# BeagleBone_Black_Wireless_3D.net
KiCad netlist of a schematic drawn in EAGLE
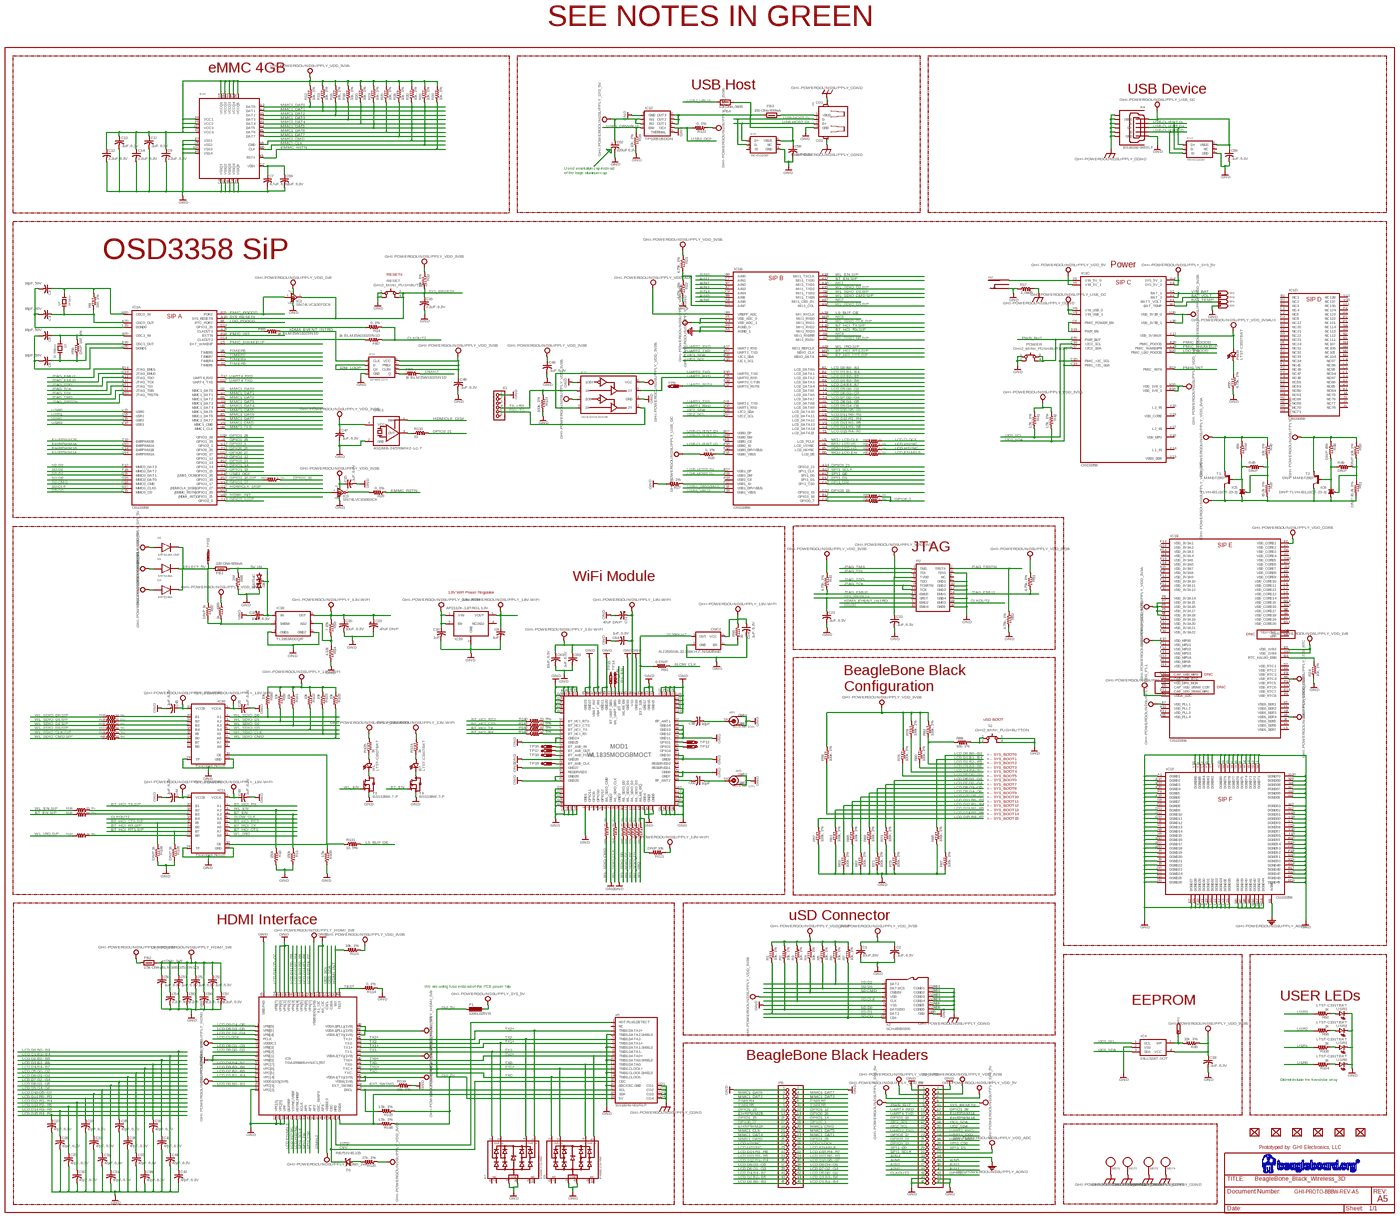
[diagram p0: schematic, sheet 1, overview]
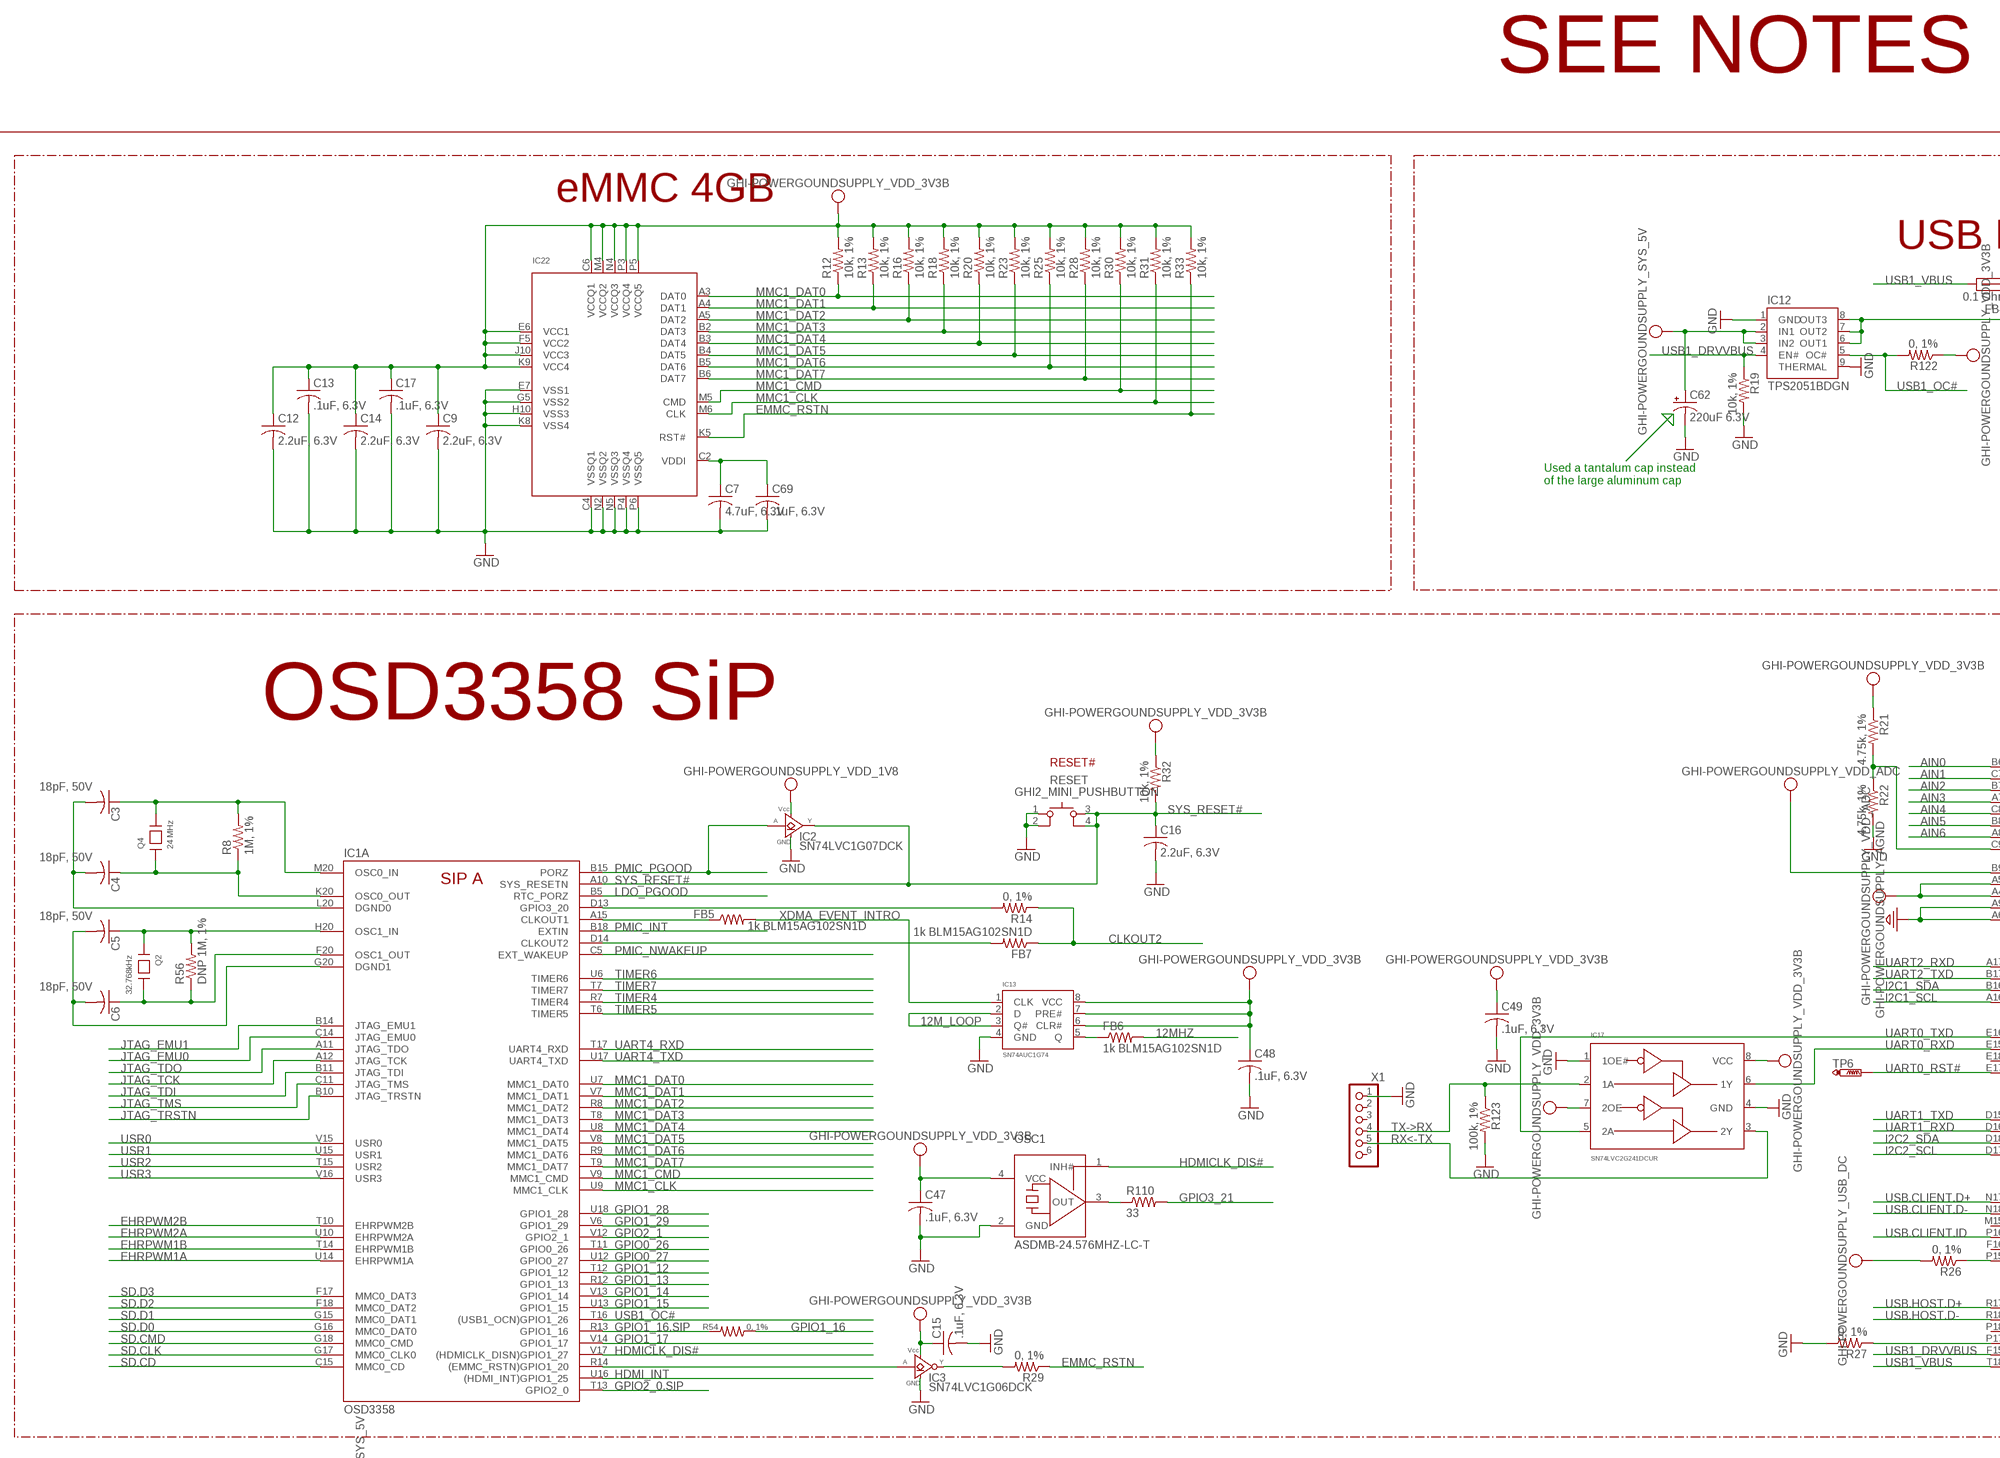
[diagram p1: schematic, sheet 1, part 1 of 4]
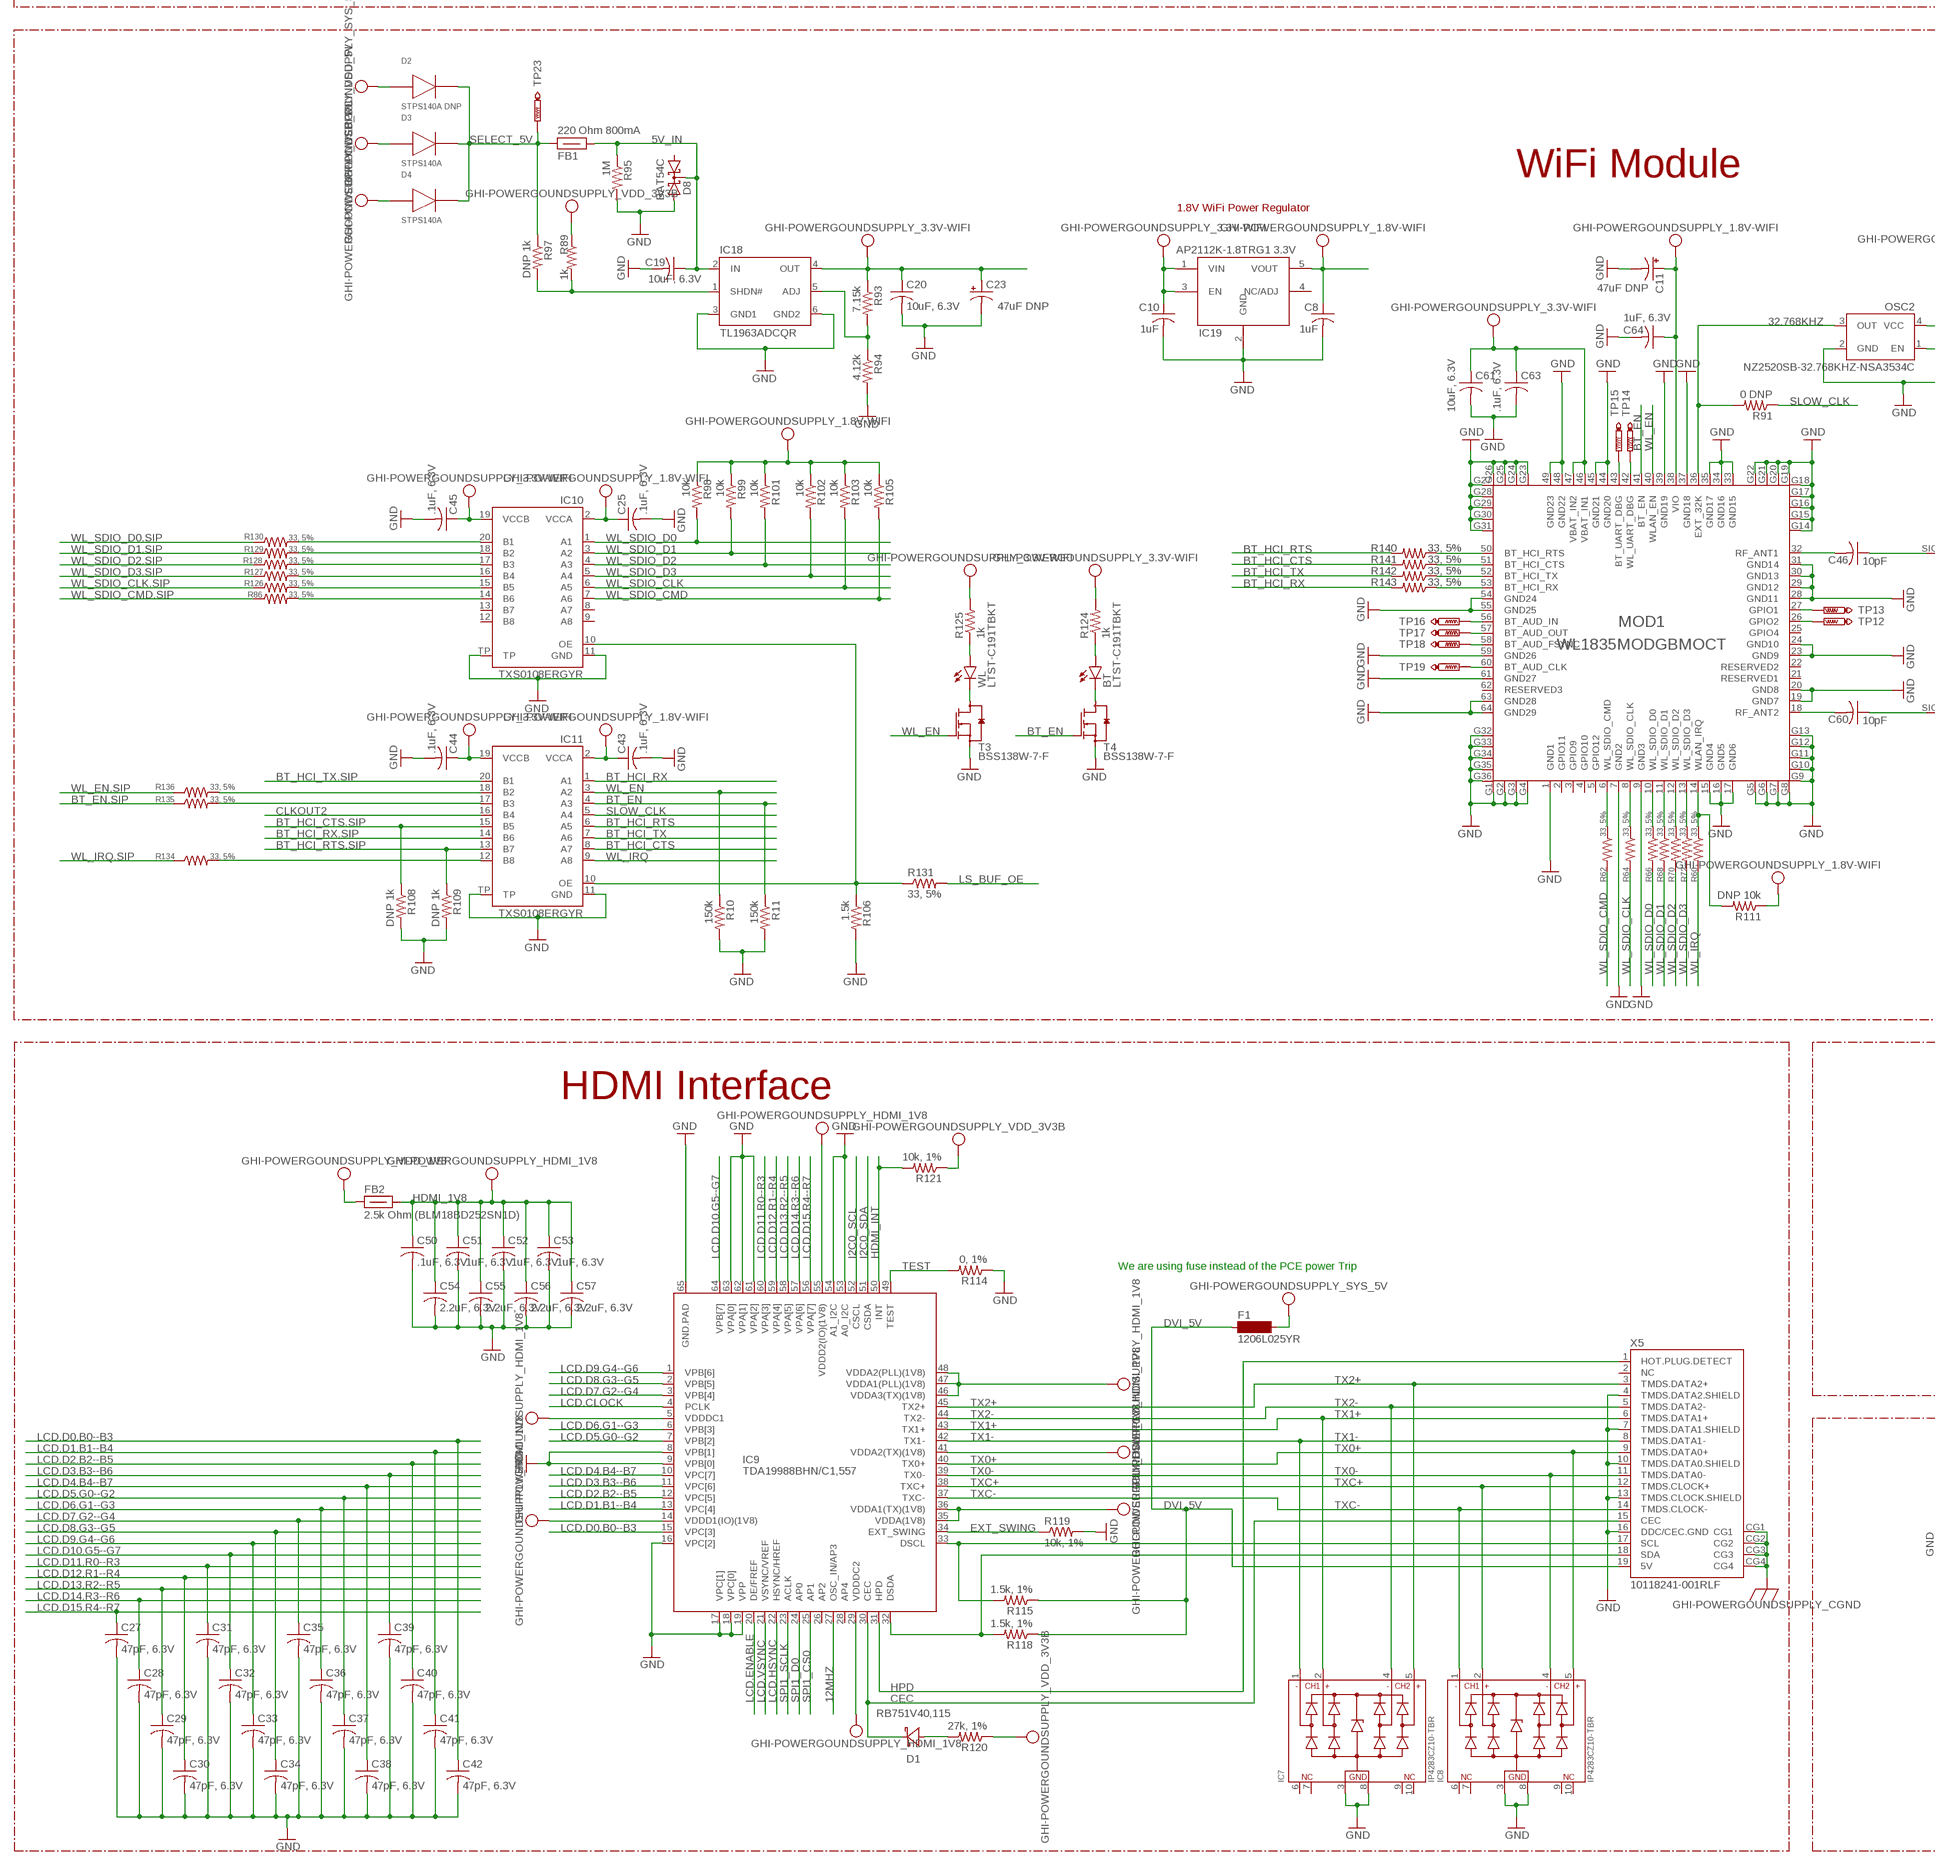
[diagram p2: schematic, sheet 1, part 2 of 4]
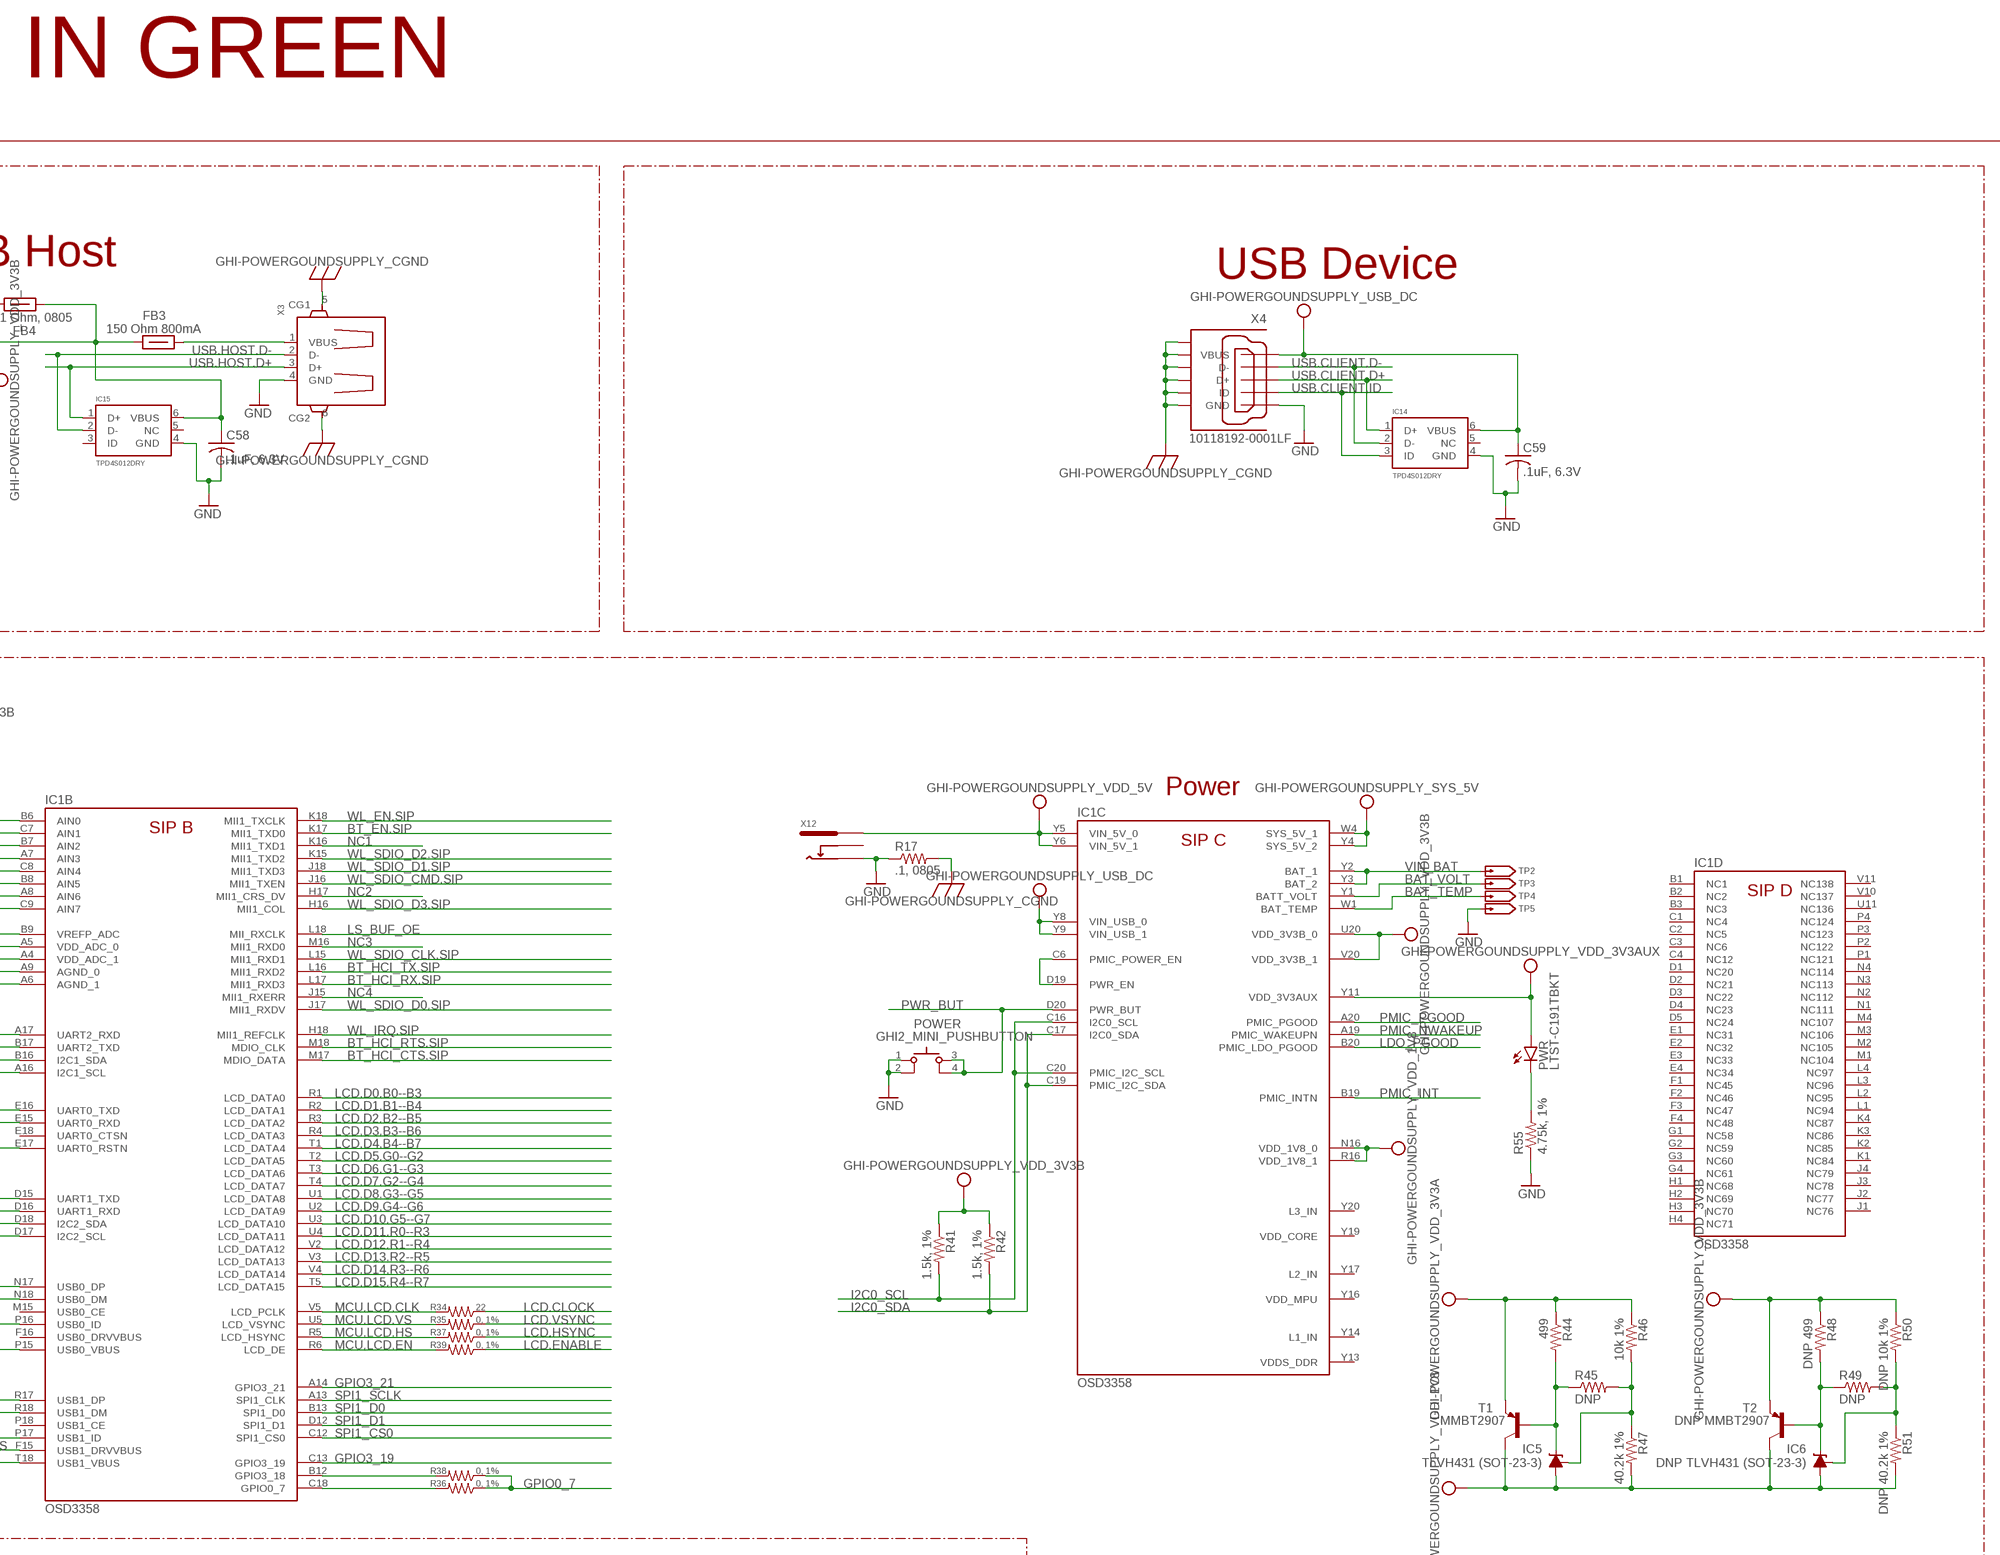
[diagram p3: schematic, sheet 1, part 3 of 4]
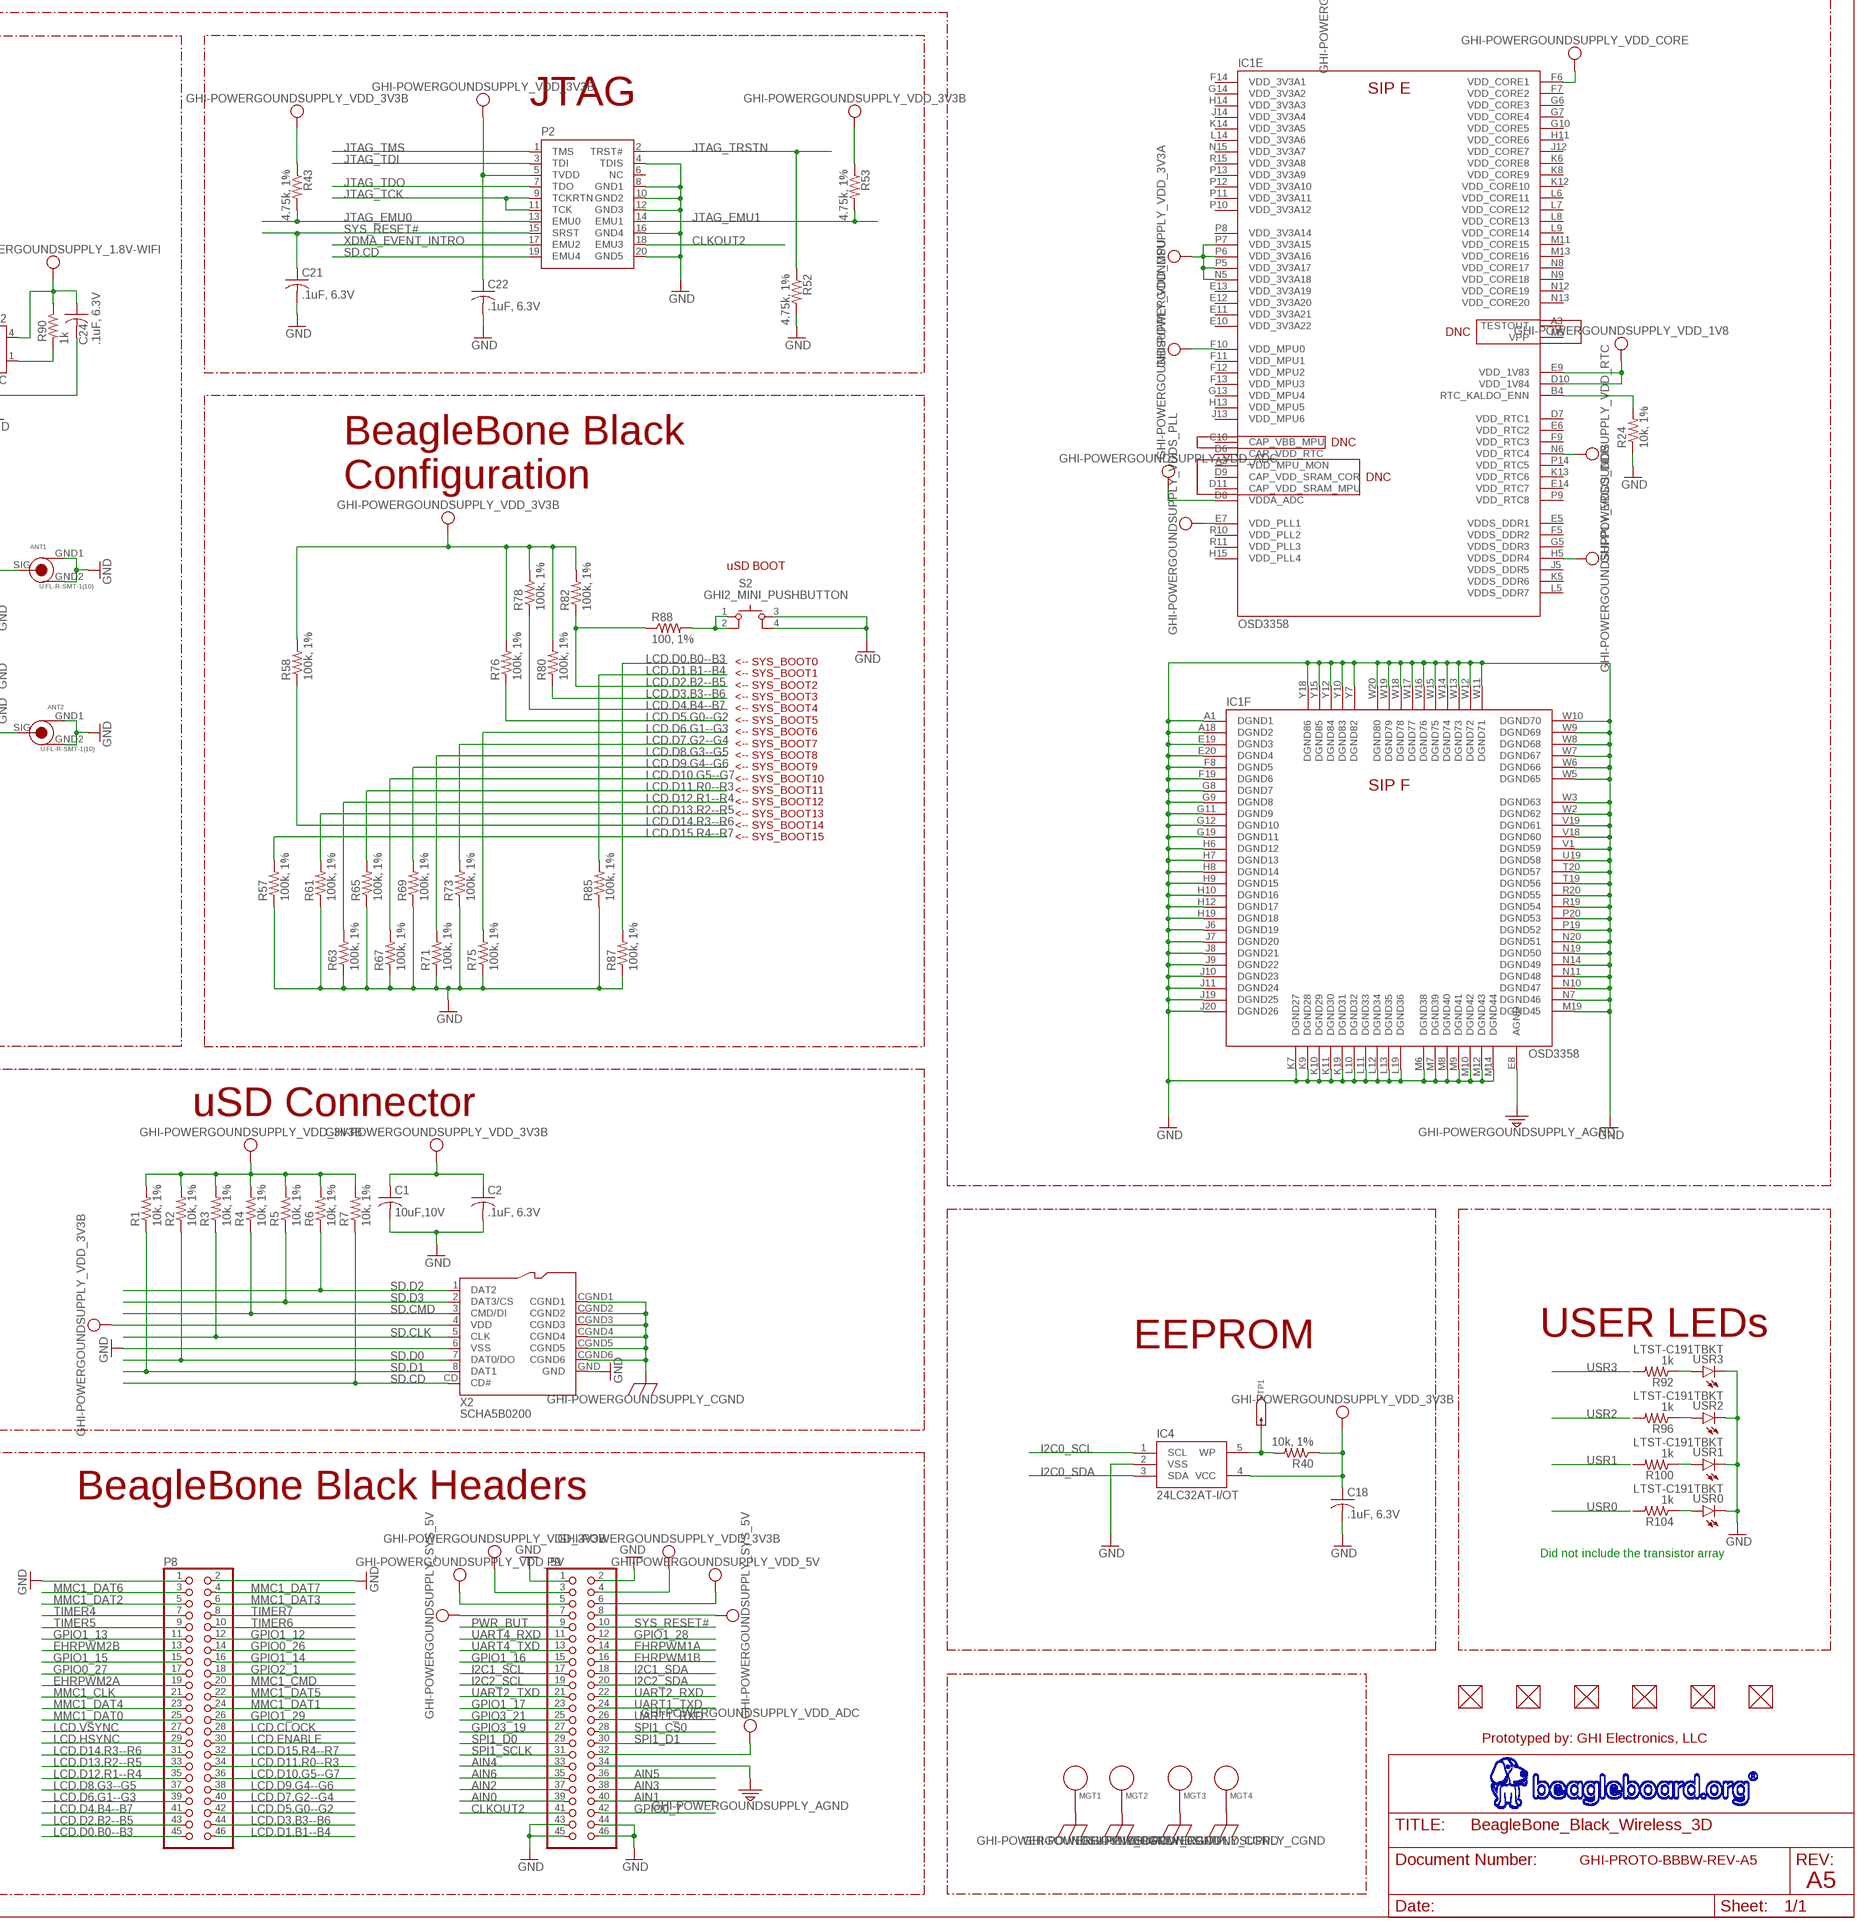
[diagram p4: schematic, sheet 1, part 4 of 4]

(export (version "E")
  (design (tool "Eeschema 10.0.6"))
  (components
    (comp (ref "ANT1")
      (value "U.FL-R-SMT-1(10)")
      (footprint "eagle-import:GHI-CONNECTORS_U.FL-R-SMT-1")
      (libsource (lib "eagle-import") (part "GHI-CONNECTORS_U.FL-R-SMT-1"))
    )
    (comp (ref "ANT2")
      (value "U.FL-R-SMT-1(10)")
      (footprint "eagle-import:GHI-CONNECTORS_U.FL-R-SMT-1")
      (libsource (lib "eagle-import") (part "GHI-CONNECTORS_U.FL-R-SMT-1"))
    )
    (comp (ref "BT")
      (value "LTST-C191TBKT")
      (footprint "eagle-import:GHI-BASICCOMPONENTS_0603-LED")
      (libsource (lib "eagle-import") (part "GHI-BASICCOMPONENTS_LED-(INCH)-0603"))
    )
    (comp (ref "C1")
      (value "10uF,10V")
      (footprint "eagle-import:C0603K")
      (libsource (lib "eagle-import") (part "rcl_334_C-USC0603K"))
    )
    (comp (ref "C2")
      (value ".1uF, 6.3V")
      (footprint "eagle-import:C0402K")
      (libsource (lib "eagle-import") (part "C-USC0402K"))
    )
    (comp (ref "C3")
      (value "18pF, 50V")
      (footprint "eagle-import:C0402K")
      (libsource (lib "eagle-import") (part "C-USC0402K"))
    )
    (comp (ref "C4")
      (value "18pF, 50V")
      (footprint "eagle-import:C0402K")
      (libsource (lib "eagle-import") (part "C-USC0402K"))
    )
    (comp (ref "C5")
      (value "18pF, 50V")
      (footprint "eagle-import:C0402K")
      (libsource (lib "eagle-import") (part "C-USC0402K"))
    )
    (comp (ref "C6")
      (value "18pF, 50V")
      (footprint "eagle-import:C0402K")
      (libsource (lib "eagle-import") (part "C-USC0402K"))
    )
    (comp (ref "C7")
      (value "4.7uF, 6.3V")
      (footprint "eagle-import:C0805K")
      (libsource (lib "eagle-import") (part "rcl_334_C-USC0805K"))
    )
    (comp (ref "C8")
      (value "1uF")
      (footprint "eagle-import:C0402K")
      (libsource (lib "eagle-import") (part "C-USC0402K"))
    )
    (comp (ref "C9")
      (value "2.2uF, 6.3V")
      (footprint "eagle-import:C0805K")
      (libsource (lib "eagle-import") (part "rcl_334_C-USC0805K"))
    )
    (comp (ref "C10")
      (value "1uF")
      (footprint "eagle-import:C0402K")
      (libsource (lib "eagle-import") (part "C-USC0402K"))
    )
    (comp (ref "C11")
      (value "47uF DNP")
      (footprint "eagle-import:CT3528")
      (libsource (lib "eagle-import") (part "CPOL-USCT3528"))
    )
    (comp (ref "C12")
      (value "2.2uF, 6.3V")
      (footprint "eagle-import:C0805K")
      (libsource (lib "eagle-import") (part "rcl_334_C-USC0805K"))
    )
    (comp (ref "C13")
      (value ".1uF, 6.3V")
      (footprint "eagle-import:C0402K")
      (libsource (lib "eagle-import") (part "C-USC0402K"))
    )
    (comp (ref "C14")
      (value "2.2uF, 6.3V")
      (footprint "eagle-import:C0805K")
      (libsource (lib "eagle-import") (part "rcl_334_C-USC0805K"))
    )
    (comp (ref "C15")
      (value ".1uF, 6.3V")
      (footprint "eagle-import:C0402K")
      (libsource (lib "eagle-import") (part "C-USC0402K"))
    )
    (comp (ref "C16")
      (value "2.2uF, 6.3V")
      (footprint "eagle-import:C0603K")
      (libsource (lib "eagle-import") (part "rcl_334_C-USC0603K"))
    )
    (comp (ref "C17")
      (value ".1uF, 6.3V")
      (footprint "eagle-import:C0402K")
      (libsource (lib "eagle-import") (part "C-USC0402K"))
    )
    (comp (ref "C18")
      (value ".1uF, 6.3V")
      (footprint "eagle-import:C0402K")
      (libsource (lib "eagle-import") (part "C-USC0402K"))
    )
    (comp (ref "C19")
      (value "10uF, 6.3V")
      (footprint "eagle-import:C0603K")
      (libsource (lib "eagle-import") (part "rcl_334_C-USC0603K"))
    )
    (comp (ref "C20")
      (value "10uF, 6.3V")
      (footprint "eagle-import:C0603K")
      (libsource (lib "eagle-import") (part "rcl_334_C-USC0603K"))
    )
    (comp (ref "C21")
      (value ".1uF, 6.3V")
      (footprint "eagle-import:C0402K")
      (libsource (lib "eagle-import") (part "C-USC0402K"))
    )
    (comp (ref "C22")
      (value ".1uF, 6.3V")
      (footprint "eagle-import:C0402K")
      (libsource (lib "eagle-import") (part "C-USC0402K"))
    )
    (comp (ref "C23")
      (value "47uF DNP")
      (footprint "eagle-import:CT3528")
      (libsource (lib "eagle-import") (part "CPOL-USCT3528"))
    )
    (comp (ref "C24")
      (value ".1uF, 6.3V")
      (footprint "eagle-import:C0402K")
      (libsource (lib "eagle-import") (part "C-USC0402K"))
    )
    (comp (ref "C25")
      (value ".1uF, 6.3V")
      (footprint "eagle-import:C0402K")
      (libsource (lib "eagle-import") (part "C-USC0402K"))
    )
    (comp (ref "C27")
      (value "47pF, 6.3V")
      (footprint "eagle-import:C0402K")
      (libsource (lib "eagle-import") (part "C-USC0402K"))
    )
    (comp (ref "C28")
      (value "47pF, 6.3V")
      (footprint "eagle-import:C0402K")
      (libsource (lib "eagle-import") (part "C-USC0402K"))
    )
    (comp (ref "C29")
      (value "47pF, 6.3V")
      (footprint "eagle-import:C0402K")
      (libsource (lib "eagle-import") (part "C-USC0402K"))
    )
    (comp (ref "C30")
      (value "47pF, 6.3V")
      (footprint "eagle-import:C0402K")
      (libsource (lib "eagle-import") (part "C-USC0402K"))
    )
    (comp (ref "C31")
      (value "47pF, 6.3V")
      (footprint "eagle-import:C0402K")
      (libsource (lib "eagle-import") (part "C-USC0402K"))
    )
    (comp (ref "C32")
      (value "47pF, 6.3V")
      (footprint "eagle-import:C0402K")
      (libsource (lib "eagle-import") (part "C-USC0402K"))
    )
    (comp (ref "C33")
      (value "47pF, 6.3V")
      (footprint "eagle-import:C0402K")
      (libsource (lib "eagle-import") (part "C-USC0402K"))
    )
    (comp (ref "C34")
      (value "47pF, 6.3V")
      (footprint "eagle-import:C0402K")
      (libsource (lib "eagle-import") (part "C-USC0402K"))
    )
    (comp (ref "C35")
      (value "47pF, 6.3V")
      (footprint "eagle-import:C0402K")
      (libsource (lib "eagle-import") (part "C-USC0402K"))
    )
    (comp (ref "C36")
      (value "47pF, 6.3V")
      (footprint "eagle-import:C0402K")
      (libsource (lib "eagle-import") (part "C-USC0402K"))
    )
    (comp (ref "C37")
      (value "47pF, 6.3V")
      (footprint "eagle-import:C0402K")
      (libsource (lib "eagle-import") (part "C-USC0402K"))
    )
    (comp (ref "C38")
      (value "47pF, 6.3V")
      (footprint "eagle-import:C0402K")
      (libsource (lib "eagle-import") (part "C-USC0402K"))
    )
    (comp (ref "C39")
      (value "47pF, 6.3V")
      (footprint "eagle-import:C0402K")
      (libsource (lib "eagle-import") (part "C-USC0402K"))
    )
    (comp (ref "C40")
      (value "47pF, 6.3V")
      (footprint "eagle-import:C0402K")
      (libsource (lib "eagle-import") (part "C-USC0402K"))
    )
    (comp (ref "C41")
      (value "47pF, 6.3V")
      (footprint "eagle-import:C0402K")
      (libsource (lib "eagle-import") (part "C-USC0402K"))
    )
    (comp (ref "C42")
      (value "47pF, 6.3V")
      (footprint "eagle-import:C0402K")
      (libsource (lib "eagle-import") (part "C-USC0402K"))
    )
    (comp (ref "C43")
      (value ".1uF, 6.3V")
      (footprint "eagle-import:C0402K")
      (libsource (lib "eagle-import") (part "C-USC0402K"))
    )
    (comp (ref "C44")
      (value ".1uF, 6.3V")
      (footprint "eagle-import:C0402K")
      (libsource (lib "eagle-import") (part "C-USC0402K"))
    )
    (comp (ref "C45")
      (value ".1uF, 6.3V")
      (footprint "eagle-import:C0402K")
      (libsource (lib "eagle-import") (part "C-USC0402K"))
    )
    (comp (ref "C46")
      (value "10pF")
      (footprint "eagle-import:C0402K")
      (libsource (lib "eagle-import") (part "C-USC0402K"))
    )
    (comp (ref "C47")
      (value ".1uF, 6.3V")
      (footprint "eagle-import:C0402K")
      (libsource (lib "eagle-import") (part "C-USC0402K"))
    )
    (comp (ref "C48")
      (value ".1uF, 6.3V")
      (footprint "eagle-import:C0402K")
      (libsource (lib "eagle-import") (part "C-USC0402K"))
    )
    (comp (ref "C49")
      (value ".1uF, 6.3V")
      (footprint "eagle-import:C0402K")
      (libsource (lib "eagle-import") (part "C-USC0402K"))
    )
    (comp (ref "C50")
      (value ".1uF, 6.3V")
      (footprint "eagle-import:C0402K")
      (libsource (lib "eagle-import") (part "C-USC0402K"))
    )
    (comp (ref "C51")
      (value ".1uF, 6.3V")
      (footprint "eagle-import:C0402K")
      (libsource (lib "eagle-import") (part "C-USC0402K"))
    )
    (comp (ref "C52")
      (value ".1uF, 6.3V")
      (footprint "eagle-import:C0402K")
      (libsource (lib "eagle-import") (part "C-USC0402K"))
    )
    (comp (ref "C53")
      (value ".1uF, 6.3V")
      (footprint "eagle-import:C0402K")
      (libsource (lib "eagle-import") (part "C-USC0402K"))
    )
    (comp (ref "C54")
      (value "2.2uF, 6.3V")
      (footprint "eagle-import:C0603K")
      (libsource (lib "eagle-import") (part "rcl_334_C-USC0603K"))
    )
    (comp (ref "C55")
      (value "2.2uF, 6.3V")
      (footprint "eagle-import:C0603K")
      (libsource (lib "eagle-import") (part "rcl_334_C-USC0603K"))
    )
    (comp (ref "C56")
      (value "2.2uF, 6.3V")
      (footprint "eagle-import:C0603K")
      (libsource (lib "eagle-import") (part "rcl_334_C-USC0603K"))
    )
    (comp (ref "C57")
      (value "2.2uF, 6.3V")
      (footprint "eagle-import:C0603K")
      (libsource (lib "eagle-import") (part "rcl_334_C-USC0603K"))
    )
    (comp (ref "C58")
      (value ".1uF, 6.3V")
      (footprint "eagle-import:C0402K")
      (libsource (lib "eagle-import") (part "C-USC0402K"))
    )
    (comp (ref "C59")
      (value ".1uF, 6.3V")
      (footprint "eagle-import:C0402K")
      (libsource (lib "eagle-import") (part "C-USC0402K"))
    )
    (comp (ref "C60")
      (value "10pF")
      (footprint "eagle-import:C0402K")
      (libsource (lib "eagle-import") (part "C-USC0402K"))
    )
    (comp (ref "C61")
      (value "10uF, 6.3V")
      (footprint "eagle-import:C0603K")
      (libsource (lib "eagle-import") (part "rcl_334_C-USC0603K"))
    )
    (comp (ref "C62")
      (value "220uF 6.3V")
      (footprint "eagle-import:D_7343-31W")
      (libsource (lib "eagle-import") (part "CPOL-USD/7343-31W"))
    )
    (comp (ref "C63")
      (value ".1uF, 6.3V")
      (footprint "eagle-import:C0402K")
      (libsource (lib "eagle-import") (part "C-USC0402K"))
    )
    (comp (ref "C64")
      (value "1uF, 6.3V")
      (footprint "eagle-import:C0402K")
      (libsource (lib "eagle-import") (part "C-USC0402K"))
    )
    (comp (ref "C69")
      (value ".1uF, 6.3V")
      (footprint "eagle-import:C0402K")
      (libsource (lib "eagle-import") (part "C-USC0402K"))
    )
    (comp (ref "D1")
      (value "RB751V40,115")
      (footprint "eagle-import:GHI-BASICCOMPONENTS_SOD323(NXP)REFLOW")
      (libsource (lib "eagle-import") (part "GHI-BASICCOMPONENTS_DIODE-SCHOTTKY-(NXP)-SOD323-(REFLOW)"))
    )
    (comp (ref "D2")
      (value "STPS140A DNP")
      (footprint "eagle-import:GHI_DIODE_SMA")
      (libsource (lib "eagle-import") (part "GHI_DIODE_SMA"))
    )
    (comp (ref "D3")
      (value "STPS140A")
      (footprint "eagle-import:GHI_DIODE_SMA")
      (libsource (lib "eagle-import") (part "GHI_DIODE_SMA"))
    )
    (comp (ref "D4")
      (value "STPS140A")
      (footprint "eagle-import:GHI_DIODE_SMA")
      (libsource (lib "eagle-import") (part "GHI_DIODE_SMA"))
    )
    (comp (ref "D8")
      (value "BAT54C")
      (footprint "eagle-import:SOT23")
      (libsource (lib "eagle-import") (part "BAT54C"))
    )
    (comp (ref "F1")
      (value "1206L025YR")
      (footprint "eagle-import:SM-1206")
      (libsource (lib "eagle-import") (part "SM-1206"))
    )
    (comp (ref "FB1")
      (value "220 Ohm 800mA")
      (footprint "eagle-import:GHI-BASICCOMPONENTS_0805-RESISTOR")
      (libsource (lib "eagle-import") (part "GHI-BASICCOMPONENTS_FB-(INCH)-0805"))
    )
    (comp (ref "FB2")
      (value "2.5k Ohm (BLM18BD252SN1D)")
      (footprint "eagle-import:GHI-BASICCOMPONENTS_0805-RESISTOR")
      (libsource (lib "eagle-import") (part "GHI-BASICCOMPONENTS_FB-(INCH)-0805"))
    )
    (comp (ref "FB3")
      (value "150 Ohm 800mA")
      (footprint "eagle-import:GHI-BASICCOMPONENTS_0805-RESISTOR")
      (libsource (lib "eagle-import") (part "GHI-BASICCOMPONENTS_FB-(INCH)-0805"))
    )
    (comp (ref "FB4")
      (value "0.1 Ohm, 0805")
      (footprint "eagle-import:GHI-BASICCOMPONENTS_0805-RESISTOR")
      (libsource (lib "eagle-import") (part "GHI-BASICCOMPONENTS_FB-(INCH)-0805"))
    )
    (comp (ref "FB5")
      (value "1k BLM15AG102SN1D")
      (footprint "eagle-import:R0402")
      (libsource (lib "eagle-import") (part "R-US_R0402"))
    )
    (comp (ref "FB6")
      (value "1k BLM15AG102SN1D")
      (footprint "eagle-import:R0402")
      (libsource (lib "eagle-import") (part "R-US_R0402"))
    )
    (comp (ref "FB7")
      (value "1k BLM15AG102SN1D")
      (footprint "eagle-import:R0402")
      (libsource (lib "eagle-import") (part "R-US_R0402"))
    )
    (comp (ref "FUD1")
      (value "GHI_FIDUCIAL")
      (footprint "eagle-import:GHI_FIDUCIAL_40MIL")
      (libsource (lib "eagle-import") (part "GHI_FIDUCIAL"))
    )
    (comp (ref "FUD2")
      (value "GHI_FIDUCIAL")
      (footprint "eagle-import:GHI_FIDUCIAL_40MIL")
      (libsource (lib "eagle-import") (part "GHI_FIDUCIAL"))
    )
    (comp (ref "FUD3")
      (value "GHI_FIDUCIAL")
      (footprint "eagle-import:GHI_FIDUCIAL_40MIL")
      (libsource (lib "eagle-import") (part "GHI_FIDUCIAL"))
    )
    (comp (ref "FUD4")
      (value "GHI_FIDUCIAL")
      (footprint "eagle-import:GHI_FIDUCIAL_40MIL")
      (libsource (lib "eagle-import") (part "GHI_FIDUCIAL"))
    )
    (comp (ref "FUD5")
      (value "GHI_FIDUCIAL")
      (footprint "eagle-import:GHI_FIDUCIAL_40MIL")
      (libsource (lib "eagle-import") (part "GHI_FIDUCIAL"))
    )
    (comp (ref "FUD6")
      (value "GHI_FIDUCIAL")
      (footprint "eagle-import:GHI_FIDUCIAL_40MIL")
      (libsource (lib "eagle-import") (part "GHI_FIDUCIAL"))
    )
    (comp (ref "IC1")
      (value "OSD3358")
      (footprint "eagle-import:GHI-SOMS-PROCESSORS_OSD3358")
      (libsource (lib "eagle-import") (part "GHI-SOMS-PROCESSORS_SIP1000"))
    )
    (comp (ref "IC2")
      (value "SN74LVC1G07DCK")
      (footprint "eagle-import:GHI-IC_SC70(TI-DCK)")
      (libsource (lib "eagle-import") (part "GHI-IC_SN74LVC1G07DCK"))
    )
    (comp (ref "IC3")
      (value "SN74LVC1G06DCK")
      (footprint "eagle-import:GHI-IC_SC70(TI-DCK)")
      (libsource (lib "eagle-import") (part "GHI-IC_SN74LVC1G06DCK"))
    )
    (comp (ref "IC4")
      (value "24LC32AT-I/OT")
      (footprint "eagle-import:GHI-IC_SOT23-5(MICROCHIP)")
      (libsource (lib "eagle-import") (part "GHI-IC_24LC32A{dblquote}"))
    )
    (comp (ref "IC5")
      (value "TLVH431 (SOT-23-3)")
      (footprint "eagle-import:DBZ_R-PDSO-G3")
      (fields (field (name "MF") "TEXAS INSTRUMENT CONNECTORS") (field (name "MPN") "LM4041DIDBZR"))
      (libsource (lib "eagle-import") (part "LM4041IDBZD"))
    )
    (comp (ref "IC6")
      (value "DNP TLVH431 (SOT-23-3)")
      (footprint "eagle-import:DBZ_R-PDSO-G3")
      (fields (field (name "MF") "TEXAS INSTRUMENT CONNECTORS") (field (name "MPN") "LM4041DIDBZR"))
      (libsource (lib "eagle-import") (part "LM4041IDBZD"))
    )
    (comp (ref "IC7")
      (value "IP4283CZ10-TBR")
      (footprint "eagle-import:GHI-IC_SOT1176-1(NXP)")
      (libsource (lib "eagle-import") (part "GHI-IC_IP4283CZ10IP4283CZ10-TBR"))
    )
    (comp (ref "IC8")
      (value "IP4283CZ10-TBR")
      (footprint "eagle-import:GHI-IC_SOT1176-1(NXP)")
      (libsource (lib "eagle-import") (part "GHI-IC_IP4283CZ10IP4283CZ10-TBR"))
    )
    (comp (ref "IC9")
      (value "TDA19988BHN/C1,557")
      (footprint "eagle-import:GHI-IC_SOT804-4(NXP)")
      (libsource (lib "eagle-import") (part "GHI-IC_TDA19988BHN/C1"))
    )
    (comp (ref "IC10")
      (value "TXS0108ERGYR")
      (footprint "eagle-import:GHI-IC_R-PVQFN-N20(TI)")
      (libsource (lib "eagle-import") (part "GHI-IC_TXS0108ERGYR"))
    )
    (comp (ref "IC11")
      (value "TXS0108ERGYR")
      (footprint "eagle-import:GHI-IC_R-PVQFN-N20(TI)")
      (libsource (lib "eagle-import") (part "GHI-IC_TXS0108ERGYR"))
    )
    (comp (ref "IC12")
      (value "TPS2051BDGN")
      (footprint "eagle-import:GHI-IC_MSOP-POWER.PAD-8(TI)")
      (libsource (lib "eagle-import") (part "GHI-IC_TPS2051B"))
    )
    (comp (ref "IC13")
      (value "SN74AUC1G74")
      (footprint "eagle-import:GHI-IC_SM8-8(TI)")
      (libsource (lib "eagle-import") (part "GHI-IC_SN74AUC1G74"))
    )
    (comp (ref "IC14")
      (value "TPD4S012DRY")
      (footprint "eagle-import:GHI-IC_SON-6(TI)-DRY")
      (libsource (lib "eagle-import") (part "GHI-IC_TPD4S012DRYR"))
    )
    (comp (ref "IC15")
      (value "TPD4S012DRY")
      (footprint "eagle-import:GHI-IC_SON-6(TI)-DRY")
      (libsource (lib "eagle-import") (part "GHI-IC_TPD4S012DRYR"))
    )
    (comp (ref "IC17")
      (value "SN74LVC2G241DCUR")
      (footprint "eagle-import:GHI-IC_VSSOP8(TI)")
      (libsource (lib "eagle-import") (part "GHI-IC_SN74LVC2G241DCUR"))
    )
    (comp (ref "IC18")
      (value "TL1963ADCQR")
      (footprint "eagle-import:GHI-IC_SOT-223(DCQ_R-PDSO-G6_TI)")
      (libsource (lib "eagle-import") (part "GHI-IC_TL1963A"))
    )
    (comp (ref "IC19")
      (value "AP2112K-1.8TRG1 3.3V")
      (footprint "eagle-import:GHI_SOT23-5")
      (libsource (lib "eagle-import") (part "GHI_5PIN_REG"))
    )
    (comp (ref "IC22")
      (value "GHI-IC_EMMC04G-S100-B08U")
      (footprint "eagle-import:GHI-IC_MICRON_EMMC_153")
      (libsource (lib "eagle-import") (part "GHI-IC_EMMC04G-S100-B08U"))
    )
    (comp (ref "MGT1")
      (value "BEAGLEBONEBLACK_MOUNTING_HOLE")
      (footprint "eagle-import:BEAGLEBONEBLACK_MOUNTING_HOLE")
      (libsource (lib "eagle-import") (part "BEAGLEBONEBLACK_MOUNTING_HOLE"))
    )
    (comp (ref "MGT2")
      (value "BEAGLEBONEBLACK_MOUNTING_HOLE")
      (footprint "eagle-import:BEAGLEBONEBLACK_MOUNTING_HOLE")
      (libsource (lib "eagle-import") (part "BEAGLEBONEBLACK_MOUNTING_HOLE"))
    )
    (comp (ref "MGT3")
      (value "BEAGLEBONEBLACK_MOUNTING_HOLE")
      (footprint "eagle-import:BEAGLEBONEBLACK_MOUNTING_HOLE")
      (libsource (lib "eagle-import") (part "BEAGLEBONEBLACK_MOUNTING_HOLE"))
    )
    (comp (ref "MGT4")
      (value "BEAGLEBONEBLACK_MOUNTING_HOLE")
      (footprint "eagle-import:BEAGLEBONEBLACK_MOUNTING_HOLE")
      (libsource (lib "eagle-import") (part "BEAGLEBONEBLACK_MOUNTING_HOLE"))
    )
    (comp (ref "MOD1")
      (value "WL1835MODGBMOCT")
      (footprint "eagle-import:GHI-IC_MOC-100(TI)")
      (libsource (lib "eagle-import") (part "GHI-IC_WL1835MOD"))
    )
    (comp (ref "OSC1")
      (value "ASDMB-24.576MHZ-LC-T")
      (footprint "eagle-import:GHI2_OSCILLATOR-2.5X2.0-BBB")
      (libsource (lib "eagle-import") (part "GHI2_OSC-2.5X2.0"))
    )
    (comp (ref "OSC2")
      (value "NZ2520SB-32.768KHZ-NSA3534C")
      (footprint "eagle-import:GHI-IC_NZ2520S")
      (libsource (lib "eagle-import") (part "GHI-IC_OSCILLATOR"))
    )
    (comp (ref "P2")
      (value "BEAGLEBONEBLACK_JTAG")
      (footprint "eagle-import:BEAGLEBONEBLACK_JTAG")
      (libsource (lib "eagle-import") (part "BEAGLEBONEBLACK_JTAG"))
    )
    (comp (ref "P8")
      (value "GHI-HEADERS_HEADER-2X23-(INCH)-0.1-TH")
      (footprint "eagle-import:GHI-HEADERS_TH-2X23")
      (libsource (lib "eagle-import") (part "GHI-HEADERS_HEADER-2X23-(INCH)-0.1-TH"))
    )
    (comp (ref "P9")
      (value "GHI-HEADERS_HEADER-2X23-(INCH)-0.1-TH")
      (footprint "eagle-import:GHI-HEADERS_TH-2X23")
      (libsource (lib "eagle-import") (part "GHI-HEADERS_HEADER-2X23-(INCH)-0.1-TH"))
    )
    (comp (ref "POWER")
      (value "GHI2_MINI_PUSHBUTTON")
      (footprint "eagle-import:GHI2_MINI_PUSHBUTTON")
      (libsource (lib "eagle-import") (part "GHI2_MINI_PUSHBUTTON"))
    )
    (comp (ref "PWR")
      (value "LTST-C191TBKT")
      (footprint "eagle-import:GHI-BASICCOMPONENTS_0603-LED")
      (libsource (lib "eagle-import") (part "GHI-BASICCOMPONENTS_LED-(INCH)-0603"))
    )
    (comp (ref "Q2")
      (value "32.768kHz")
      (footprint "eagle-import:GHI2_CRYSTAL_3.2X1.5")
      (libsource (lib "eagle-import") (part "GHI2_CRYSTAL_3.2X1.5"))
    )
    (comp (ref "Q4")
      (value "24 MHz")
      (footprint "eagle-import:GHI2_CRYSTAL_5X3.2MM")
      (libsource (lib "eagle-import") (part "GHI2_CRYSTAL_5X3.2MM"))
    )
    (comp (ref "R1")
      (value "10k, 1%")
      (footprint "eagle-import:R0402")
      (libsource (lib "eagle-import") (part "R-US_R0402"))
    )
    (comp (ref "R2")
      (value "10k, 1%")
      (footprint "eagle-import:R0402")
      (libsource (lib "eagle-import") (part "R-US_R0402"))
    )
    (comp (ref "R3")
      (value "10k, 1%")
      (footprint "eagle-import:R0402")
      (libsource (lib "eagle-import") (part "R-US_R0402"))
    )
    (comp (ref "R4")
      (value "10k, 1%")
      (footprint "eagle-import:R0402")
      (libsource (lib "eagle-import") (part "R-US_R0402"))
    )
    (comp (ref "R5")
      (value "10k, 1%")
      (footprint "eagle-import:R0402")
      (libsource (lib "eagle-import") (part "R-US_R0402"))
    )
    (comp (ref "R6")
      (value "10k, 1%")
      (footprint "eagle-import:R0402")
      (libsource (lib "eagle-import") (part "R-US_R0402"))
    )
    (comp (ref "R7")
      (value "10k, 1%")
      (footprint "eagle-import:R0402")
      (libsource (lib "eagle-import") (part "R-US_R0402"))
    )
    (comp (ref "R8")
      (value "1M, 1%")
      (footprint "eagle-import:R0402")
      (libsource (lib "eagle-import") (part "R-US_R0402"))
    )
    (comp (ref "R10")
      (value "150k")
      (footprint "eagle-import:R0402")
      (libsource (lib "eagle-import") (part "R-US_R0402"))
    )
    (comp (ref "R11")
      (value "150k")
      (footprint "eagle-import:R0402")
      (libsource (lib "eagle-import") (part "R-US_R0402"))
    )
    (comp (ref "R12")
      (value "10k, 1%")
      (footprint "eagle-import:R0402")
      (libsource (lib "eagle-import") (part "R-US_R0402"))
    )
    (comp (ref "R13")
      (value "10k, 1%")
      (footprint "eagle-import:R0402")
      (libsource (lib "eagle-import") (part "R-US_R0402"))
    )
    (comp (ref "R14")
      (value "0, 1%")
      (footprint "eagle-import:R0402")
      (libsource (lib "eagle-import") (part "R-US_R0402"))
    )
    (comp (ref "R16")
      (value "10k, 1%")
      (footprint "eagle-import:R0402")
      (libsource (lib "eagle-import") (part "R-US_R0402"))
    )
    (comp (ref "R17")
      (value ".1, 0805")
      (footprint "eagle-import:R0805")
      (libsource (lib "eagle-import") (part "R-US_R0805"))
    )
    (comp (ref "R18")
      (value "10k, 1%")
      (footprint "eagle-import:R0402")
      (libsource (lib "eagle-import") (part "R-US_R0402"))
    )
    (comp (ref "R19")
      (value "10k, 1%")
      (footprint "eagle-import:R0402")
      (libsource (lib "eagle-import") (part "R-US_R0402"))
    )
    (comp (ref "R20")
      (value "10k, 1%")
      (footprint "eagle-import:R0402")
      (libsource (lib "eagle-import") (part "R-US_R0402"))
    )
    (comp (ref "R21")
      (value "4.75k, 1%")
      (footprint "eagle-import:R0402")
      (libsource (lib "eagle-import") (part "R-US_R0402"))
    )
    (comp (ref "R22")
      (value "4.75k, 1%")
      (footprint "eagle-import:R0402")
      (libsource (lib "eagle-import") (part "R-US_R0402"))
    )
    (comp (ref "R23")
      (value "10k, 1%")
      (footprint "eagle-import:R0402")
      (libsource (lib "eagle-import") (part "R-US_R0402"))
    )
    (comp (ref "R24")
      (value "10k, 1%")
      (footprint "eagle-import:R0402")
      (libsource (lib "eagle-import") (part "R-US_R0402"))
    )
    (comp (ref "R25")
      (value "10k, 1%")
      (footprint "eagle-import:R0402")
      (libsource (lib "eagle-import") (part "R-US_R0402"))
    )
    (comp (ref "R26")
      (value "0, 1%")
      (footprint "eagle-import:R0402")
      (libsource (lib "eagle-import") (part "R-US_R0402"))
    )
    (comp (ref "R27")
      (value "0, 1%")
      (footprint "eagle-import:R0402")
      (libsource (lib "eagle-import") (part "R-US_R0402"))
    )
    (comp (ref "R28")
      (value "10k, 1%")
      (footprint "eagle-import:R0402")
      (libsource (lib "eagle-import") (part "R-US_R0402"))
    )
    (comp (ref "R29")
      (value "0, 1%")
      (footprint "eagle-import:R0402")
      (libsource (lib "eagle-import") (part "R-US_R0402"))
    )
    (comp (ref "R30")
      (value "10k, 1%")
      (footprint "eagle-import:R0402")
      (libsource (lib "eagle-import") (part "R-US_R0402"))
    )
    (comp (ref "R31")
      (value "10k, 1%")
      (footprint "eagle-import:R0402")
      (libsource (lib "eagle-import") (part "R-US_R0402"))
    )
    (comp (ref "R32")
      (value "10k, 1%")
      (footprint "eagle-import:R0402")
      (libsource (lib "eagle-import") (part "R-US_R0402"))
    )
    (comp (ref "R33")
      (value "10k, 1%")
      (footprint "eagle-import:R0402")
      (libsource (lib "eagle-import") (part "R-US_R0402"))
    )
    (comp (ref "R34")
      (value "22")
      (footprint "eagle-import:R0402")
      (libsource (lib "eagle-import") (part "R-US_R0402"))
    )
    (comp (ref "R35")
      (value "0, 1%")
      (footprint "eagle-import:R0402")
      (libsource (lib "eagle-import") (part "R-US_R0402"))
    )
    (comp (ref "R36")
      (value "0, 1%")
      (footprint "eagle-import:R0402")
      (libsource (lib "eagle-import") (part "R-US_R0402"))
    )
    (comp (ref "R37")
      (value "0, 1%")
      (footprint "eagle-import:R0402")
      (libsource (lib "eagle-import") (part "R-US_R0402"))
    )
    (comp (ref "R38")
      (value "0, 1%")
      (footprint "eagle-import:R0402")
      (libsource (lib "eagle-import") (part "R-US_R0402"))
    )
    (comp (ref "R39")
      (value "0, 1%")
      (footprint "eagle-import:R0402")
      (libsource (lib "eagle-import") (part "R-US_R0402"))
    )
    (comp (ref "R40")
      (value "10k, 1%")
      (footprint "eagle-import:R0402")
      (libsource (lib "eagle-import") (part "R-US_R0402"))
    )
    (comp (ref "R41")
      (value "1.5k, 1%")
      (footprint "eagle-import:R0402")
      (libsource (lib "eagle-import") (part "R-US_R0402"))
    )
    (comp (ref "R42")
      (value "1.5k, 1%")
      (footprint "eagle-import:R0402")
      (libsource (lib "eagle-import") (part "R-US_R0402"))
    )
    (comp (ref "R43")
      (value "4.75k, 1%")
      (footprint "eagle-import:R0402")
      (libsource (lib "eagle-import") (part "R-US_R0402"))
    )
    (comp (ref "R44")
      (value "499")
      (footprint "eagle-import:R0402")
      (libsource (lib "eagle-import") (part "R-US_R0402"))
    )
    (comp (ref "R45")
      (value "DNP")
      (footprint "eagle-import:R0402")
      (libsource (lib "eagle-import") (part "R-US_R0402"))
    )
    (comp (ref "R46")
      (value "10k 1%")
      (footprint "eagle-import:R0402")
      (libsource (lib "eagle-import") (part "R-US_R0402"))
    )
    (comp (ref "R47")
      (value "40.2k 1%")
      (footprint "eagle-import:R0402")
      (libsource (lib "eagle-import") (part "R-US_R0402"))
    )
    (comp (ref "R48")
      (value "DNP 499")
      (footprint "eagle-import:R0402")
      (libsource (lib "eagle-import") (part "R-US_R0402"))
    )
    (comp (ref "R49")
      (value "DNP")
      (footprint "eagle-import:R0402")
      (libsource (lib "eagle-import") (part "R-US_R0402"))
    )
    (comp (ref "R50")
      (value "DNP 10k 1%")
      (footprint "eagle-import:R0402")
      (libsource (lib "eagle-import") (part "R-US_R0402"))
    )
    (comp (ref "R51")
      (value "DNP 40.2k 1%")
      (footprint "eagle-import:R0402")
      (libsource (lib "eagle-import") (part "R-US_R0402"))
    )
    (comp (ref "R52")
      (value "4.75k, 1%")
      (footprint "eagle-import:R0402")
      (libsource (lib "eagle-import") (part "R-US_R0402"))
    )
    (comp (ref "R53")
      (value "4.75k, 1%")
      (footprint "eagle-import:R0402")
      (libsource (lib "eagle-import") (part "R-US_R0402"))
    )
    (comp (ref "R54")
      (value "0, 1%")
      (footprint "eagle-import:R0402")
      (libsource (lib "eagle-import") (part "R-US_R0402"))
    )
    (comp (ref "R55")
      (value "4.75k, 1%")
      (footprint "eagle-import:R0402")
      (libsource (lib "eagle-import") (part "R-US_R0402"))
    )
    (comp (ref "R56")
      (value "DNP 1M, 1%")
      (footprint "eagle-import:R0402")
      (libsource (lib "eagle-import") (part "R-US_R0402"))
    )
    (comp (ref "R57")
      (value "100k, 1%")
      (footprint "eagle-import:R0402")
      (libsource (lib "eagle-import") (part "R-US_R0402"))
    )
    (comp (ref "R58")
      (value "100k, 1%")
      (footprint "eagle-import:R0402")
      (libsource (lib "eagle-import") (part "R-US_R0402"))
    )
    (comp (ref "R60")
      (value "33, 5%")
      (footprint "eagle-import:R0402")
      (libsource (lib "eagle-import") (part "R-US_R0402"))
    )
    (comp (ref "R61")
      (value "100k, 1%")
      (footprint "eagle-import:R0402")
      (libsource (lib "eagle-import") (part "R-US_R0402"))
    )
    (comp (ref "R62")
      (value "33, 5%")
      (footprint "eagle-import:R0402")
      (libsource (lib "eagle-import") (part "R-US_R0402"))
    )
    (comp (ref "R63")
      (value "100k, 1%")
      (footprint "eagle-import:R0402")
      (libsource (lib "eagle-import") (part "R-US_R0402"))
    )
    (comp (ref "R64")
      (value "33, 5%")
      (footprint "eagle-import:R0402")
      (libsource (lib "eagle-import") (part "R-US_R0402"))
    )
    (comp (ref "R65")
      (value "100k, 1%")
      (footprint "eagle-import:R0402")
      (libsource (lib "eagle-import") (part "R-US_R0402"))
    )
    (comp (ref "R66")
      (value "33, 5%")
      (footprint "eagle-import:R0402")
      (libsource (lib "eagle-import") (part "R-US_R0402"))
    )
    (comp (ref "R67")
      (value "100k, 1%")
      (footprint "eagle-import:R0402")
      (libsource (lib "eagle-import") (part "R-US_R0402"))
    )
    (comp (ref "R68")
      (value "33, 5%")
      (footprint "eagle-import:R0402")
      (libsource (lib "eagle-import") (part "R-US_R0402"))
    )
    (comp (ref "R69")
      (value "100k, 1%")
      (footprint "eagle-import:R0402")
      (libsource (lib "eagle-import") (part "R-US_R0402"))
    )
    (comp (ref "R70")
      (value "33, 5%")
      (footprint "eagle-import:R0402")
      (libsource (lib "eagle-import") (part "R-US_R0402"))
    )
    (comp (ref "R71")
      (value "100k, 1%")
      (footprint "eagle-import:R0402")
      (libsource (lib "eagle-import") (part "R-US_R0402"))
    )
    (comp (ref "R72")
      (value "33, 5%")
      (footprint "eagle-import:R0402")
      (libsource (lib "eagle-import") (part "R-US_R0402"))
    )
    (comp (ref "R73")
      (value "100k, 1%")
      (footprint "eagle-import:R0402")
      (libsource (lib "eagle-import") (part "R-US_R0402"))
    )
    (comp (ref "R75")
      (value "100k, 1%")
      (footprint "eagle-import:R0402")
      (libsource (lib "eagle-import") (part "R-US_R0402"))
    )
    (comp (ref "R76")
      (value "100k, 1%")
      (footprint "eagle-import:R0402")
      (libsource (lib "eagle-import") (part "R-US_R0402"))
    )
    (comp (ref "R78")
      (value "100k, 1%")
      (footprint "eagle-import:R0402")
      (libsource (lib "eagle-import") (part "R-US_R0402"))
    )
    (comp (ref "R80")
      (value "100k, 1%")
      (footprint "eagle-import:R0402")
      (libsource (lib "eagle-import") (part "R-US_R0402"))
    )
    (comp (ref "R82")
      (value "100k, 1%")
      (footprint "eagle-import:R0402")
      (libsource (lib "eagle-import") (part "R-US_R0402"))
    )
    (comp (ref "R85")
      (value "100k, 1%")
      (footprint "eagle-import:R0402")
      (libsource (lib "eagle-import") (part "R-US_R0402"))
    )
    (comp (ref "R86")
      (value "33, 5%")
      (footprint "eagle-import:R0603")
      (libsource (lib "eagle-import") (part "rcl_334_R-US_R0603"))
    )
    (comp (ref "R87")
      (value "100k, 1%")
      (footprint "eagle-import:R0402")
      (libsource (lib "eagle-import") (part "R-US_R0402"))
    )
    (comp (ref "R88")
      (value "100, 1%")
      (footprint "eagle-import:R0402")
      (libsource (lib "eagle-import") (part "R-US_R0402"))
    )
    (comp (ref "R89")
      (value "1k")
      (footprint "eagle-import:R0402")
      (libsource (lib "eagle-import") (part "R-US_R0402"))
    )
    (comp (ref "R90")
      (value "1k")
      (footprint "eagle-import:R0402")
      (libsource (lib "eagle-import") (part "R-US_R0402"))
    )
    (comp (ref "R91")
      (value "0 DNP")
      (footprint "eagle-import:R0402")
      (libsource (lib "eagle-import") (part "R-US_R0402"))
    )
    (comp (ref "R92")
      (value "1k")
      (footprint "eagle-import:R0402")
      (libsource (lib "eagle-import") (part "R-US_R0402"))
    )
    (comp (ref "R93")
      (value "7.15k")
      (footprint "eagle-import:R0402")
      (libsource (lib "eagle-import") (part "R-US_R0402"))
    )
    (comp (ref "R94")
      (value "4.12k")
      (footprint "eagle-import:R0402")
      (libsource (lib "eagle-import") (part "R-US_R0402"))
    )
    (comp (ref "R95")
      (value "1M")
      (footprint "eagle-import:R0402")
      (libsource (lib "eagle-import") (part "R-US_R0402"))
    )
    (comp (ref "R96")
      (value "1k")
      (footprint "eagle-import:R0402")
      (libsource (lib "eagle-import") (part "R-US_R0402"))
    )
    (comp (ref "R97")
      (value "DNP 1k")
      (footprint "eagle-import:R0402")
      (libsource (lib "eagle-import") (part "R-US_R0402"))
    )
    (comp (ref "R98")
      (value "10k")
      (footprint "eagle-import:R0402")
      (libsource (lib "eagle-import") (part "R-US_R0402"))
    )
    (comp (ref "R99")
      (value "10k")
      (footprint "eagle-import:R0402")
      (libsource (lib "eagle-import") (part "R-US_R0402"))
    )
    (comp (ref "R100")
      (value "1k")
      (footprint "eagle-import:R0402")
      (libsource (lib "eagle-import") (part "R-US_R0402"))
    )
    (comp (ref "R101")
      (value "10k")
      (footprint "eagle-import:R0402")
      (libsource (lib "eagle-import") (part "R-US_R0402"))
    )
    (comp (ref "R102")
      (value "10k")
      (footprint "eagle-import:R0402")
      (libsource (lib "eagle-import") (part "R-US_R0402"))
    )
    (comp (ref "R103")
      (value "10k")
      (footprint "eagle-import:R0402")
      (libsource (lib "eagle-import") (part "R-US_R0402"))
    )
    (comp (ref "R104")
      (value "1k")
      (footprint "eagle-import:R0402")
      (libsource (lib "eagle-import") (part "R-US_R0402"))
    )
    (comp (ref "R105")
      (value "10k")
      (footprint "eagle-import:R0402")
      (libsource (lib "eagle-import") (part "R-US_R0402"))
    )
    (comp (ref "R106")
      (value "1.5k")
      (footprint "eagle-import:R0402")
      (libsource (lib "eagle-import") (part "R-US_R0402"))
    )
    (comp (ref "R108")
      (value "DNP 1k")
      (footprint "eagle-import:R0402")
      (libsource (lib "eagle-import") (part "R-US_R0402"))
    )
    (comp (ref "R109")
      (value "DNP 1k")
      (footprint "eagle-import:R0402")
      (libsource (lib "eagle-import") (part "R-US_R0402"))
    )
    (comp (ref "R110")
      (value "33")
      (footprint "eagle-import:R0402")
      (libsource (lib "eagle-import") (part "R-US_R0402"))
    )
    (comp (ref "R111")
      (value "DNP 10k")
      (footprint "eagle-import:R0402")
      (libsource (lib "eagle-import") (part "R-US_R0402"))
    )
    (comp (ref "R114")
      (value "0, 1%")
      (footprint "eagle-import:R0402")
      (libsource (lib "eagle-import") (part "R-US_R0402"))
    )
    (comp (ref "R115")
      (value "1.5k, 1%")
      (footprint "eagle-import:R0402")
      (libsource (lib "eagle-import") (part "R-US_R0402"))
    )
    (comp (ref "R118")
      (value "1.5k, 1%")
      (footprint "eagle-import:R0402")
      (libsource (lib "eagle-import") (part "R-US_R0402"))
    )
    (comp (ref "R119")
      (value "10k, 1%")
      (footprint "eagle-import:R0402")
      (libsource (lib "eagle-import") (part "R-US_R0402"))
    )
    (comp (ref "R120")
      (value "27k, 1%")
      (footprint "eagle-import:R0402")
      (libsource (lib "eagle-import") (part "R-US_R0402"))
    )
    (comp (ref "R121")
      (value "10k, 1%")
      (footprint "eagle-import:R0402")
      (libsource (lib "eagle-import") (part "R-US_R0402"))
    )
    (comp (ref "R122")
      (value "0, 1%")
      (footprint "eagle-import:R0402")
      (libsource (lib "eagle-import") (part "R-US_R0402"))
    )
    (comp (ref "R123")
      (value "100k, 1%")
      (footprint "eagle-import:R0402")
      (libsource (lib "eagle-import") (part "R-US_R0402"))
    )
    (comp (ref "R124")
      (value "1k")
      (footprint "eagle-import:R0402")
      (libsource (lib "eagle-import") (part "R-US_R0402"))
    )
    (comp (ref "R125")
      (value "1k")
      (footprint "eagle-import:R0402")
      (libsource (lib "eagle-import") (part "R-US_R0402"))
    )
    (comp (ref "R126")
      (value "33, 5%")
      (footprint "eagle-import:R0603")
      (libsource (lib "eagle-import") (part "rcl_334_R-US_R0603"))
    )
    (comp (ref "R127")
      (value "33, 5%")
      (footprint "eagle-import:R0603")
      (libsource (lib "eagle-import") (part "rcl_334_R-US_R0603"))
    )
    (comp (ref "R128")
      (value "33, 5%")
      (footprint "eagle-import:R0603")
      (libsource (lib "eagle-import") (part "rcl_334_R-US_R0603"))
    )
    (comp (ref "R129")
      (value "33, 5%")
      (footprint "eagle-import:R0603")
      (libsource (lib "eagle-import") (part "rcl_334_R-US_R0603"))
    )
    (comp (ref "R130")
      (value "33, 5%")
      (footprint "eagle-import:R0603")
      (libsource (lib "eagle-import") (part "rcl_334_R-US_R0603"))
    )
    (comp (ref "R131")
      (value "33, 5%")
      (footprint "eagle-import:R0603")
      (libsource (lib "eagle-import") (part "rcl_334_R-US_R0603"))
    )
    (comp (ref "R134")
      (value "33, 5%")
      (footprint "eagle-import:R0603")
      (libsource (lib "eagle-import") (part "rcl_334_R-US_R0603"))
    )
    (comp (ref "R135")
      (value "33, 5%")
      (footprint "eagle-import:R0603")
      (libsource (lib "eagle-import") (part "rcl_334_R-US_R0603"))
    )
    (comp (ref "R136")
      (value "33, 5%")
      (footprint "eagle-import:R0603")
      (libsource (lib "eagle-import") (part "rcl_334_R-US_R0603"))
    )
    (comp (ref "R140")
      (value "33, 5%")
      (footprint "eagle-import:R0402")
      (libsource (lib "eagle-import") (part "R-US_R0402"))
    )
    (comp (ref "R141")
      (value "33, 5%")
      (footprint "eagle-import:R0402")
      (libsource (lib "eagle-import") (part "R-US_R0402"))
    )
    (comp (ref "R142")
      (value "33, 5%")
      (footprint "eagle-import:R0402")
      (libsource (lib "eagle-import") (part "R-US_R0402"))
    )
    (comp (ref "R143")
      (value "33, 5%")
      (footprint "eagle-import:R0402")
      (libsource (lib "eagle-import") (part "R-US_R0402"))
    )
    (comp (ref "RESET")
      (value "GHI2_MINI_PUSHBUTTON")
      (footprint "eagle-import:GHI2_MINI_PUSHBUTTON")
      (libsource (lib "eagle-import") (part "GHI2_MINI_PUSHBUTTON"))
    )
    (comp (ref "S2")
      (value "GHI2_MINI_PUSHBUTTON")
      (footprint "eagle-import:GHI2_MINI_PUSHBUTTON")
      (libsource (lib "eagle-import") (part "GHI2_MINI_PUSHBUTTON"))
    )
    (comp (ref "T1")
      (value "MMBT2907")
      (footprint "eagle-import:SOT23-BEC")
      (libsource (lib "eagle-import") (part "MMBT2907SMDALT1"))
    )
    (comp (ref "T2")
      (value "DNP MMBT2907")
      (footprint "eagle-import:SOT23-BEC")
      (libsource (lib "eagle-import") (part "MMBT2907SMDALT1"))
    )
    (comp (ref "T3")
      (value "BSS138W-7-F")
      (footprint "eagle-import:GHI-TRANSISTORS_SOT-323(DIODES)")
      (libsource (lib "eagle-import") (part "GHI-TRANSISTORS_BSS138W-7-F"))
    )
    (comp (ref "T4")
      (value "BSS138W-7-F")
      (footprint "eagle-import:GHI-TRANSISTORS_SOT-323(DIODES)")
      (libsource (lib "eagle-import") (part "GHI-TRANSISTORS_BSS138W-7-F"))
    )
    (comp (ref "TP1")
      (value "GHI2_TESTPAD/W_HOLE_1X1")
      (footprint "eagle-import:GHI2_TESTPAD_W_HOLE_1X1")
      (libsource (lib "eagle-import") (part "GHI2_TESTPAD/W_HOLE_1X1"))
    )
    (comp (ref "TP2")
      (value "GHI2_TESTPAD/W_HOLE_1X1")
      (footprint "eagle-import:GHI2_TESTPAD_W_HOLE_1X1")
      (libsource (lib "eagle-import") (part "GHI2_TESTPAD/W_HOLE_1X1"))
    )
    (comp (ref "TP3")
      (value "GHI2_TESTPAD/W_HOLE_1X1")
      (footprint "eagle-import:GHI2_TESTPAD_W_HOLE_1X1")
      (libsource (lib "eagle-import") (part "GHI2_TESTPAD/W_HOLE_1X1"))
    )
    (comp (ref "TP4")
      (value "GHI2_TESTPAD/W_HOLE_1X1")
      (footprint "eagle-import:GHI2_TESTPAD_W_HOLE_1X1")
      (libsource (lib "eagle-import") (part "GHI2_TESTPAD/W_HOLE_1X1"))
    )
    (comp (ref "TP5")
      (value "GHI2_TESTPAD/W_HOLE_1X1")
      (footprint "eagle-import:GHI2_TESTPAD_W_HOLE_1X1")
      (libsource (lib "eagle-import") (part "GHI2_TESTPAD/W_HOLE_1X1"))
    )
    (comp (ref "TP6")
      (value "PTR1B1,27")
      (footprint "eagle-import:B1,27")
      (libsource (lib "eagle-import") (part "PTR1B1,27"))
    )
    (comp (ref "TP12")
      (value "PTR1B1,27")
      (footprint "eagle-import:B1,27")
      (libsource (lib "eagle-import") (part "PTR1B1,27"))
    )
    (comp (ref "TP13")
      (value "PTR1B1,27")
      (footprint "eagle-import:B1,27")
      (libsource (lib "eagle-import") (part "PTR1B1,27"))
    )
    (comp (ref "TP14")
      (value "PTR1B1,27")
      (footprint "eagle-import:B1,27")
      (libsource (lib "eagle-import") (part "PTR1B1,27"))
    )
    (comp (ref "TP15")
      (value "PTR1B1,27")
      (footprint "eagle-import:B1,27")
      (libsource (lib "eagle-import") (part "PTR1B1,27"))
    )
    (comp (ref "TP16")
      (value "PTR1B1,27")
      (footprint "eagle-import:B1,27")
      (libsource (lib "eagle-import") (part "PTR1B1,27"))
    )
    (comp (ref "TP17")
      (value "PTR1B1,27")
      (footprint "eagle-import:B1,27")
      (libsource (lib "eagle-import") (part "PTR1B1,27"))
    )
    (comp (ref "TP18")
      (value "PTR1B1,27")
      (footprint "eagle-import:B1,27")
      (libsource (lib "eagle-import") (part "PTR1B1,27"))
    )
    (comp (ref "TP19")
      (value "PTR1B1,27")
      (footprint "eagle-import:B1,27")
      (libsource (lib "eagle-import") (part "PTR1B1,27"))
    )
    (comp (ref "TP23")
      (value "PTR1B1,27")
      (footprint "eagle-import:B1,27")
      (libsource (lib "eagle-import") (part "PTR1B1,27"))
    )
    (comp (ref "USR0")
      (value "LTST-C191TBKT")
      (footprint "eagle-import:GHI-BASICCOMPONENTS_0603-LED")
      (libsource (lib "eagle-import") (part "GHI-BASICCOMPONENTS_LED-(INCH)-0603"))
    )
    (comp (ref "USR1")
      (value "LTST-C191TBKT")
      (footprint "eagle-import:GHI-BASICCOMPONENTS_0603-LED")
      (libsource (lib "eagle-import") (part "GHI-BASICCOMPONENTS_LED-(INCH)-0603"))
    )
    (comp (ref "USR2")
      (value "LTST-C191TBKT")
      (footprint "eagle-import:GHI-BASICCOMPONENTS_0603-LED")
      (libsource (lib "eagle-import") (part "GHI-BASICCOMPONENTS_LED-(INCH)-0603"))
    )
    (comp (ref "USR3")
      (value "LTST-C191TBKT")
      (footprint "eagle-import:GHI-BASICCOMPONENTS_0603-LED")
      (libsource (lib "eagle-import") (part "GHI-BASICCOMPONENTS_LED-(INCH)-0603"))
    )
    (comp (ref "WL")
      (value "LTST-C191TBKT")
      (footprint "eagle-import:GHI-BASICCOMPONENTS_0603-LED")
      (libsource (lib "eagle-import") (part "GHI-BASICCOMPONENTS_LED-(INCH)-0603"))
    )
    (comp (ref "X1")
      (value "GHI-HEADERS_1X6-(INCH)-0.1-TH")
      (footprint "eagle-import:GHI-HEADERS_TH-1X6")
      (libsource (lib "eagle-import") (part "GHI-HEADERS_1X6-(INCH)-0.1-TH"))
    )
    (comp (ref "X2")
      (value "SCHA5B0200")
      (footprint "eagle-import:GHI-CONNECTORS_SCHA5B0200")
      (libsource (lib "eagle-import") (part "GHI-CONNECTORS_SCHA5B0200(ALPS_USD)"))
    )
    (comp (ref "X3")
      (value "GHI2_USB_HOST_W/CHASSIS_GND")
      (footprint "eagle-import:GHI2_USB_HOST_HORIZONTAL_W_CHASSIS_GND")
      (libsource (lib "eagle-import") (part "GHI2_USB_HOST_W/CHASSIS_GND"))
    )
    (comp (ref "X4")
      (value "10118192-0001LF")
      (footprint "eagle-import:GHI-CONNECTORS_10118192-0001LF(MICRO-USB-B-AMPHENOL-FCI)")
      (libsource (lib "eagle-import") (part "GHI-CONNECTORS_10118192-0001LF"))
    )
    (comp (ref "X5")
      (value "10118241-001RLF")
      (footprint "eagle-import:GHI-CONNECTORS_HDMI-TYPE-D-10118241")
      (libsource (lib "eagle-import") (part "GHI-CONNECTORS_HDMI-TYPE-D-10118241"))
    )
    (comp (ref "X12")
      (value "GHI-CONNECTORS_PJ-102B_POWER_CON")
      (footprint "eagle-import:GHI-CONNECTORS_PJ-102B_POWER_CON")
      (libsource (lib "eagle-import") (part "GHI-CONNECTORS_PJ-102B_POWER_CON"))
    )
  )
  (nets
    (net (code "1") (name "/5V_IN") (class "Default")
      (node (ref "C19") (pin "1") (pinfunction "1_1") (pintype "passive"))
      (node (ref "D8") (pin "3") (pinfunction "CC_3") (pintype "passive"))
      (node (ref "FB1") (pin "2") (pinfunction "P$2_2") (pintype "bidirectional"))
      (node (ref "IC18") (pin "2") (pinfunction "IN_2") (pintype "bidirectional"))
      (node (ref "R95") (pin "1") (pinfunction "1_1") (pintype "passive"))
    )
    (net (code "2") (name "/12MHZ") (class "Default")
      (node (ref "FB6") (pin "2") (pinfunction "2_2") (pintype "passive"))
      (node (ref "IC9") (pin "27") (pinfunction "OSC_IN/AP3_27") (pintype "bidirectional"))
    )
    (net (code "3") (name "/12M_LOOP") (class "Default")
      (node (ref "IC13") (pin "2") (pinfunction "D_2") (pintype "bidirectional"))
      (node (ref "IC13") (pin "3") (pinfunction "Q#_3") (pintype "bidirectional"))
    )
    (net (code "4") (name "/32.768KHZ") (class "Default")
      (node (ref "MOD1") (pin "36") (pinfunction "EXT_32K_36") (pintype "bidirectional"))
      (node (ref "OSC2") (pin "3") (pinfunction "OUT_3") (pintype "bidirectional"))
      (node (ref "R91") (pin "2") (pinfunction "2_2") (pintype "passive"))
    )
    (net (code "5") (name "/AIN0") (class "Default")
      (node (ref "IC1") (pin "B6") (pinfunction "AIN0_B6") (pintype "bidirectional"))
      (node (ref "P9") (pin "39") (pinfunction "39_39") (pintype "passive"))
    )
    (net (code "6") (name "/AIN1") (class "Default")
      (node (ref "IC1") (pin "C7") (pinfunction "AIN1_C7") (pintype "bidirectional"))
      (node (ref "P9") (pin "40") (pinfunction "40_40") (pintype "passive"))
    )
    (net (code "7") (name "/AIN2") (class "Default")
      (node (ref "IC1") (pin "B7") (pinfunction "AIN2_B7") (pintype "bidirectional"))
      (node (ref "P9") (pin "37") (pinfunction "37_37") (pintype "passive"))
    )
    (net (code "8") (name "/AIN3") (class "Default")
      (node (ref "IC1") (pin "A7") (pinfunction "AIN3_A7") (pintype "bidirectional"))
      (node (ref "P9") (pin "38") (pinfunction "38_38") (pintype "passive"))
    )
    (net (code "9") (name "/AIN4") (class "Default")
      (node (ref "IC1") (pin "C8") (pinfunction "AIN4_C8") (pintype "bidirectional"))
      (node (ref "P9") (pin "33") (pinfunction "33_33") (pintype "passive"))
    )
    (net (code "10") (name "/AIN5") (class "Default")
      (node (ref "IC1") (pin "B8") (pinfunction "AIN5_B8") (pintype "bidirectional"))
      (node (ref "P9") (pin "36") (pinfunction "36_36") (pintype "passive"))
    )
    (net (code "11") (name "/AIN6") (class "Default")
      (node (ref "IC1") (pin "A8") (pinfunction "AIN6_A8") (pintype "bidirectional"))
      (node (ref "P9") (pin "35") (pinfunction "35_35") (pintype "passive"))
    )
    (net (code "12") (name "/BAT_TEMP") (class "Default")
      (node (ref "IC1") (pin "W1") (pinfunction "BAT_TEMP_W1") (pintype "bidirectional"))
      (node (ref "TP4") (pin "P$1") (pinfunction "TP_P$1") (pintype "bidirectional"))
    )
    (net (code "13") (name "/BAT_VOLT") (class "Default")
      (node (ref "IC1") (pin "Y1") (pinfunction "BATT_VOLT_Y1") (pintype "bidirectional"))
      (node (ref "TP3") (pin "P$1") (pinfunction "TP_P$1") (pintype "bidirectional"))
    )
    (net (code "14") (name "/BT_EN") (class "Default")
      (node (ref "IC11") (pin "4") (pinfunction "A3_4") (pintype "bidirectional"))
      (node (ref "MOD1") (pin "41") (pinfunction "BT_EN_41") (pintype "bidirectional"))
      (node (ref "R11") (pin "1") (pinfunction "1_1") (pintype "passive"))
      (node (ref "T4") (pin "G") (pinfunction "G_G") (pintype "bidirectional"))
    )
    (net (code "15") (name "/BT_EN.SIP") (class "Default")
      (node (ref "IC1") (pin "K17") (pinfunction "MII1_TXD0_K17") (pintype "bidirectional"))
      (node (ref "R135") (pin "1") (pinfunction "1_1") (pintype "passive"))
    )
    (net (code "16") (name "/BT_HCI_CTS") (class "Default")
      (node (ref "IC11") (pin "8") (pinfunction "A7_8") (pintype "bidirectional"))
      (node (ref "R141") (pin "2") (pinfunction "2_2") (pintype "passive"))
    )
    (net (code "17") (name "/BT_HCI_CTS.SIP") (class "Default")
      (node (ref "IC1") (pin "M17") (pinfunction "MDIO_DATA_M17") (pintype "bidirectional"))
      (node (ref "IC11") (pin "15") (pinfunction "B5_15") (pintype "bidirectional"))
      (node (ref "R108") (pin "1") (pinfunction "1_1") (pintype "passive"))
    )
    (net (code "18") (name "/BT_HCI_RTS") (class "Default")
      (node (ref "IC11") (pin "6") (pinfunction "A5_6") (pintype "bidirectional"))
      (node (ref "R140") (pin "2") (pinfunction "2_2") (pintype "passive"))
    )
    (net (code "19") (name "/BT_HCI_RTS.SIP") (class "Default")
      (node (ref "IC1") (pin "M18") (pinfunction "MDIO_CLK_M18") (pintype "bidirectional"))
      (node (ref "IC11") (pin "13") (pinfunction "B7_13") (pintype "bidirectional"))
      (node (ref "R109") (pin "1") (pinfunction "1_1") (pintype "passive"))
    )
    (net (code "20") (name "/BT_HCI_RX") (class "Default")
      (node (ref "IC11") (pin "1") (pinfunction "A1_1") (pintype "bidirectional"))
      (node (ref "R143") (pin "2") (pinfunction "2_2") (pintype "passive"))
    )
    (net (code "21") (name "/BT_HCI_RX.SIP") (class "Default")
      (node (ref "IC1") (pin "L17") (pinfunction "MII1_RXD3_L17") (pintype "bidirectional"))
      (node (ref "IC11") (pin "14") (pinfunction "B6_14") (pintype "bidirectional"))
    )
    (net (code "22") (name "/BT_HCI_TX") (class "Default")
      (node (ref "IC11") (pin "7") (pinfunction "A6_7") (pintype "bidirectional"))
      (node (ref "R142") (pin "2") (pinfunction "2_2") (pintype "passive"))
    )
    (net (code "23") (name "/BT_HCI_TX.SIP") (class "Default")
      (node (ref "IC1") (pin "L16") (pinfunction "MII1_RXD2_L16") (pintype "bidirectional"))
      (node (ref "IC11") (pin "20") (pinfunction "B1_20") (pintype "bidirectional"))
    )
    (net (code "24") (name "/CEC") (class "Default")
      (node (ref "D1") (pin "C") (pinfunction "CATHODE_C") (pintype "bidirectional"))
      (node (ref "IC9") (pin "30") (pinfunction "CEC_30") (pintype "bidirectional"))
      (node (ref "X5") (pin "15") (pinfunction "CEC_15") (pintype "bidirectional"))
    )
    (net (code "25") (name "/CLKOUT2") (class "Default")
      (node (ref "FB7") (pin "1") (pinfunction "1_1") (pintype "passive"))
      (node (ref "IC11") (pin "16") (pinfunction "B4_16") (pintype "bidirectional"))
      (node (ref "P2") (pin "18") (pinfunction "EMU3_18") (pintype "bidirectional"))
      (node (ref "P9") (pin "41") (pinfunction "41_41") (pintype "passive"))
      (node (ref "R14") (pin "1") (pinfunction "1_1") (pintype "passive"))
    )
    (net (code "26") (name "/DVI_5V") (class "Default")
      (node (ref "F1") (pin "1") (pinfunction "1_1") (pintype "passive"))
      (node (ref "R115") (pin "1") (pinfunction "1_1") (pintype "passive"))
      (node (ref "R118") (pin "1") (pinfunction "1_1") (pintype "passive"))
      (node (ref "X5") (pin "19") (pinfunction "5V_19") (pintype "bidirectional"))
    )
    (net (code "27") (name "/EHRPWM1A") (class "Default")
      (node (ref "IC1") (pin "U14") (pinfunction "EHRPWM1A_U14") (pintype "bidirectional"))
      (node (ref "P9") (pin "14") (pinfunction "14_14") (pintype "passive"))
    )
    (net (code "28") (name "/EHRPWM1B") (class "Default")
      (node (ref "IC1") (pin "T14") (pinfunction "EHRPWM1B_T14") (pintype "bidirectional"))
      (node (ref "P9") (pin "16") (pinfunction "16_16") (pintype "passive"))
    )
    (net (code "29") (name "/EHRPWM2A") (class "Default")
      (node (ref "IC1") (pin "U10") (pinfunction "EHRPWM2A_U10") (pintype "bidirectional"))
      (node (ref "P8") (pin "19") (pinfunction "19_19") (pintype "passive"))
    )
    (net (code "30") (name "/EHRPWM2B") (class "Default")
      (node (ref "IC1") (pin "T10") (pinfunction "EHRPWM2B_T10") (pintype "bidirectional"))
      (node (ref "P8") (pin "13") (pinfunction "13_13") (pintype "passive"))
    )
    (net (code "31") (name "/EMMC_RSTN") (class "Default")
      (node (ref "IC22") (pin "K5") (pinfunction "RST#_K5") (pintype "bidirectional"))
      (node (ref "R29") (pin "1") (pinfunction "1_1") (pintype "passive"))
      (node (ref "R33") (pin "1") (pinfunction "1_1") (pintype "passive"))
    )
    (net (code "32") (name "/EXT_SWING") (class "Default")
      (node (ref "IC9") (pin "34") (pinfunction "EXT_SWING_34") (pintype "bidirectional"))
      (node (ref "R119") (pin "1") (pinfunction "1_1") (pintype "passive"))
    )
    (net (code "33") (name "/GPIO0_7") (class "Default")
      (node (ref "P9") (pin "42") (pinfunction "42_42") (pintype "passive"))
      (node (ref "R36") (pin "1") (pinfunction "1_1") (pintype "passive"))
      (node (ref "R38") (pin "1") (pinfunction "1_1") (pintype "passive"))
    )
    (net (code "34") (name "/GPIO0_26") (class "Default")
      (node (ref "IC1") (pin "T11") (pinfunction "GPIO0_26_T11") (pintype "bidirectional"))
      (node (ref "P8") (pin "14") (pinfunction "14_14") (pintype "passive"))
    )
    (net (code "35") (name "/GPIO0_27") (class "Default")
      (node (ref "IC1") (pin "U12") (pinfunction "GPIO0_27_U12") (pintype "bidirectional"))
      (node (ref "P8") (pin "17") (pinfunction "17_17") (pintype "passive"))
    )
    (net (code "36") (name "/GPIO1_12") (class "Default")
      (node (ref "IC1") (pin "T12") (pinfunction "GPIO1_12_T12") (pintype "bidirectional"))
      (node (ref "P8") (pin "12") (pinfunction "12_12") (pintype "passive"))
    )
    (net (code "37") (name "/GPIO1_13") (class "Default")
      (node (ref "IC1") (pin "R12") (pinfunction "GPIO1_13_R12") (pintype "bidirectional"))
      (node (ref "P8") (pin "11") (pinfunction "11_11") (pintype "passive"))
    )
    (net (code "38") (name "/GPIO1_14") (class "Default")
      (node (ref "IC1") (pin "V13") (pinfunction "GPIO1_14_V13") (pintype "bidirectional"))
      (node (ref "P8") (pin "16") (pinfunction "16_16") (pintype "passive"))
    )
    (net (code "39") (name "/GPIO1_15") (class "Default")
      (node (ref "IC1") (pin "U13") (pinfunction "GPIO1_15_U13") (pintype "bidirectional"))
      (node (ref "P8") (pin "15") (pinfunction "15_15") (pintype "passive"))
    )
    (net (code "40") (name "/GPIO1_16") (class "Default")
      (node (ref "P9") (pin "15") (pinfunction "15_15") (pintype "passive"))
      (node (ref "R54") (pin "1") (pinfunction "1_1") (pintype "passive"))
    )
    (net (code "41") (name "/GPIO1_16.SIP") (class "Default")
      (node (ref "IC1") (pin "R13") (pinfunction "GPIO1_16_R13") (pintype "bidirectional"))
      (node (ref "R54") (pin "2") (pinfunction "2_2") (pintype "passive"))
    )
    (net (code "42") (name "/GPIO1_17") (class "Default")
      (node (ref "IC1") (pin "V14") (pinfunction "GPIO1_17_V14") (pintype "bidirectional"))
      (node (ref "P9") (pin "23") (pinfunction "23_23") (pintype "passive"))
    )
    (net (code "43") (name "/GPIO1_28") (class "Default")
      (node (ref "IC1") (pin "U18") (pinfunction "GPIO1_28_U18") (pintype "bidirectional"))
      (node (ref "P9") (pin "12") (pinfunction "12_12") (pintype "passive"))
    )
    (net (code "44") (name "/GPIO1_29") (class "Default")
      (node (ref "IC1") (pin "V6") (pinfunction "GPIO1_29_V6") (pintype "bidirectional"))
      (node (ref "P8") (pin "26") (pinfunction "26_26") (pintype "passive"))
    )
    (net (code "45") (name "/GPIO2_0.SIP") (class "Default")
      (node (ref "IC1") (pin "T13") (pinfunction "GPIO2_0_T13") (pintype "bidirectional"))
    )
    (net (code "46") (name "/GPIO2_1") (class "Default")
      (node (ref "IC1") (pin "V12") (pinfunction "GPIO2_1_V12") (pintype "bidirectional"))
      (node (ref "P8") (pin "18") (pinfunction "18_18") (pintype "passive"))
    )
    (net (code "47") (name "/GPIO3_19") (class "Default")
      (node (ref "IC1") (pin "C13") (pinfunction "GPIO3_19_C13") (pintype "bidirectional"))
      (node (ref "P9") (pin "27") (pinfunction "27_27") (pintype "passive"))
    )
    (net (code "48") (name "/GPIO3_21") (class "Default")
      (node (ref "IC1") (pin "A14") (pinfunction "GPIO3_21_A14") (pintype "bidirectional"))
      (node (ref "P9") (pin "25") (pinfunction "25_25") (pintype "passive"))
      (node (ref "R110") (pin "2") (pinfunction "2_2") (pintype "passive"))
    )
    (net (code "49") (name "/HDMICLK_DIS#") (class "Default")
      (node (ref "IC1") (pin "V17") (pinfunction "(HDMICLK_DISN)GPIO1_27_V17") (pintype "bidirectional"))
      (node (ref "OSC1") (pin "1") (pinfunction "INH#_1") (pintype "bidirectional"))
    )
    (net (code "50") (name "/HDMI_INT") (class "Default")
      (node (ref "IC1") (pin "U16") (pinfunction "(HDMI_INT)GPIO1_25_U16") (pintype "bidirectional"))
      (node (ref "IC9") (pin "50") (pinfunction "INT_50") (pintype "bidirectional"))
      (node (ref "R121") (pin "2") (pinfunction "2_2") (pintype "passive"))
    )
    (net (code "51") (name "/HPD") (class "Default")
      (node (ref "IC9") (pin "31") (pinfunction "HPD_31") (pintype "bidirectional"))
      (node (ref "X5") (pin "1") (pinfunction "HOT.PLUG.DETECT_1") (pintype "bidirectional"))
    )
    (net (code "52") (name "/I2C0_SCL") (class "Default")
      (node (ref "IC1") (pin "C16") (pinfunction "I2C0_SCL_C16") (pintype "bidirectional"))
      (node (ref "IC1") (pin "C20") (pinfunction "PMIC_I2C_SCL_C20") (pintype "bidirectional"))
      (node (ref "IC4") (pin "1") (pinfunction "SCL_1") (pintype "bidirectional"))
      (node (ref "IC9") (pin "52") (pinfunction "CSCL_52") (pintype "bidirectional"))
      (node (ref "R41") (pin "2") (pinfunction "2_2") (pintype "passive"))
    )
    (net (code "53") (name "/I2C0_SDA") (class "Default")
      (node (ref "IC1") (pin "C17") (pinfunction "I2C0_SDA_C17") (pintype "bidirectional"))
      (node (ref "IC1") (pin "C19") (pinfunction "PMIC_I2C_SDA_C19") (pintype "bidirectional"))
      (node (ref "IC4") (pin "3") (pinfunction "SDA_3") (pintype "bidirectional"))
      (node (ref "IC9") (pin "51") (pinfunction "CSDA_51") (pintype "bidirectional"))
      (node (ref "R42") (pin "2") (pinfunction "2_2") (pintype "passive"))
    )
    (net (code "54") (name "/I2C1_SCL") (class "Default")
      (node (ref "IC1") (pin "A16") (pinfunction "I2C1_SCL_A16") (pintype "bidirectional"))
      (node (ref "P9") (pin "17") (pinfunction "17_17") (pintype "passive"))
    )
    (net (code "55") (name "/I2C1_SDA") (class "Default")
      (node (ref "IC1") (pin "B16") (pinfunction "I2C1_SDA_B16") (pintype "bidirectional"))
      (node (ref "P9") (pin "18") (pinfunction "18_18") (pintype "passive"))
    )
    (net (code "56") (name "/I2C2_SCL") (class "Default")
      (node (ref "IC1") (pin "D17") (pinfunction "I2C2_SCL_D17") (pintype "bidirectional"))
      (node (ref "P9") (pin "19") (pinfunction "19_19") (pintype "passive"))
    )
    (net (code "57") (name "/I2C2_SDA") (class "Default")
      (node (ref "IC1") (pin "D18") (pinfunction "I2C2_SDA_D18") (pintype "bidirectional"))
      (node (ref "P9") (pin "20") (pinfunction "20_20") (pintype "passive"))
    )
    (net (code "58") (name "/JTAG_EMU0") (class "Default")
      (node (ref "IC1") (pin "C14") (pinfunction "JTAG_EMU0_C14") (pintype "bidirectional"))
      (node (ref "P2") (pin "13") (pinfunction "EMU0_13") (pintype "bidirectional"))
      (node (ref "R43") (pin "2") (pinfunction "2_2") (pintype "passive"))
    )
    (net (code "59") (name "/JTAG_EMU1") (class "Default")
      (node (ref "IC1") (pin "B14") (pinfunction "JTAG_EMU1_B14") (pintype "bidirectional"))
      (node (ref "P2") (pin "14") (pinfunction "EMU1_14") (pintype "bidirectional"))
      (node (ref "R53") (pin "2") (pinfunction "2_2") (pintype "passive"))
    )
    (net (code "60") (name "/JTAG_TCK") (class "Default")
      (node (ref "IC1") (pin "A12") (pinfunction "JTAG_TCK_A12") (pintype "bidirectional"))
      (node (ref "P2") (pin "11") (pinfunction "TCK_11") (pintype "bidirectional"))
      (node (ref "P2") (pin "9") (pinfunction "TCKRTN_9") (pintype "bidirectional"))
    )
    (net (code "61") (name "/JTAG_TDI") (class "Default")
      (node (ref "IC1") (pin "B11") (pinfunction "JTAG_TDI_B11") (pintype "bidirectional"))
      (node (ref "P2") (pin "3") (pinfunction "TDI_3") (pintype "bidirectional"))
    )
    (net (code "62") (name "/JTAG_TDO") (class "Default")
      (node (ref "IC1") (pin "A11") (pinfunction "JTAG_TDO_A11") (pintype "bidirectional"))
      (node (ref "P2") (pin "7") (pinfunction "TDO_7") (pintype "bidirectional"))
    )
    (net (code "63") (name "/JTAG_TMS") (class "Default")
      (node (ref "IC1") (pin "C11") (pinfunction "JTAG_TMS_C11") (pintype "bidirectional"))
      (node (ref "P2") (pin "1") (pinfunction "TMS_1") (pintype "bidirectional"))
    )
    (net (code "64") (name "/JTAG_TRSTN") (class "Default")
      (node (ref "IC1") (pin "B10") (pinfunction "JTAG_TRSTN_B10") (pintype "bidirectional"))
      (node (ref "P2") (pin "2") (pinfunction "TRST#_2") (pintype "bidirectional"))
      (node (ref "R52") (pin "1") (pinfunction "1_1") (pintype "passive"))
    )
    (net (code "65") (name "/LCD.CLOCK") (class "Default")
      (node (ref "IC9") (pin "4") (pinfunction "PCLK_4") (pintype "bidirectional"))
      (node (ref "P8") (pin "28") (pinfunction "28_28") (pintype "passive"))
      (node (ref "R34") (pin "1") (pinfunction "1_1") (pintype "passive"))
    )
    (net (code "66") (name "/LCD.D0.B0--B3") (class "Default")
      (node (ref "C42") (pin "1") (pinfunction "1_1") (pintype "passive"))
      (node (ref "IC1") (pin "R1") (pinfunction "LCD_DATA0_R1") (pintype "bidirectional"))
      (node (ref "IC9") (pin "15") (pinfunction "VPC[3]_15") (pintype "bidirectional"))
      (node (ref "P8") (pin "45") (pinfunction "45_45") (pintype "passive"))
      (node (ref "R87") (pin "2") (pinfunction "2_2") (pintype "passive"))
    )
    (net (code "67") (name "/LCD.D1.B1--B4") (class "Default")
      (node (ref "C41") (pin "1") (pinfunction "1_1") (pintype "passive"))
      (node (ref "IC1") (pin "R2") (pinfunction "LCD_DATA1_R2") (pintype "bidirectional"))
      (node (ref "IC9") (pin "13") (pinfunction "VPC[4]_13") (pintype "bidirectional"))
      (node (ref "P8") (pin "46") (pinfunction "46_46") (pintype "passive"))
      (node (ref "R85") (pin "2") (pinfunction "2_2") (pintype "passive"))
    )
    (net (code "68") (name "/LCD.D2.B2--B5") (class "Default")
      (node (ref "C40") (pin "1") (pinfunction "1_1") (pintype "passive"))
      (node (ref "IC1") (pin "R3") (pinfunction "LCD_DATA2_R3") (pintype "bidirectional"))
      (node (ref "IC9") (pin "12") (pinfunction "VPC[5]_12") (pintype "bidirectional"))
      (node (ref "P8") (pin "43") (pinfunction "43_43") (pintype "passive"))
      (node (ref "R82") (pin "1") (pinfunction "1_1") (pintype "passive"))
      (node (ref "R88") (pin "1") (pinfunction "1_1") (pintype "passive"))
    )
    (net (code "69") (name "/LCD.D3.B3--B6") (class "Default")
      (node (ref "C39") (pin "1") (pinfunction "1_1") (pintype "passive"))
      (node (ref "IC1") (pin "R4") (pinfunction "LCD_DATA3_R4") (pintype "bidirectional"))
      (node (ref "IC9") (pin "11") (pinfunction "VPC[6]_11") (pintype "bidirectional"))
      (node (ref "P8") (pin "44") (pinfunction "44_44") (pintype "passive"))
      (node (ref "R80") (pin "1") (pinfunction "1_1") (pintype "passive"))
    )
    (net (code "70") (name "/LCD.D4.B4--B7") (class "Default")
      (node (ref "C38") (pin "1") (pinfunction "1_1") (pintype "passive"))
      (node (ref "IC1") (pin "T1") (pinfunction "LCD_DATA4_T1") (pintype "bidirectional"))
      (node (ref "IC9") (pin "10") (pinfunction "VPC[7]_10") (pintype "bidirectional"))
      (node (ref "P8") (pin "41") (pinfunction "41_41") (pintype "passive"))
      (node (ref "R78") (pin "1") (pinfunction "1_1") (pintype "passive"))
    )
    (net (code "71") (name "/LCD.D5.G0--G2") (class "Default")
      (node (ref "C37") (pin "1") (pinfunction "1_1") (pintype "passive"))
      (node (ref "IC1") (pin "T2") (pinfunction "LCD_DATA5_T2") (pintype "bidirectional"))
      (node (ref "IC9") (pin "7") (pinfunction "VPB[2]_7") (pintype "bidirectional"))
      (node (ref "P8") (pin "42") (pinfunction "42_42") (pintype "passive"))
      (node (ref "R76") (pin "1") (pinfunction "1_1") (pintype "passive"))
    )
    (net (code "72") (name "/LCD.D6.G1--G3") (class "Default")
      (node (ref "C36") (pin "1") (pinfunction "1_1") (pintype "passive"))
      (node (ref "IC1") (pin "T3") (pinfunction "LCD_DATA6_T3") (pintype "bidirectional"))
      (node (ref "IC9") (pin "6") (pinfunction "VPB[3]_6") (pintype "bidirectional"))
      (node (ref "P8") (pin "39") (pinfunction "39_39") (pintype "passive"))
      (node (ref "R75") (pin "2") (pinfunction "2_2") (pintype "passive"))
    )
    (net (code "73") (name "/LCD.D7.G2--G4") (class "Default")
      (node (ref "C35") (pin "1") (pinfunction "1_1") (pintype "passive"))
      (node (ref "IC1") (pin "T4") (pinfunction "LCD_DATA7_T4") (pintype "bidirectional"))
      (node (ref "IC9") (pin "3") (pinfunction "VPB[4]_3") (pintype "bidirectional"))
      (node (ref "P8") (pin "40") (pinfunction "40_40") (pintype "passive"))
      (node (ref "R73") (pin "2") (pinfunction "2_2") (pintype "passive"))
    )
    (net (code "74") (name "/LCD.D8.G3--G5") (class "Default")
      (node (ref "C34") (pin "1") (pinfunction "1_1") (pintype "passive"))
      (node (ref "IC1") (pin "U1") (pinfunction "LCD_DATA8_U1") (pintype "bidirectional"))
      (node (ref "IC9") (pin "2") (pinfunction "VPB[5]_2") (pintype "bidirectional"))
      (node (ref "P8") (pin "37") (pinfunction "37_37") (pintype "passive"))
      (node (ref "R71") (pin "2") (pinfunction "2_2") (pintype "passive"))
    )
    (net (code "75") (name "/LCD.D9.G4--G6") (class "Default")
      (node (ref "C33") (pin "1") (pinfunction "1_1") (pintype "passive"))
      (node (ref "IC1") (pin "U2") (pinfunction "LCD_DATA9_U2") (pintype "bidirectional"))
      (node (ref "IC9") (pin "1") (pinfunction "VPB[6]_1") (pintype "bidirectional"))
      (node (ref "P8") (pin "38") (pinfunction "38_38") (pintype "passive"))
      (node (ref "R69") (pin "2") (pinfunction "2_2") (pintype "passive"))
    )
    (net (code "76") (name "/LCD.D10.G5--G7") (class "Default")
      (node (ref "C32") (pin "1") (pinfunction "1_1") (pintype "passive"))
      (node (ref "IC1") (pin "U3") (pinfunction "LCD_DATA10_U3") (pintype "bidirectional"))
      (node (ref "IC9") (pin "64") (pinfunction "VPB[7]_64") (pintype "bidirectional"))
      (node (ref "P8") (pin "36") (pinfunction "36_36") (pintype "passive"))
      (node (ref "R67") (pin "2") (pinfunction "2_2") (pintype "passive"))
    )
    (net (code "77") (name "/LCD.D11.R0--R3") (class "Default")
      (node (ref "C31") (pin "1") (pinfunction "1_1") (pintype "passive"))
      (node (ref "IC1") (pin "U4") (pinfunction "LCD_DATA11_U4") (pintype "bidirectional"))
      (node (ref "IC9") (pin "60") (pinfunction "VPA[3]_60") (pintype "bidirectional"))
      (node (ref "P8") (pin "34") (pinfunction "34_34") (pintype "passive"))
      (node (ref "R65") (pin "2") (pinfunction "2_2") (pintype "passive"))
    )
    (net (code "78") (name "/LCD.D12.R1--R4") (class "Default")
      (node (ref "C30") (pin "1") (pinfunction "1_1") (pintype "passive"))
      (node (ref "IC1") (pin "V2") (pinfunction "LCD_DATA12_V2") (pintype "bidirectional"))
      (node (ref "IC9") (pin "59") (pinfunction "VPA[4]_59") (pintype "bidirectional"))
      (node (ref "P8") (pin "35") (pinfunction "35_35") (pintype "passive"))
      (node (ref "R63") (pin "2") (pinfunction "2_2") (pintype "passive"))
    )
    (net (code "79") (name "/LCD.D13.R2--R5") (class "Default")
      (node (ref "C29") (pin "1") (pinfunction "1_1") (pintype "passive"))
      (node (ref "IC1") (pin "V3") (pinfunction "LCD_DATA13_V3") (pintype "bidirectional"))
      (node (ref "IC9") (pin "58") (pinfunction "VPA[5]_58") (pintype "bidirectional"))
      (node (ref "P8") (pin "33") (pinfunction "33_33") (pintype "passive"))
      (node (ref "R61") (pin "2") (pinfunction "2_2") (pintype "passive"))
    )
    (net (code "80") (name "/LCD.D14.R3--R6") (class "Default")
      (node (ref "C28") (pin "1") (pinfunction "1_1") (pintype "passive"))
      (node (ref "IC1") (pin "V4") (pinfunction "LCD_DATA14_V4") (pintype "bidirectional"))
      (node (ref "IC9") (pin "57") (pinfunction "VPA[6]_57") (pintype "bidirectional"))
      (node (ref "P8") (pin "31") (pinfunction "31_31") (pintype "passive"))
      (node (ref "R58") (pin "1") (pinfunction "1_1") (pintype "passive"))
    )
    (net (code "81") (name "/LCD.D15.R4--R7") (class "Default")
      (node (ref "C27") (pin "1") (pinfunction "1_1") (pintype "passive"))
      (node (ref "IC1") (pin "T5") (pinfunction "LCD_DATA15_T5") (pintype "bidirectional"))
      (node (ref "IC9") (pin "56") (pinfunction "VPA[7]_56") (pintype "bidirectional"))
      (node (ref "P8") (pin "32") (pinfunction "32_32") (pintype "passive"))
      (node (ref "R57") (pin "2") (pinfunction "2_2") (pintype "passive"))
    )
    (net (code "82") (name "/LCD.ENABLE") (class "Default")
      (node (ref "IC9") (pin "20") (pinfunction "DE/FREF_20") (pintype "bidirectional"))
      (node (ref "P8") (pin "30") (pinfunction "30_30") (pintype "passive"))
      (node (ref "R39") (pin "1") (pinfunction "1_1") (pintype "passive"))
    )
    (net (code "83") (name "/LCD.HSYNC") (class "Default")
      (node (ref "IC9") (pin "22") (pinfunction "HSYNC/HREF_22") (pintype "bidirectional"))
      (node (ref "P8") (pin "29") (pinfunction "29_29") (pintype "passive"))
      (node (ref "R37") (pin "1") (pinfunction "1_1") (pintype "passive"))
    )
    (net (code "84") (name "/LCD.VSYNC") (class "Default")
      (node (ref "IC9") (pin "21") (pinfunction "VSYNC/VREF_21") (pintype "bidirectional"))
      (node (ref "P8") (pin "27") (pinfunction "27_27") (pintype "passive"))
      (node (ref "R35") (pin "1") (pinfunction "1_1") (pintype "passive"))
    )
    (net (code "85") (name "/LDO_PGOOD") (class "Default")
      (node (ref "IC1") (pin "B20") (pinfunction "PMIC_LDO_PGOOD_B20") (pintype "bidirectional"))
      (node (ref "IC1") (pin "B5") (pinfunction "RTC_PORZ_B5") (pintype "bidirectional"))
    )
    (net (code "86") (name "/LS_BUF_OE") (class "Default")
      (node (ref "IC1") (pin "L18") (pinfunction "MII_RXCLK_L18") (pintype "bidirectional"))
      (node (ref "R131") (pin "2") (pinfunction "2_2") (pintype "passive"))
    )
    (net (code "87") (name "/MCU.LCD.CLK") (class "Default")
      (node (ref "IC1") (pin "V5") (pinfunction "LCD_PCLK_V5") (pintype "bidirectional"))
      (node (ref "R34") (pin "2") (pinfunction "2_2") (pintype "passive"))
    )
    (net (code "88") (name "/MCU.LCD.EN") (class "Default")
      (node (ref "IC1") (pin "R6") (pinfunction "LCD_DE_R6") (pintype "bidirectional"))
      (node (ref "R39") (pin "2") (pinfunction "2_2") (pintype "passive"))
    )
    (net (code "89") (name "/MCU.LCD.HS") (class "Default")
      (node (ref "IC1") (pin "R5") (pinfunction "LCD_HSYNC_R5") (pintype "bidirectional"))
      (node (ref "R37") (pin "2") (pinfunction "2_2") (pintype "passive"))
    )
    (net (code "90") (name "/MCU.LCD.VS") (class "Default")
      (node (ref "IC1") (pin "U5") (pinfunction "LCD_VSYNC_U5") (pintype "bidirectional"))
      (node (ref "R35") (pin "2") (pinfunction "2_2") (pintype "passive"))
    )
    (net (code "91") (name "/MMC1_CLK") (class "Default")
      (node (ref "IC1") (pin "U9") (pinfunction "MMC1_CLK_U9") (pintype "bidirectional"))
      (node (ref "IC22") (pin "M6") (pinfunction "CLK_M6") (pintype "bidirectional"))
      (node (ref "P8") (pin "21") (pinfunction "21_21") (pintype "passive"))
      (node (ref "R31") (pin "1") (pinfunction "1_1") (pintype "passive"))
    )
    (net (code "92") (name "/MMC1_CMD") (class "Default")
      (node (ref "IC1") (pin "V9") (pinfunction "MMC1_CMD_V9") (pintype "bidirectional"))
      (node (ref "IC22") (pin "M5") (pinfunction "CMD_M5") (pintype "bidirectional"))
      (node (ref "P8") (pin "20") (pinfunction "20_20") (pintype "passive"))
      (node (ref "R30") (pin "1") (pinfunction "1_1") (pintype "passive"))
    )
    (net (code "93") (name "/MMC1_DAT0") (class "Default")
      (node (ref "IC1") (pin "U7") (pinfunction "MMC1_DAT0_U7") (pintype "bidirectional"))
      (node (ref "IC22") (pin "A3") (pinfunction "DAT0_A3") (pintype "bidirectional"))
      (node (ref "P8") (pin "25") (pinfunction "25_25") (pintype "passive"))
      (node (ref "R12") (pin "1") (pinfunction "1_1") (pintype "passive"))
    )
    (net (code "94") (name "/MMC1_DAT1") (class "Default")
      (node (ref "IC1") (pin "V7") (pinfunction "MMC1_DAT1_V7") (pintype "bidirectional"))
      (node (ref "IC22") (pin "A4") (pinfunction "DAT1_A4") (pintype "bidirectional"))
      (node (ref "P8") (pin "24") (pinfunction "24_24") (pintype "passive"))
      (node (ref "R13") (pin "1") (pinfunction "1_1") (pintype "passive"))
    )
    (net (code "95") (name "/MMC1_DAT2") (class "Default")
      (node (ref "IC1") (pin "R8") (pinfunction "MMC1_DAT2_R8") (pintype "bidirectional"))
      (node (ref "IC22") (pin "A5") (pinfunction "DAT2_A5") (pintype "bidirectional"))
      (node (ref "P8") (pin "5") (pinfunction "5_5") (pintype "passive"))
      (node (ref "R16") (pin "1") (pinfunction "1_1") (pintype "passive"))
    )
    (net (code "96") (name "/MMC1_DAT3") (class "Default")
      (node (ref "IC1") (pin "T8") (pinfunction "MMC1_DAT3_T8") (pintype "bidirectional"))
      (node (ref "IC22") (pin "B2") (pinfunction "DAT3_B2") (pintype "bidirectional"))
      (node (ref "P8") (pin "6") (pinfunction "6_6") (pintype "passive"))
      (node (ref "R18") (pin "1") (pinfunction "1_1") (pintype "passive"))
    )
    (net (code "97") (name "/MMC1_DAT4") (class "Default")
      (node (ref "IC1") (pin "U8") (pinfunction "MMC1_DAT4_U8") (pintype "bidirectional"))
      (node (ref "IC22") (pin "B3") (pinfunction "DAT4_B3") (pintype "bidirectional"))
      (node (ref "P8") (pin "23") (pinfunction "23_23") (pintype "passive"))
      (node (ref "R20") (pin "1") (pinfunction "1_1") (pintype "passive"))
    )
    (net (code "98") (name "/MMC1_DAT5") (class "Default")
      (node (ref "IC1") (pin "V8") (pinfunction "MMC1_DAT5_V8") (pintype "bidirectional"))
      (node (ref "IC22") (pin "B4") (pinfunction "DAT5_B4") (pintype "bidirectional"))
      (node (ref "P8") (pin "22") (pinfunction "22_22") (pintype "passive"))
      (node (ref "R23") (pin "1") (pinfunction "1_1") (pintype "passive"))
    )
    (net (code "99") (name "/MMC1_DAT6") (class "Default")
      (node (ref "IC1") (pin "R9") (pinfunction "MMC1_DAT6_R9") (pintype "bidirectional"))
      (node (ref "IC22") (pin "B5") (pinfunction "DAT6_B5") (pintype "bidirectional"))
      (node (ref "P8") (pin "3") (pinfunction "3_3") (pintype "passive"))
      (node (ref "R25") (pin "1") (pinfunction "1_1") (pintype "passive"))
    )
    (net (code "100") (name "/MMC1_DAT7") (class "Default")
      (node (ref "IC1") (pin "T9") (pinfunction "MMC1_DAT7_T9") (pintype "bidirectional"))
      (node (ref "IC22") (pin "B6") (pinfunction "DAT7_B6") (pintype "bidirectional"))
      (node (ref "P8") (pin "4") (pinfunction "4_4") (pintype "passive"))
      (node (ref "R28") (pin "1") (pinfunction "1_1") (pintype "passive"))
    )
    (net (code "101") (name "/NC1") (class "Default")
      (node (ref "IC1") (pin "K16") (pinfunction "MII1_TXD1_K16") (pintype "bidirectional"))
    )
    (net (code "102") (name "/NC2") (class "Default")
      (node (ref "IC1") (pin "H17") (pinfunction "MII1_CRS_DV_H17") (pintype "bidirectional"))
    )
    (net (code "103") (name "/NC3") (class "Default")
      (node (ref "IC1") (pin "M16") (pinfunction "MII1_RXD0_M16") (pintype "bidirectional"))
    )
    (net (code "104") (name "/NC4") (class "Default")
      (node (ref "IC1") (pin "J15") (pinfunction "MII1_RXERR_J15") (pintype "bidirectional"))
    )
    (net (code "105") (name "/PMIC_INT") (class "Default")
      (node (ref "IC1") (pin "B18") (pinfunction "EXTIN_B18") (pintype "bidirectional"))
      (node (ref "IC1") (pin "B19") (pinfunction "PMIC_INTN_B19") (pintype "bidirectional"))
    )
    (net (code "106") (name "/PMIC_NWAKEUP") (class "Default")
      (node (ref "IC1") (pin "A19") (pinfunction "PMIC_WAKEUPN_A19") (pintype "bidirectional"))
      (node (ref "IC1") (pin "C5") (pinfunction "EXT_WAKEUP_C5") (pintype "bidirectional"))
    )
    (net (code "107") (name "/PMIC_PGOOD") (class "Default")
      (node (ref "IC1") (pin "A20") (pinfunction "PMIC_PGOOD_A20") (pintype "bidirectional"))
      (node (ref "IC1") (pin "B15") (pinfunction "PORZ_B15") (pintype "bidirectional"))
      (node (ref "IC2") (pin "2") (pinfunction "A_2") (pintype "bidirectional"))
    )
    (net (code "108") (name "/PWR_BUT") (class "Default")
      (node (ref "IC1") (pin "D20") (pinfunction "PWR_BUT_D20") (pintype "bidirectional"))
      (node (ref "P9") (pin "9") (pinfunction "9_9") (pintype "passive"))
      (node (ref "POWER") (pin "3") (pinfunction "3_3") (pintype "bidirectional"))
      (node (ref "POWER") (pin "4") (pinfunction "4_4") (pintype "bidirectional"))
    )
    (net (code "109") (name "/RX<-TX") (class "Default")
      (node (ref "IC17") (pin "3") (pinfunction "2Y_3") (pintype "bidirectional"))
      (node (ref "X1") (pin "5") (pinfunction "5_5") (pintype "passive"))
    )
    (net (code "110") (name "/SD.CD") (class "Default")
      (node (ref "IC1") (pin "C15") (pinfunction "MMC0_CD_C15") (pintype "bidirectional"))
      (node (ref "P2") (pin "19") (pinfunction "EMU4_19") (pintype "bidirectional"))
      (node (ref "R7") (pin "1") (pinfunction "1_1") (pintype "passive"))
      (node (ref "X2") (pin "CD") (pinfunction "CD#_CD") (pintype "bidirectional"))
    )
    (net (code "111") (name "/SD.CLK") (class "Default")
      (node (ref "IC1") (pin "G17") (pinfunction "MMC0_CLK0_G17") (pintype "bidirectional"))
      (node (ref "R3") (pin "1") (pinfunction "1_1") (pintype "passive"))
      (node (ref "X2") (pin "5") (pinfunction "CLK_5") (pintype "bidirectional"))
    )
    (net (code "112") (name "/SD.CMD") (class "Default")
      (node (ref "IC1") (pin "G18") (pinfunction "MMC0_CMD_G18") (pintype "bidirectional"))
      (node (ref "R4") (pin "1") (pinfunction "1_1") (pintype "passive"))
      (node (ref "X2") (pin "3") (pinfunction "CMD/DI_3") (pintype "bidirectional"))
    )
    (net (code "113") (name "/SD.D0") (class "Default")
      (node (ref "IC1") (pin "G16") (pinfunction "MMC0_DAT0_G16") (pintype "bidirectional"))
      (node (ref "R2") (pin "1") (pinfunction "1_1") (pintype "passive"))
      (node (ref "X2") (pin "7") (pinfunction "DAT0/DO_7") (pintype "bidirectional"))
    )
    (net (code "114") (name "/SD.D1") (class "Default")
      (node (ref "IC1") (pin "G15") (pinfunction "MMC0_DAT1_G15") (pintype "bidirectional"))
      (node (ref "R1") (pin "1") (pinfunction "1_1") (pintype "passive"))
      (node (ref "X2") (pin "8") (pinfunction "DAT1_8") (pintype "bidirectional"))
    )
    (net (code "115") (name "/SD.D2") (class "Default")
      (node (ref "IC1") (pin "F18") (pinfunction "MMC0_DAT2_F18") (pintype "bidirectional"))
      (node (ref "R6") (pin "1") (pinfunction "1_1") (pintype "passive"))
      (node (ref "X2") (pin "1") (pinfunction "DAT2_1") (pintype "bidirectional"))
    )
    (net (code "116") (name "/SD.D3") (class "Default")
      (node (ref "IC1") (pin "F17") (pinfunction "MMC0_DAT3_F17") (pintype "bidirectional"))
      (node (ref "R5") (pin "1") (pinfunction "1_1") (pintype "passive"))
      (node (ref "X2") (pin "2") (pinfunction "DAT3/CS_2") (pintype "bidirectional"))
    )
    (net (code "117") (name "/SELECT_5V") (class "Default")
      (node (ref "D2") (pin "K") (pinfunction "K_K") (pintype "bidirectional"))
      (node (ref "D3") (pin "K") (pinfunction "K_K") (pintype "bidirectional"))
      (node (ref "D4") (pin "K") (pinfunction "K_K") (pintype "bidirectional"))
      (node (ref "FB1") (pin "1") (pinfunction "P$1_1") (pintype "bidirectional"))
      (node (ref "R97") (pin "1") (pinfunction "1_1") (pintype "passive"))
      (node (ref "TP23") (pin "TP") (pinfunction "TP_TP") (pintype "input"))
    )
    (net (code "118") (name "/SLOW_CLK") (class "Default")
      (node (ref "IC11") (pin "5") (pinfunction "A4_5") (pintype "bidirectional"))
      (node (ref "R91") (pin "1") (pinfunction "1_1") (pintype "passive"))
    )
    (net (code "119") (name "/SPI1_CS0") (class "Default")
      (node (ref "IC1") (pin "C12") (pinfunction "SPI1_CS0_C12") (pintype "bidirectional"))
      (node (ref "IC9") (pin "25") (pinfunction "AP1_25") (pintype "bidirectional"))
      (node (ref "P9") (pin "28") (pinfunction "28_28") (pintype "passive"))
    )
    (net (code "120") (name "/SPI1_D0") (class "Default")
      (node (ref "IC1") (pin "B13") (pinfunction "SPI1_D0_B13") (pintype "bidirectional"))
      (node (ref "IC9") (pin "24") (pinfunction "AP0_24") (pintype "bidirectional"))
      (node (ref "P9") (pin "29") (pinfunction "29_29") (pintype "passive"))
    )
    (net (code "121") (name "/SPI1_D1") (class "Default")
      (node (ref "IC1") (pin "D12") (pinfunction "SPI1_D1_D12") (pintype "bidirectional"))
      (node (ref "P9") (pin "30") (pinfunction "30_30") (pintype "passive"))
    )
    (net (code "122") (name "/SPI1_SCLK") (class "Default")
      (node (ref "IC1") (pin "A13") (pinfunction "SPI1_CLK_A13") (pintype "bidirectional"))
      (node (ref "IC9") (pin "23") (pinfunction "ACLK_23") (pintype "bidirectional"))
      (node (ref "P9") (pin "31") (pinfunction "31_31") (pintype "passive"))
    )
    (net (code "123") (name "/SYS_RESET#") (class "Default")
      (node (ref "C16") (pin "1") (pinfunction "1_1") (pintype "passive"))
      (node (ref "C21") (pin "1") (pinfunction "1_1") (pintype "passive"))
      (node (ref "IC1") (pin "A10") (pinfunction "SYS_RESETN_A10") (pintype "bidirectional"))
      (node (ref "IC2") (pin "4") (pinfunction "Y_4") (pintype "bidirectional"))
      (node (ref "P2") (pin "15") (pinfunction "SRST_15") (pintype "bidirectional"))
      (node (ref "P9") (pin "10") (pinfunction "10_10") (pintype "passive"))
      (node (ref "R32") (pin "2") (pinfunction "2_2") (pintype "passive"))
      (node (ref "RESET") (pin "3") (pinfunction "3_3") (pintype "bidirectional"))
      (node (ref "RESET") (pin "4") (pinfunction "4_4") (pintype "bidirectional"))
    )
    (net (code "124") (name "/TEST") (class "Default")
      (node (ref "IC9") (pin "49") (pinfunction "TEST_49") (pintype "bidirectional"))
      (node (ref "R114") (pin "2") (pinfunction "2_2") (pintype "passive"))
    )
    (net (code "125") (name "/TIMER4") (class "Default")
      (node (ref "IC1") (pin "R7") (pinfunction "TIMER4_R7") (pintype "bidirectional"))
      (node (ref "P8") (pin "7") (pinfunction "7_7") (pintype "passive"))
    )
    (net (code "126") (name "/TIMER5") (class "Default")
      (node (ref "IC1") (pin "T6") (pinfunction "TIMER5_T6") (pintype "bidirectional"))
      (node (ref "P8") (pin "9") (pinfunction "9_9") (pintype "passive"))
    )
    (net (code "127") (name "/TIMER6") (class "Default")
      (node (ref "IC1") (pin "U6") (pinfunction "TIMER6_U6") (pintype "bidirectional"))
      (node (ref "P8") (pin "10") (pinfunction "10_10") (pintype "passive"))
    )
    (net (code "128") (name "/TIMER7") (class "Default")
      (node (ref "IC1") (pin "T7") (pinfunction "TIMER7_T7") (pintype "bidirectional"))
      (node (ref "P8") (pin "8") (pinfunction "8_8") (pintype "passive"))
    )
    (net (code "129") (name "/TX->RX") (class "Default")
      (node (ref "IC17") (pin "2") (pinfunction "1A_2") (pintype "bidirectional"))
      (node (ref "R123") (pin "1") (pinfunction "1_1") (pintype "passive"))
      (node (ref "X1") (pin "4") (pinfunction "4_4") (pintype "passive"))
    )
    (net (code "130") (name "/TX0+") (class "Default")
      (node (ref "IC8") (pin "5") (pinfunction "TMDS.CH2+_5") (pintype "bidirectional"))
      (node (ref "IC9") (pin "40") (pinfunction "TX0+_40") (pintype "bidirectional"))
      (node (ref "X5") (pin "9") (pinfunction "TMDS.DATA0+_9") (pintype "bidirectional"))
    )
    (net (code "131") (name "/TX0-") (class "Default")
      (node (ref "IC8") (pin "4") (pinfunction "TMDS.CH2-_4") (pintype "bidirectional"))
      (node (ref "IC9") (pin "39") (pinfunction "TX0-_39") (pintype "bidirectional"))
      (node (ref "X5") (pin "11") (pinfunction "TMDS.DATA0-_11") (pintype "bidirectional"))
    )
    (net (code "132") (name "/TX1+") (class "Default")
      (node (ref "IC7") (pin "2") (pinfunction "TMDS.CH1+_2") (pintype "bidirectional"))
      (node (ref "IC9") (pin "43") (pinfunction "TX1+_43") (pintype "bidirectional"))
      (node (ref "X5") (pin "6") (pinfunction "TMDS.DATA1+_6") (pintype "bidirectional"))
    )
    (net (code "133") (name "/TX1-") (class "Default")
      (node (ref "IC7") (pin "1") (pinfunction "TMDS.CH1-_1") (pintype "bidirectional"))
      (node (ref "IC9") (pin "42") (pinfunction "TX1-_42") (pintype "bidirectional"))
      (node (ref "X5") (pin "8") (pinfunction "TMDS.DATA1-_8") (pintype "bidirectional"))
    )
    (net (code "134") (name "/TX2+") (class "Default")
      (node (ref "IC7") (pin "5") (pinfunction "TMDS.CH2+_5") (pintype "bidirectional"))
      (node (ref "IC9") (pin "45") (pinfunction "TX2+_45") (pintype "bidirectional"))
      (node (ref "X5") (pin "3") (pinfunction "TMDS.DATA2+_3") (pintype "bidirectional"))
    )
    (net (code "135") (name "/TX2-") (class "Default")
      (node (ref "IC7") (pin "4") (pinfunction "TMDS.CH2-_4") (pintype "bidirectional"))
      (node (ref "IC9") (pin "44") (pinfunction "TX2-_44") (pintype "bidirectional"))
      (node (ref "X5") (pin "5") (pinfunction "TMDS.DATA2-_5") (pintype "bidirectional"))
    )
    (net (code "136") (name "/TXC+") (class "Default")
      (node (ref "IC8") (pin "2") (pinfunction "TMDS.CH1+_2") (pintype "bidirectional"))
      (node (ref "IC9") (pin "38") (pinfunction "TXC+_38") (pintype "bidirectional"))
      (node (ref "X5") (pin "12") (pinfunction "TMDS.CLOCK+_12") (pintype "bidirectional"))
    )
    (net (code "137") (name "/TXC-") (class "Default")
      (node (ref "IC8") (pin "1") (pinfunction "TMDS.CH1-_1") (pintype "bidirectional"))
      (node (ref "IC9") (pin "37") (pinfunction "TXC-_37") (pintype "bidirectional"))
      (node (ref "X5") (pin "14") (pinfunction "TMDS.CLOCK-_14") (pintype "bidirectional"))
    )
    (net (code "138") (name "/UART0_RST#") (class "Default")
      (node (ref "IC1") (pin "E17") (pinfunction "UART0_RSTN_E17") (pintype "bidirectional"))
      (node (ref "TP6") (pin "TP") (pinfunction "TP_TP") (pintype "input"))
    )
    (net (code "139") (name "/UART0_RXD") (class "Default")
      (node (ref "IC1") (pin "E15") (pinfunction "UART0_RXD_E15") (pintype "bidirectional"))
      (node (ref "IC17") (pin "6") (pinfunction "1Y_6") (pintype "bidirectional"))
    )
    (net (code "140") (name "/UART0_TXD") (class "Default")
      (node (ref "IC1") (pin "E16") (pinfunction "UART0_TXD_E16") (pintype "bidirectional"))
      (node (ref "IC17") (pin "5") (pinfunction "2A_5") (pintype "bidirectional"))
    )
    (net (code "141") (name "/UART1_RXD") (class "Default")
      (node (ref "IC1") (pin "D16") (pinfunction "UART1_RXD_D16") (pintype "bidirectional"))
      (node (ref "P9") (pin "26") (pinfunction "26_26") (pintype "passive"))
    )
    (net (code "142") (name "/UART1_TXD") (class "Default")
      (node (ref "IC1") (pin "D15") (pinfunction "UART1_TXD_D15") (pintype "bidirectional"))
      (node (ref "P9") (pin "24") (pinfunction "24_24") (pintype "passive"))
    )
    (net (code "143") (name "/UART2_RXD") (class "Default")
      (node (ref "IC1") (pin "A17") (pinfunction "UART2_RXD_A17") (pintype "bidirectional"))
      (node (ref "P9") (pin "22") (pinfunction "22_22") (pintype "passive"))
    )
    (net (code "144") (name "/UART2_TXD") (class "Default")
      (node (ref "IC1") (pin "B17") (pinfunction "UART2_TXD_B17") (pintype "bidirectional"))
      (node (ref "P9") (pin "21") (pinfunction "21_21") (pintype "passive"))
    )
    (net (code "145") (name "/UART4_RXD") (class "Default")
      (node (ref "IC1") (pin "T17") (pinfunction "UART4_RXD_T17") (pintype "bidirectional"))
      (node (ref "P9") (pin "11") (pinfunction "11_11") (pintype "passive"))
    )
    (net (code "146") (name "/UART4_TXD") (class "Default")
      (node (ref "IC1") (pin "U17") (pinfunction "UART4_TXD_U17") (pintype "bidirectional"))
      (node (ref "P9") (pin "13") (pinfunction "13_13") (pintype "passive"))
    )
    (net (code "147") (name "/USB.CLIENT.D+") (class "Default")
      (node (ref "IC1") (pin "N17") (pinfunction "USB0_DP_N17") (pintype "bidirectional"))
      (node (ref "IC14") (pin "1") (pinfunction "D+_1") (pintype "bidirectional"))
      (node (ref "X4") (pin "D+") (pinfunction "D+_D+") (pintype "input"))
    )
    (net (code "148") (name "/USB.CLIENT.D-") (class "Default")
      (node (ref "IC1") (pin "N18") (pinfunction "USB0_DM_N18") (pintype "bidirectional"))
      (node (ref "IC14") (pin "2") (pinfunction "D-_2") (pintype "bidirectional"))
      (node (ref "X4") (pin "D-") (pinfunction "D-_D-") (pintype "input"))
    )
    (net (code "149") (name "/USB.CLIENT.ID") (class "Default")
      (node (ref "IC1") (pin "P16") (pinfunction "USB0_ID_P16") (pintype "bidirectional"))
      (node (ref "IC14") (pin "3") (pinfunction "ID_3") (pintype "bidirectional"))
      (node (ref "X4") (pin "ID") (pinfunction "ID_ID") (pintype "input"))
    )
    (net (code "150") (name "/USB.HOST.D+") (class "Default")
      (node (ref "IC1") (pin "R17") (pinfunction "USB1_DP_R17") (pintype "bidirectional"))
      (node (ref "IC15") (pin "1") (pinfunction "D+_1") (pintype "bidirectional"))
      (node (ref "X3") (pin "3") (pinfunction "D+_3") (pintype "bidirectional"))
    )
    (net (code "151") (name "/USB.HOST.D-") (class "Default")
      (node (ref "IC1") (pin "R18") (pinfunction "USB1_DM_R18") (pintype "bidirectional"))
      (node (ref "IC15") (pin "2") (pinfunction "D-_2") (pintype "bidirectional"))
      (node (ref "X3") (pin "2") (pinfunction "D-_2") (pintype "bidirectional"))
    )
    (net (code "152") (name "/USB1_DRVVBUS") (class "Default")
      (node (ref "IC1") (pin "F15") (pinfunction "USB1_DRVVBUS_F15") (pintype "bidirectional"))
      (node (ref "IC12") (pin "4") (pinfunction "EN#_4") (pintype "bidirectional"))
      (node (ref "R19") (pin "1") (pinfunction "1_1") (pintype "passive"))
    )
    (net (code "153") (name "/USB1_OC#") (class "Default")
      (node (ref "IC1") (pin "T16") (pinfunction "(USB1_OCN)GPIO1_26_T16") (pintype "bidirectional"))
      (node (ref "IC12") (pin "5") (pinfunction "OC#_5") (pintype "bidirectional"))
      (node (ref "R122") (pin "2") (pinfunction "2_2") (pintype "passive"))
    )
    (net (code "154") (name "/USB1_VBUS") (class "Default")
      (node (ref "FB4") (pin "2") (pinfunction "P$2_2") (pintype "bidirectional"))
      (node (ref "IC1") (pin "T18") (pinfunction "USB1_VBUS_T18") (pintype "bidirectional"))
    )
    (net (code "155") (name "/USR0") (class "Default")
      (node (ref "IC1") (pin "V15") (pinfunction "USR0_V15") (pintype "bidirectional"))
      (node (ref "R104") (pin "2") (pinfunction "2_2") (pintype "passive"))
    )
    (net (code "156") (name "/USR1") (class "Default")
      (node (ref "IC1") (pin "U15") (pinfunction "USR1_U15") (pintype "bidirectional"))
      (node (ref "R100") (pin "2") (pinfunction "2_2") (pintype "passive"))
    )
    (net (code "157") (name "/USR2") (class "Default")
      (node (ref "IC1") (pin "T15") (pinfunction "USR2_T15") (pintype "bidirectional"))
      (node (ref "R96") (pin "2") (pinfunction "2_2") (pintype "passive"))
    )
    (net (code "158") (name "/USR3") (class "Default")
      (node (ref "IC1") (pin "V16") (pinfunction "USR3_V16") (pintype "bidirectional"))
      (node (ref "R92") (pin "2") (pinfunction "2_2") (pintype "passive"))
    )
    (net (code "159") (name "/VIN_BAT") (class "Default")
      (node (ref "IC1") (pin "Y2") (pinfunction "BAT_1_Y2") (pintype "bidirectional"))
      (node (ref "IC1") (pin "Y3") (pinfunction "BAT_2_Y3") (pintype "bidirectional"))
      (node (ref "TP2") (pin "P$1") (pinfunction "TP_P$1") (pintype "bidirectional"))
    )
    (net (code "160") (name "/WL_EN") (class "Default")
      (node (ref "IC11") (pin "3") (pinfunction "A2_3") (pintype "bidirectional"))
      (node (ref "MOD1") (pin "40") (pinfunction "WLAN_EN_40") (pintype "bidirectional"))
      (node (ref "R10") (pin "1") (pinfunction "1_1") (pintype "passive"))
      (node (ref "T3") (pin "G") (pinfunction "G_G") (pintype "bidirectional"))
    )
    (net (code "161") (name "/WL_EN.SIP") (class "Default")
      (node (ref "IC1") (pin "K18") (pinfunction "MII1_TXCLK_K18") (pintype "bidirectional"))
      (node (ref "R136") (pin "1") (pinfunction "1_1") (pintype "passive"))
    )
    (net (code "162") (name "/WL_IRQ") (class "Default")
      (node (ref "IC11") (pin "9") (pinfunction "A8_9") (pintype "bidirectional"))
      (node (ref "R60") (pin "2") (pinfunction "2_2") (pintype "passive"))
    )
    (net (code "163") (name "/WL_IRQ.SIP") (class "Default")
      (node (ref "IC1") (pin "H18") (pinfunction "MII1_REFCLK_H18") (pintype "bidirectional"))
      (node (ref "R134") (pin "1") (pinfunction "1_1") (pintype "passive"))
    )
    (net (code "164") (name "/WL_SDIO_CLK") (class "Default")
      (node (ref "IC10") (pin "6") (pinfunction "A5_6") (pintype "bidirectional"))
      (node (ref "R103") (pin "2") (pinfunction "2_2") (pintype "passive"))
      (node (ref "R64") (pin "2") (pinfunction "2_2") (pintype "passive"))
    )
    (net (code "165") (name "/WL_SDIO_CLK.SIP") (class "Default")
      (node (ref "IC1") (pin "L15") (pinfunction "MII1_RXD1_L15") (pintype "bidirectional"))
      (node (ref "R126") (pin "1") (pinfunction "1_1") (pintype "passive"))
    )
    (net (code "166") (name "/WL_SDIO_CMD") (class "Default")
      (node (ref "IC10") (pin "7") (pinfunction "A6_7") (pintype "bidirectional"))
      (node (ref "R105") (pin "2") (pinfunction "2_2") (pintype "passive"))
      (node (ref "R62") (pin "2") (pinfunction "2_2") (pintype "passive"))
    )
    (net (code "167") (name "/WL_SDIO_CMD.SIP") (class "Default")
      (node (ref "IC1") (pin "J16") (pinfunction "MII1_TXEN_J16") (pintype "bidirectional"))
      (node (ref "R86") (pin "1") (pinfunction "1_1") (pintype "passive"))
    )
    (net (code "168") (name "/WL_SDIO_D0") (class "Default")
      (node (ref "IC10") (pin "1") (pinfunction "A1_1") (pintype "bidirectional"))
      (node (ref "R66") (pin "2") (pinfunction "2_2") (pintype "passive"))
      (node (ref "R98") (pin "2") (pinfunction "2_2") (pintype "passive"))
    )
    (net (code "169") (name "/WL_SDIO_D0.SIP") (class "Default")
      (node (ref "IC1") (pin "J17") (pinfunction "MII1_RXDV_J17") (pintype "bidirectional"))
      (node (ref "R130") (pin "1") (pinfunction "1_1") (pintype "passive"))
    )
    (net (code "170") (name "/WL_SDIO_D1") (class "Default")
      (node (ref "IC10") (pin "3") (pinfunction "A2_3") (pintype "bidirectional"))
      (node (ref "R68") (pin "2") (pinfunction "2_2") (pintype "passive"))
      (node (ref "R99") (pin "2") (pinfunction "2_2") (pintype "passive"))
    )
    (net (code "171") (name "/WL_SDIO_D1.SIP") (class "Default")
      (node (ref "IC1") (pin "J18") (pinfunction "MII1_TXD3_J18") (pintype "bidirectional"))
      (node (ref "R129") (pin "1") (pinfunction "1_1") (pintype "passive"))
    )
    (net (code "172") (name "/WL_SDIO_D2") (class "Default")
      (node (ref "IC10") (pin "4") (pinfunction "A3_4") (pintype "bidirectional"))
      (node (ref "R101") (pin "2") (pinfunction "2_2") (pintype "passive"))
      (node (ref "R70") (pin "2") (pinfunction "2_2") (pintype "passive"))
    )
    (net (code "173") (name "/WL_SDIO_D2.SIP") (class "Default")
      (node (ref "IC1") (pin "K15") (pinfunction "MII1_TXD2_K15") (pintype "bidirectional"))
      (node (ref "R128") (pin "1") (pinfunction "1_1") (pintype "passive"))
    )
    (net (code "174") (name "/WL_SDIO_D3") (class "Default")
      (node (ref "IC10") (pin "5") (pinfunction "A4_5") (pintype "bidirectional"))
      (node (ref "R102") (pin "2") (pinfunction "2_2") (pintype "passive"))
      (node (ref "R72") (pin "2") (pinfunction "2_2") (pintype "passive"))
    )
    (net (code "175") (name "/WL_SDIO_D3.SIP") (class "Default")
      (node (ref "IC1") (pin "H16") (pinfunction "MII1_COL_H16") (pintype "bidirectional"))
      (node (ref "R127") (pin "1") (pinfunction "1_1") (pintype "passive"))
    )
    (net (code "176") (name "/XDMA_EVENT_INTRO") (class "Default")
      (node (ref "FB5") (pin "2") (pinfunction "2_2") (pintype "passive"))
      (node (ref "IC13") (pin "1") (pinfunction "CLK_1") (pintype "bidirectional"))
      (node (ref "P2") (pin "17") (pinfunction "EMU2_17") (pintype "bidirectional"))
    )
    (net (code "177") (name "GHI-POWERGOUNDSUPPLY_1.8V-WIFI") (class "Default")
      (node (ref "C11") (pin "+") (pinfunction "+_+") (pintype "passive"))
      (node (ref "C24") (pin "1") (pinfunction "1_1") (pintype "passive"))
      (node (ref "C25") (pin "1") (pinfunction "1_1") (pintype "passive"))
      (node (ref "C43") (pin "1") (pinfunction "1_1") (pintype "passive"))
      (node (ref "C64") (pin "1") (pinfunction "1_1") (pintype "passive"))
      (node (ref "C8") (pin "1") (pinfunction "1_1") (pintype "passive"))
      (node (ref "IC10") (pin "2") (pinfunction "VCCA_2") (pintype "bidirectional"))
      (node (ref "IC11") (pin "2") (pinfunction "VCCA_2") (pintype "bidirectional"))
      (node (ref "IC19") (pin "5") (pinfunction "VOUT_5") (pintype "bidirectional"))
      (node (ref "MOD1") (pin "38") (pinfunction "VIO_38") (pintype "bidirectional"))
      (node (ref "OSC2") (pin "4") (pinfunction "VCC_4") (pintype "bidirectional"))
      (node (ref "R101") (pin "1") (pinfunction "1_1") (pintype "passive"))
      (node (ref "R102") (pin "1") (pinfunction "1_1") (pintype "passive"))
      (node (ref "R103") (pin "1") (pinfunction "1_1") (pintype "passive"))
      (node (ref "R105") (pin "1") (pinfunction "1_1") (pintype "passive"))
      (node (ref "R111") (pin "1") (pinfunction "1_1") (pintype "passive"))
      (node (ref "R90") (pin "1") (pinfunction "1_1") (pintype "passive"))
      (node (ref "R98") (pin "1") (pinfunction "1_1") (pintype "passive"))
      (node (ref "R99") (pin "1") (pinfunction "1_1") (pintype "passive"))
    )
    (net (code "178") (name "GHI-POWERGOUNDSUPPLY_3.3V-WIFI") (class "Default")
      (node (ref "C10") (pin "1") (pinfunction "1_1") (pintype "passive"))
      (node (ref "C20") (pin "1") (pinfunction "1_1") (pintype "passive"))
      (node (ref "C23") (pin "+") (pinfunction "+_+") (pintype "passive"))
      (node (ref "C44") (pin "1") (pinfunction "1_1") (pintype "passive"))
      (node (ref "C45") (pin "1") (pinfunction "1_1") (pintype "passive"))
      (node (ref "C61") (pin "1") (pinfunction "1_1") (pintype "passive"))
      (node (ref "C63") (pin "1") (pinfunction "1_1") (pintype "passive"))
      (node (ref "IC10") (pin "19") (pinfunction "VCCB_19") (pintype "bidirectional"))
      (node (ref "IC11") (pin "19") (pinfunction "VCCB_19") (pintype "bidirectional"))
      (node (ref "IC18") (pin "4") (pinfunction "OUT_4") (pintype "bidirectional"))
      (node (ref "IC19") (pin "1") (pinfunction "VIN_1") (pintype "bidirectional"))
      (node (ref "IC19") (pin "3") (pinfunction "EN_3") (pintype "bidirectional"))
      (node (ref "MOD1") (pin "46") (pinfunction "VBAT_IN1_46") (pintype "bidirectional"))
      (node (ref "MOD1") (pin "47") (pinfunction "VBAT_IN2_47") (pintype "bidirectional"))
      (node (ref "R124") (pin "2") (pinfunction "2_2") (pintype "passive"))
      (node (ref "R125") (pin "2") (pinfunction "2_2") (pintype "passive"))
      (node (ref "R93") (pin "1") (pinfunction "1_1") (pintype "passive"))
    )
    (net (code "179") (name "GHI-POWERGOUNDSUPPLY_AGND") (class "Default")
      (node (ref "IC1") (pin "A6") (pinfunction "AGND_1_A6") (pintype "bidirectional"))
      (node (ref "IC1") (pin "A9") (pinfunction "AGND_0_A9") (pintype "bidirectional"))
      (node (ref "IC1") (pin "E8") (pinfunction "AGND_E8") (pintype "bidirectional"))
      (node (ref "P9") (pin "34") (pinfunction "34_34") (pintype "passive"))
    )
    (net (code "180") (name "GHI-POWERGOUNDSUPPLY_CGND") (class "Default")
      (node (ref "MGT1") (pin "P$1") (pinfunction "P$1_P$1") (pintype "bidirectional"))
      (node (ref "MGT2") (pin "P$1") (pinfunction "P$1_P$1") (pintype "bidirectional"))
      (node (ref "MGT3") (pin "P$1") (pinfunction "P$1_P$1") (pintype "bidirectional"))
      (node (ref "MGT4") (pin "P$1") (pinfunction "P$1_P$1") (pintype "bidirectional"))
      (node (ref "R17") (pin "2") (pinfunction "2_2") (pintype "passive"))
      (node (ref "X2") (pin "CGND1") (pinfunction "CGND1_CGND1") (pintype "bidirectional"))
      (node (ref "X2") (pin "CGND2") (pinfunction "CGND2_CGND2") (pintype "bidirectional"))
      (node (ref "X2") (pin "CGND3") (pinfunction "CGND3_CGND3") (pintype "bidirectional"))
      (node (ref "X2") (pin "CGND4") (pinfunction "CGND4_CGND4") (pintype "bidirectional"))
      (node (ref "X2") (pin "CGND5") (pinfunction "CGND5_CGND5") (pintype "bidirectional"))
      (node (ref "X2") (pin "CGND6") (pinfunction "CGND6_CGND6") (pintype "bidirectional"))
      (node (ref "X3") (pin "5") (pinfunction "CG1_5") (pintype "bidirectional"))
      (node (ref "X3") (pin "6") (pinfunction "CG2_6") (pintype "bidirectional"))
      (node (ref "X4") (pin "CGND1") (pinfunction "SGND1_CGND1") (pintype "bidirectional"))
      (node (ref "X4") (pin "CGND2") (pinfunction "SGND2_CGND2") (pintype "bidirectional"))
      (node (ref "X4") (pin "CGND3") (pinfunction "SGND3_CGND3") (pintype "bidirectional"))
      (node (ref "X4") (pin "CGND4") (pinfunction "SGND4_CGND4") (pintype "bidirectional"))
      (node (ref "X4") (pin "CGND5") (pinfunction "SGND5_CGND5") (pintype "bidirectional"))
      (node (ref "X4") (pin "CGND6") (pinfunction "SGND6_CGND6") (pintype "bidirectional"))
      (node (ref "X5") (pin "CG1") (pinfunction "CG1_CG1") (pintype "bidirectional"))
      (node (ref "X5") (pin "CG2") (pinfunction "CG2_CG2") (pintype "bidirectional"))
      (node (ref "X5") (pin "CG3") (pinfunction "CG3_CG3") (pintype "bidirectional"))
      (node (ref "X5") (pin "CG4") (pinfunction "CG4_CG4") (pintype "bidirectional"))
    )
    (net (code "181") (name "GHI-POWERGOUNDSUPPLY_HDMI_1V8") (class "Default")
      (node (ref "C50") (pin "1") (pinfunction "1_1") (pintype "passive"))
      (node (ref "C51") (pin "1") (pinfunction "1_1") (pintype "passive"))
      (node (ref "C52") (pin "1") (pinfunction "1_1") (pintype "passive"))
      (node (ref "C53") (pin "1") (pinfunction "1_1") (pintype "passive"))
      (node (ref "C54") (pin "1") (pinfunction "1_1") (pintype "passive"))
      (node (ref "C55") (pin "1") (pinfunction "1_1") (pintype "passive"))
      (node (ref "C56") (pin "1") (pinfunction "1_1") (pintype "passive"))
      (node (ref "C57") (pin "1") (pinfunction "1_1") (pintype "passive"))
      (node (ref "FB2") (pin "2") (pinfunction "P$2_2") (pintype "bidirectional"))
      (node (ref "IC9") (pin "14") (pinfunction "VDDD1(IO)(1V8)_14") (pintype "bidirectional"))
      (node (ref "IC9") (pin "29") (pinfunction "VDDDC2_29") (pintype "bidirectional"))
      (node (ref "IC9") (pin "35") (pinfunction "VDDA(1V8)_35") (pintype "bidirectional"))
      (node (ref "IC9") (pin "36") (pinfunction "VDDA1(TX)(1V8)_36") (pintype "bidirectional"))
      (node (ref "IC9") (pin "41") (pinfunction "VDDA2(TX)(1V8)_41") (pintype "bidirectional"))
      (node (ref "IC9") (pin "46") (pinfunction "VDDA3(TX)(1V8)_46") (pintype "bidirectional"))
      (node (ref "IC9") (pin "47") (pinfunction "VDDA1(PLL)(1V8)_47") (pintype "bidirectional"))
      (node (ref "IC9") (pin "48") (pinfunction "VDDA2(PLL)(1V8)_48") (pintype "bidirectional"))
      (node (ref "IC9") (pin "5") (pinfunction "VDDDC1_5") (pintype "bidirectional"))
      (node (ref "IC9") (pin "55") (pinfunction "VDDD2(IO)(1V8)_55") (pintype "bidirectional"))
    )
    (net (code "182") (name "GHI-POWERGOUNDSUPPLY_SYS_5V") (class "Default")
      (node (ref "C62") (pin "+") (pinfunction "+_+") (pintype "passive"))
      (node (ref "D2") (pin "A") (pinfunction "A_A") (pintype "bidirectional"))
      (node (ref "F1") (pin "2") (pinfunction "2_2") (pintype "passive"))
      (node (ref "IC1") (pin "W4") (pinfunction "SYS_5V_1_W4") (pintype "bidirectional"))
      (node (ref "IC1") (pin "Y4") (pinfunction "SYS_5V_2_Y4") (pintype "bidirectional"))
      (node (ref "IC12") (pin "2") (pinfunction "IN1_2") (pintype "bidirectional"))
      (node (ref "IC12") (pin "3") (pinfunction "IN2_3") (pintype "bidirectional"))
      (node (ref "P9") (pin "7") (pinfunction "7_7") (pintype "passive"))
      (node (ref "P9") (pin "8") (pinfunction "8_8") (pintype "passive"))
    )
    (net (code "183") (name "GHI-POWERGOUNDSUPPLY_USB_DC") (class "Default")
      (node (ref "C59") (pin "1") (pinfunction "1_1") (pintype "passive"))
      (node (ref "D4") (pin "A") (pinfunction "A_A") (pintype "bidirectional"))
      (node (ref "IC1") (pin "Y8") (pinfunction "VIN_USB_0_Y8") (pintype "bidirectional"))
      (node (ref "IC1") (pin "Y9") (pinfunction "VIN_USB_1_Y9") (pintype "bidirectional"))
      (node (ref "IC14") (pin "6") (pinfunction "VBUS_6") (pintype "bidirectional"))
      (node (ref "R26") (pin "2") (pinfunction "2_2") (pintype "passive"))
      (node (ref "X4") (pin "VBUS") (pinfunction "VBUS_VBUS") (pintype "input"))
    )
    (net (code "184") (name "GHI-POWERGOUNDSUPPLY_VDDS_DDR") (class "Default")
      (node (ref "IC1") (pin "H5") (pinfunction "VDDS_DDR4_H5") (pintype "bidirectional"))
    )
    (net (code "185") (name "GHI-POWERGOUNDSUPPLY_VDDS_PLL") (class "Default")
      (node (ref "IC1") (pin "E7") (pinfunction "VDD_PLL1_E7") (pintype "bidirectional"))
    )
    (net (code "186") (name "GHI-POWERGOUNDSUPPLY_VDD_1V8") (class "Default")
      (node (ref "FB2") (pin "1") (pinfunction "P$1_1") (pintype "bidirectional"))
      (node (ref "IC1") (pin "D10") (pinfunction "VDD_1V84_D10") (pintype "bidirectional"))
      (node (ref "IC1") (pin "E9") (pinfunction "VDD_1V83_E9") (pintype "bidirectional"))
      (node (ref "IC1") (pin "N16") (pinfunction "VDD_1V8_0_N16") (pintype "bidirectional"))
      (node (ref "IC1") (pin "R16") (pinfunction "VDD_1V8_1_R16") (pintype "bidirectional"))
      (node (ref "IC2") (pin "5") (pinfunction "VCC_5") (pintype "bidirectional"))
      (node (ref "IC5") (pin "3") (pinfunction "A_3") (pintype "passive"))
      (node (ref "IC6") (pin "3") (pinfunction "A_3") (pintype "passive"))
      (node (ref "R47") (pin "2") (pinfunction "2_2") (pintype "passive"))
      (node (ref "R51") (pin "2") (pinfunction "2_2") (pintype "passive"))
      (node (ref "T1") (pin "C") (pinfunction "C_C") (pintype "passive"))
      (node (ref "T2") (pin "C") (pinfunction "C_C") (pintype "passive"))
    )
    (net (code "187") (name "GHI-POWERGOUNDSUPPLY_VDD_3V3A") (class "Default")
      (node (ref "IC1") (pin "N5") (pinfunction "VDD_3V3A18_N5") (pintype "bidirectional"))
      (node (ref "IC1") (pin "P5") (pinfunction "VDD_3V3A17_P5") (pintype "bidirectional"))
      (node (ref "IC1") (pin "P6") (pinfunction "VDD_3V3A16_P6") (pintype "bidirectional"))
      (node (ref "IC1") (pin "P7") (pinfunction "VDD_3V3A15_P7") (pintype "bidirectional"))
      (node (ref "R44") (pin "1") (pinfunction "1_1") (pintype "passive"))
      (node (ref "R46") (pin "1") (pinfunction "1_1") (pintype "passive"))
      (node (ref "T1") (pin "E") (pinfunction "E_E") (pintype "passive"))
    )
    (net (code "188") (name "GHI-POWERGOUNDSUPPLY_VDD_3V3AUX") (class "Default")
      (node (ref "IC1") (pin "Y11") (pinfunction "VDD_3V3AUX_Y11") (pintype "bidirectional"))
      (node (ref "PWR") (pin "A") (pinfunction "A_A") (pintype "passive"))
    )
    (net (code "189") (name "GHI-POWERGOUNDSUPPLY_VDD_3V3B") (class "Default")
      (node (ref "C1") (pin "1") (pinfunction "1_1") (pintype "passive"))
      (node (ref "C12") (pin "1") (pinfunction "1_1") (pintype "passive"))
      (node (ref "C13") (pin "1") (pinfunction "1_1") (pintype "passive"))
      (node (ref "C14") (pin "1") (pinfunction "1_1") (pintype "passive"))
      (node (ref "C15") (pin "1") (pinfunction "1_1") (pintype "passive"))
      (node (ref "C17") (pin "1") (pinfunction "1_1") (pintype "passive"))
      (node (ref "C18") (pin "1") (pinfunction "1_1") (pintype "passive"))
      (node (ref "C2") (pin "1") (pinfunction "1_1") (pintype "passive"))
      (node (ref "C22") (pin "1") (pinfunction "1_1") (pintype "passive"))
      (node (ref "C47") (pin "1") (pinfunction "1_1") (pintype "passive"))
      (node (ref "C48") (pin "1") (pinfunction "1_1") (pintype "passive"))
      (node (ref "C49") (pin "1") (pinfunction "1_1") (pintype "passive"))
      (node (ref "C9") (pin "1") (pinfunction "1_1") (pintype "passive"))
      (node (ref "IC1") (pin "U20") (pinfunction "VDD_3V3B_0_U20") (pintype "bidirectional"))
      (node (ref "IC1") (pin "V20") (pinfunction "VDD_3V3B_1_V20") (pintype "bidirectional"))
      (node (ref "IC13") (pin "6") (pinfunction "CLR#_6") (pintype "bidirectional"))
      (node (ref "IC13") (pin "7") (pinfunction "PRE#_7") (pintype "bidirectional"))
      (node (ref "IC13") (pin "8") (pinfunction "VCC_8") (pintype "bidirectional"))
      (node (ref "IC17") (pin "7") (pinfunction "2OE_7") (pintype "bidirectional"))
      (node (ref "IC17") (pin "8") (pinfunction "VCC_8") (pintype "bidirectional"))
      (node (ref "IC22") (pin "C6") (pinfunction "VCCQ1_C6") (pintype "bidirectional"))
      (node (ref "IC22") (pin "E6") (pinfunction "VCC1_E6") (pintype "bidirectional"))
      (node (ref "IC22") (pin "F5") (pinfunction "VCC2_F5") (pintype "bidirectional"))
      (node (ref "IC22") (pin "J10") (pinfunction "VCC3_J10") (pintype "bidirectional"))
      (node (ref "IC22") (pin "K9") (pinfunction "VCC4_K9") (pintype "bidirectional"))
      (node (ref "IC22") (pin "M4") (pinfunction "VCCQ2_M4") (pintype "bidirectional"))
      (node (ref "IC22") (pin "N4") (pinfunction "VCCQ3_N4") (pintype "bidirectional"))
      (node (ref "IC22") (pin "P3") (pinfunction "VCCQ4_P3") (pintype "bidirectional"))
      (node (ref "IC22") (pin "P5") (pinfunction "VCCQ5_P5") (pintype "bidirectional"))
      (node (ref "IC3") (pin "5") (pinfunction "VCC_5") (pintype "bidirectional"))
      (node (ref "IC4") (pin "4") (pinfunction "VCC_4") (pintype "bidirectional"))
      (node (ref "OSC1") (pin "4") (pinfunction "VCC_4") (pintype "bidirectional"))
      (node (ref "P2") (pin "5") (pinfunction "TVDD_5") (pintype "bidirectional"))
      (node (ref "P9") (pin "3") (pinfunction "3_3") (pintype "passive"))
      (node (ref "P9") (pin "4") (pinfunction "4_4") (pintype "passive"))
      (node (ref "R1") (pin "2") (pinfunction "2_2") (pintype "passive"))
      (node (ref "R12") (pin "2") (pinfunction "2_2") (pintype "passive"))
      (node (ref "R120") (pin "1") (pinfunction "1_1") (pintype "passive"))
      (node (ref "R121") (pin "1") (pinfunction "1_1") (pintype "passive"))
      (node (ref "R122") (pin "1") (pinfunction "1_1") (pintype "passive"))
      (node (ref "R13") (pin "2") (pinfunction "2_2") (pintype "passive"))
      (node (ref "R16") (pin "2") (pinfunction "2_2") (pintype "passive"))
      (node (ref "R18") (pin "2") (pinfunction "2_2") (pintype "passive"))
      (node (ref "R2") (pin "2") (pinfunction "2_2") (pintype "passive"))
      (node (ref "R20") (pin "2") (pinfunction "2_2") (pintype "passive"))
      (node (ref "R21") (pin "1") (pinfunction "1_1") (pintype "passive"))
      (node (ref "R23") (pin "2") (pinfunction "2_2") (pintype "passive"))
      (node (ref "R25") (pin "2") (pinfunction "2_2") (pintype "passive"))
      (node (ref "R28") (pin "2") (pinfunction "2_2") (pintype "passive"))
      (node (ref "R3") (pin "2") (pinfunction "2_2") (pintype "passive"))
      (node (ref "R30") (pin "2") (pinfunction "2_2") (pintype "passive"))
      (node (ref "R31") (pin "2") (pinfunction "2_2") (pintype "passive"))
      (node (ref "R32") (pin "1") (pinfunction "1_1") (pintype "passive"))
      (node (ref "R33") (pin "2") (pinfunction "2_2") (pintype "passive"))
      (node (ref "R4") (pin "2") (pinfunction "2_2") (pintype "passive"))
      (node (ref "R40") (pin "1") (pinfunction "1_1") (pintype "passive"))
      (node (ref "R41") (pin "1") (pinfunction "1_1") (pintype "passive"))
      (node (ref "R42") (pin "1") (pinfunction "1_1") (pintype "passive"))
      (node (ref "R43") (pin "1") (pinfunction "1_1") (pintype "passive"))
      (node (ref "R48") (pin "1") (pinfunction "1_1") (pintype "passive"))
      (node (ref "R5") (pin "2") (pinfunction "2_2") (pintype "passive"))
      (node (ref "R50") (pin "1") (pinfunction "1_1") (pintype "passive"))
      (node (ref "R53") (pin "1") (pinfunction "1_1") (pintype "passive"))
      (node (ref "R58") (pin "2") (pinfunction "2_2") (pintype "passive"))
      (node (ref "R6") (pin "2") (pinfunction "2_2") (pintype "passive"))
      (node (ref "R7") (pin "2") (pinfunction "2_2") (pintype "passive"))
      (node (ref "R76") (pin "2") (pinfunction "2_2") (pintype "passive"))
      (node (ref "R78") (pin "2") (pinfunction "2_2") (pintype "passive"))
      (node (ref "R80") (pin "2") (pinfunction "2_2") (pintype "passive"))
      (node (ref "R82") (pin "2") (pinfunction "2_2") (pintype "passive"))
      (node (ref "R89") (pin "1") (pinfunction "1_1") (pintype "passive"))
      (node (ref "T2") (pin "E") (pinfunction "E_E") (pintype "passive"))
      (node (ref "X2") (pin "4") (pinfunction "VDD_4") (pintype "bidirectional"))
    )
    (net (code "190") (name "GHI-POWERGOUNDSUPPLY_VDD_5V") (class "Default")
      (node (ref "D3") (pin "A") (pinfunction "A_A") (pintype "bidirectional"))
      (node (ref "IC1") (pin "Y5") (pinfunction "VIN_5V_0_Y5") (pintype "bidirectional"))
      (node (ref "IC1") (pin "Y6") (pinfunction "VIN_5V_1_Y6") (pintype "bidirectional"))
      (node (ref "P9") (pin "5") (pinfunction "5_5") (pintype "passive"))
      (node (ref "P9") (pin "6") (pinfunction "6_6") (pintype "passive"))
      (node (ref "X12") (pin "IN") (pinfunction "IN_IN") (pintype "bidirectional"))
    )
    (net (code "191") (name "GHI-POWERGOUNDSUPPLY_VDD_ADC") (class "Default")
      (node (ref "IC1") (pin "A4") (pinfunction "VDD_ADC_1_A4") (pintype "bidirectional"))
      (node (ref "IC1") (pin "A5") (pinfunction "VDD_ADC_0_A5") (pintype "bidirectional"))
      (node (ref "IC1") (pin "B9") (pinfunction "VREFP_ADC_B9") (pintype "bidirectional"))
      (node (ref "IC1") (pin "D8") (pinfunction "VDDA_ADC_D8") (pintype "bidirectional"))
      (node (ref "P9") (pin "32") (pinfunction "32_32") (pintype "passive"))
    )
    (net (code "192") (name "GHI-POWERGOUNDSUPPLY_VDD_CORE") (class "Default")
      (node (ref "IC1") (pin "F6") (pinfunction "VDD_CORE1_F6") (pintype "bidirectional"))
    )
    (net (code "193") (name "GHI-POWERGOUNDSUPPLY_VDD_MPU") (class "Default")
      (node (ref "IC1") (pin "F10") (pinfunction "VDD_MPU0_F10") (pintype "bidirectional"))
    )
    (net (code "194") (name "GHI-POWERGOUNDSUPPLY_VDD_RTC") (class "Default")
      (node (ref "IC1") (pin "N6") (pinfunction "VDD_RTC4_N6") (pintype "bidirectional"))
    )
    (net (code "195") (name "GND") (class "Default")
      (node (ref "ANT1") (pin "GND1") (pinfunction "GND1_GND1") (pintype "bidirectional"))
      (node (ref "ANT1") (pin "GND2") (pinfunction "GND2_GND2") (pintype "bidirectional"))
      (node (ref "ANT2") (pin "GND1") (pinfunction "GND1_GND1") (pintype "bidirectional"))
      (node (ref "ANT2") (pin "GND2") (pinfunction "GND2_GND2") (pintype "bidirectional"))
      (node (ref "C1") (pin "2") (pinfunction "2_2") (pintype "passive"))
      (node (ref "C10") (pin "2") (pinfunction "2_2") (pintype "passive"))
      (node (ref "C11") (pin "-") (pinfunction "-_-") (pintype "passive"))
      (node (ref "C12") (pin "2") (pinfunction "2_2") (pintype "passive"))
      (node (ref "C13") (pin "2") (pinfunction "2_2") (pintype "passive"))
      (node (ref "C14") (pin "2") (pinfunction "2_2") (pintype "passive"))
      (node (ref "C15") (pin "2") (pinfunction "2_2") (pintype "passive"))
      (node (ref "C16") (pin "2") (pinfunction "2_2") (pintype "passive"))
      (node (ref "C17") (pin "2") (pinfunction "2_2") (pintype "passive"))
      (node (ref "C18") (pin "2") (pinfunction "2_2") (pintype "passive"))
      (node (ref "C19") (pin "2") (pinfunction "2_2") (pintype "passive"))
      (node (ref "C2") (pin "2") (pinfunction "2_2") (pintype "passive"))
      (node (ref "C20") (pin "2") (pinfunction "2_2") (pintype "passive"))
      (node (ref "C21") (pin "2") (pinfunction "2_2") (pintype "passive"))
      (node (ref "C22") (pin "2") (pinfunction "2_2") (pintype "passive"))
      (node (ref "C23") (pin "-") (pinfunction "-_-") (pintype "passive"))
      (node (ref "C24") (pin "2") (pinfunction "2_2") (pintype "passive"))
      (node (ref "C25") (pin "2") (pinfunction "2_2") (pintype "passive"))
      (node (ref "C27") (pin "2") (pinfunction "2_2") (pintype "passive"))
      (node (ref "C28") (pin "2") (pinfunction "2_2") (pintype "passive"))
      (node (ref "C29") (pin "2") (pinfunction "2_2") (pintype "passive"))
      (node (ref "C30") (pin "2") (pinfunction "2_2") (pintype "passive"))
      (node (ref "C31") (pin "2") (pinfunction "2_2") (pintype "passive"))
      (node (ref "C32") (pin "2") (pinfunction "2_2") (pintype "passive"))
      (node (ref "C33") (pin "2") (pinfunction "2_2") (pintype "passive"))
      (node (ref "C34") (pin "2") (pinfunction "2_2") (pintype "passive"))
      (node (ref "C35") (pin "2") (pinfunction "2_2") (pintype "passive"))
      (node (ref "C36") (pin "2") (pinfunction "2_2") (pintype "passive"))
      (node (ref "C37") (pin "2") (pinfunction "2_2") (pintype "passive"))
      (node (ref "C38") (pin "2") (pinfunction "2_2") (pintype "passive"))
      (node (ref "C39") (pin "2") (pinfunction "2_2") (pintype "passive"))
      (node (ref "C40") (pin "2") (pinfunction "2_2") (pintype "passive"))
      (node (ref "C41") (pin "2") (pinfunction "2_2") (pintype "passive"))
      (node (ref "C42") (pin "2") (pinfunction "2_2") (pintype "passive"))
      (node (ref "C43") (pin "2") (pinfunction "2_2") (pintype "passive"))
      (node (ref "C44") (pin "2") (pinfunction "2_2") (pintype "passive"))
      (node (ref "C45") (pin "2") (pinfunction "2_2") (pintype "passive"))
      (node (ref "C47") (pin "2") (pinfunction "2_2") (pintype "passive"))
      (node (ref "C48") (pin "2") (pinfunction "2_2") (pintype "passive"))
      (node (ref "C49") (pin "2") (pinfunction "2_2") (pintype "passive"))
      (node (ref "C50") (pin "2") (pinfunction "2_2") (pintype "passive"))
      (node (ref "C51") (pin "2") (pinfunction "2_2") (pintype "passive"))
      (node (ref "C52") (pin "2") (pinfunction "2_2") (pintype "passive"))
      (node (ref "C53") (pin "2") (pinfunction "2_2") (pintype "passive"))
      (node (ref "C54") (pin "2") (pinfunction "2_2") (pintype "passive"))
      (node (ref "C55") (pin "2") (pinfunction "2_2") (pintype "passive"))
      (node (ref "C56") (pin "2") (pinfunction "2_2") (pintype "passive"))
      (node (ref "C57") (pin "2") (pinfunction "2_2") (pintype "passive"))
      (node (ref "C58") (pin "2") (pinfunction "2_2") (pintype "passive"))
      (node (ref "C59") (pin "2") (pinfunction "2_2") (pintype "passive"))
      (node (ref "C61") (pin "2") (pinfunction "2_2") (pintype "passive"))
      (node (ref "C62") (pin "-") (pinfunction "-_-") (pintype "passive"))
      (node (ref "C63") (pin "2") (pinfunction "2_2") (pintype "passive"))
      (node (ref "C64") (pin "2") (pinfunction "2_2") (pintype "passive"))
      (node (ref "C69") (pin "2") (pinfunction "2_2") (pintype "passive"))
      (node (ref "C7") (pin "2") (pinfunction "2_2") (pintype "passive"))
      (node (ref "C8") (pin "2") (pinfunction "2_2") (pintype "passive"))
      (node (ref "C9") (pin "2") (pinfunction "2_2") (pintype "passive"))
      (node (ref "D8") (pin "2") (pinfunction "A2_2") (pintype "passive"))
      (node (ref "IC1") (pin "A1") (pinfunction "DGND1_A1") (pintype "bidirectional"))
      (node (ref "IC1") (pin "A18") (pinfunction "DGND2_A18") (pintype "bidirectional"))
      (node (ref "IC1") (pin "E19") (pinfunction "DGND3_E19") (pintype "bidirectional"))
      (node (ref "IC1") (pin "E20") (pinfunction "DGND4_E20") (pintype "bidirectional"))
      (node (ref "IC1") (pin "F19") (pinfunction "DGND6_F19") (pintype "bidirectional"))
      (node (ref "IC1") (pin "F8") (pinfunction "DGND5_F8") (pintype "bidirectional"))
      (node (ref "IC1") (pin "G11") (pinfunction "DGND9_G11") (pintype "bidirectional"))
      (node (ref "IC1") (pin "G12") (pinfunction "DGND10_G12") (pintype "bidirectional"))
      (node (ref "IC1") (pin "G19") (pinfunction "DGND11_G19") (pintype "bidirectional"))
      (node (ref "IC1") (pin "G8") (pinfunction "DGND7_G8") (pintype "bidirectional"))
      (node (ref "IC1") (pin "G9") (pinfunction "DGND8_G9") (pintype "bidirectional"))
      (node (ref "IC1") (pin "H10") (pinfunction "DGND16_H10") (pintype "bidirectional"))
      (node (ref "IC1") (pin "H12") (pinfunction "DGND17_H12") (pintype "bidirectional"))
      (node (ref "IC1") (pin "H19") (pinfunction "DGND18_H19") (pintype "bidirectional"))
      (node (ref "IC1") (pin "H6") (pinfunction "DGND12_H6") (pintype "bidirectional"))
      (node (ref "IC1") (pin "H7") (pinfunction "DGND13_H7") (pintype "bidirectional"))
      (node (ref "IC1") (pin "H8") (pinfunction "DGND14_H8") (pintype "bidirectional"))
      (node (ref "IC1") (pin "H9") (pinfunction "DGND15_H9") (pintype "bidirectional"))
      (node (ref "IC1") (pin "J10") (pinfunction "DGND23_J10") (pintype "bidirectional"))
      (node (ref "IC1") (pin "J11") (pinfunction "DGND24_J11") (pintype "bidirectional"))
      (node (ref "IC1") (pin "J19") (pinfunction "DGND25_J19") (pintype "bidirectional"))
      (node (ref "IC1") (pin "J20") (pinfunction "DGND26_J20") (pintype "bidirectional"))
      (node (ref "IC1") (pin "J6") (pinfunction "DGND19_J6") (pintype "bidirectional"))
      (node (ref "IC1") (pin "J7") (pinfunction "DGND20_J7") (pintype "bidirectional"))
      (node (ref "IC1") (pin "J8") (pinfunction "DGND21_J8") (pintype "bidirectional"))
      (node (ref "IC1") (pin "J9") (pinfunction "DGND22_J9") (pintype "bidirectional"))
      (node (ref "IC1") (pin "K10") (pinfunction "DGND29_K10") (pintype "bidirectional"))
      (node (ref "IC1") (pin "K11") (pinfunction "DGND30_K11") (pintype "bidirectional"))
      (node (ref "IC1") (pin "K19") (pinfunction "DGND31_K19") (pintype "bidirectional"))
      (node (ref "IC1") (pin "K7") (pinfunction "DGND27_K7") (pintype "bidirectional"))
      (node (ref "IC1") (pin "K9") (pinfunction "DGND28_K9") (pintype "bidirectional"))
      (node (ref "IC1") (pin "L10") (pinfunction "DGND32_L10") (pintype "bidirectional"))
      (node (ref "IC1") (pin "L11") (pinfunction "DGND33_L11") (pintype "bidirectional"))
      (node (ref "IC1") (pin "L12") (pinfunction "DGND34_L12") (pintype "bidirectional"))
      (node (ref "IC1") (pin "L13") (pinfunction "DGND35_L13") (pintype "bidirectional"))
      (node (ref "IC1") (pin "L19") (pinfunction "DGND36_L19") (pintype "bidirectional"))
      (node (ref "IC1") (pin "M10") (pinfunction "DGND42_M10") (pintype "bidirectional"))
      (node (ref "IC1") (pin "M12") (pinfunction "DGND43_M12") (pintype "bidirectional"))
      (node (ref "IC1") (pin "M14") (pinfunction "DGND44_M14") (pintype "bidirectional"))
      (node (ref "IC1") (pin "M19") (pinfunction "DGND45_M19") (pintype "bidirectional"))
      (node (ref "IC1") (pin "M6") (pinfunction "DGND38_M6") (pintype "bidirectional"))
      (node (ref "IC1") (pin "M7") (pinfunction "DGND39_M7") (pintype "bidirectional"))
      (node (ref "IC1") (pin "M8") (pinfunction "DGND40_M8") (pintype "bidirectional"))
      (node (ref "IC1") (pin "M9") (pinfunction "DGND41_M9") (pintype "bidirectional"))
      (node (ref "IC1") (pin "N10") (pinfunction "DGND47_N10") (pintype "bidirectional"))
      (node (ref "IC1") (pin "N11") (pinfunction "DGND48_N11") (pintype "bidirectional"))
      (node (ref "IC1") (pin "N14") (pinfunction "DGND49_N14") (pintype "bidirectional"))
      (node (ref "IC1") (pin "N19") (pinfunction "DGND50_N19") (pintype "bidirectional"))
      (node (ref "IC1") (pin "N20") (pinfunction "DGND51_N20") (pintype "bidirectional"))
      (node (ref "IC1") (pin "N7") (pinfunction "DGND46_N7") (pintype "bidirectional"))
      (node (ref "IC1") (pin "P19") (pinfunction "DGND52_P19") (pintype "bidirectional"))
      (node (ref "IC1") (pin "P20") (pinfunction "DGND53_P20") (pintype "bidirectional"))
      (node (ref "IC1") (pin "R19") (pinfunction "DGND54_R19") (pintype "bidirectional"))
      (node (ref "IC1") (pin "R20") (pinfunction "DGND55_R20") (pintype "bidirectional"))
      (node (ref "IC1") (pin "T19") (pinfunction "DGND56_T19") (pintype "bidirectional"))
      (node (ref "IC1") (pin "T20") (pinfunction "DGND57_T20") (pintype "bidirectional"))
      (node (ref "IC1") (pin "U19") (pinfunction "DGND58_U19") (pintype "bidirectional"))
      (node (ref "IC1") (pin "V1") (pinfunction "DGND59_V1") (pintype "bidirectional"))
      (node (ref "IC1") (pin "V18") (pinfunction "DGND60_V18") (pintype "bidirectional"))
      (node (ref "IC1") (pin "V19") (pinfunction "DGND61_V19") (pintype "bidirectional"))
      (node (ref "IC1") (pin "W10") (pinfunction "DGND70_W10") (pintype "bidirectional"))
      (node (ref "IC1") (pin "W11") (pinfunction "DGND71_W11") (pintype "bidirectional"))
      (node (ref "IC1") (pin "W12") (pinfunction "DGND72_W12") (pintype "bidirectional"))
      (node (ref "IC1") (pin "W13") (pinfunction "DGND73_W13") (pintype "bidirectional"))
      (node (ref "IC1") (pin "W14") (pinfunction "DGND74_W14") (pintype "bidirectional"))
      (node (ref "IC1") (pin "W15") (pinfunction "DGND75_W15") (pintype "bidirectional"))
      (node (ref "IC1") (pin "W16") (pinfunction "DGND76_W16") (pintype "bidirectional"))
      (node (ref "IC1") (pin "W17") (pinfunction "DGND77_W17") (pintype "bidirectional"))
      (node (ref "IC1") (pin "W18") (pinfunction "DGND78_W18") (pintype "bidirectional"))
      (node (ref "IC1") (pin "W19") (pinfunction "DGND79_W19") (pintype "bidirectional"))
      (node (ref "IC1") (pin "W2") (pinfunction "DGND62_W2") (pintype "bidirectional"))
      (node (ref "IC1") (pin "W20") (pinfunction "DGND80_W20") (pintype "bidirectional"))
      (node (ref "IC1") (pin "W3") (pinfunction "DGND63_W3") (pintype "bidirectional"))
      (node (ref "IC1") (pin "W5") (pinfunction "DGND65_W5") (pintype "bidirectional"))
      (node (ref "IC1") (pin "W6") (pinfunction "DGND66_W6") (pintype "bidirectional"))
      (node (ref "IC1") (pin "W7") (pinfunction "DGND67_W7") (pintype "bidirectional"))
      (node (ref "IC1") (pin "W8") (pinfunction "DGND68_W8") (pintype "bidirectional"))
      (node (ref "IC1") (pin "W9") (pinfunction "DGND69_W9") (pintype "bidirectional"))
      (node (ref "IC1") (pin "Y10") (pinfunction "DGND83_Y10") (pintype "bidirectional"))
      (node (ref "IC1") (pin "Y12") (pinfunction "DGND84_Y12") (pintype "bidirectional"))
      (node (ref "IC1") (pin "Y15") (pinfunction "DGND85_Y15") (pintype "bidirectional"))
      (node (ref "IC1") (pin "Y18") (pinfunction "DGND86_Y18") (pintype "bidirectional"))
      (node (ref "IC1") (pin "Y7") (pinfunction "DGND82_Y7") (pintype "bidirectional"))
      (node (ref "IC10") (pin "11") (pinfunction "GND_11") (pintype "bidirectional"))
      (node (ref "IC10") (pin "TP") (pinfunction "TP_TP") (pintype "bidirectional"))
      (node (ref "IC11") (pin "11") (pinfunction "GND_11") (pintype "bidirectional"))
      (node (ref "IC11") (pin "TP") (pinfunction "TP_TP") (pintype "bidirectional"))
      (node (ref "IC12") (pin "1") (pinfunction "GND_1") (pintype "bidirectional"))
      (node (ref "IC12") (pin "9") (pinfunction "THERMAL_9") (pintype "bidirectional"))
      (node (ref "IC13") (pin "4") (pinfunction "GND_4") (pintype "bidirectional"))
      (node (ref "IC14") (pin "4") (pinfunction "GND_4") (pintype "bidirectional"))
      (node (ref "IC15") (pin "4") (pinfunction "GND_4") (pintype "bidirectional"))
      (node (ref "IC17") (pin "1") (pinfunction "1OE#_1") (pintype "bidirectional"))
      (node (ref "IC17") (pin "4") (pinfunction "GND_4") (pintype "bidirectional"))
      (node (ref "IC18") (pin "3") (pinfunction "GND1_3") (pintype "bidirectional"))
      (node (ref "IC18") (pin "6") (pinfunction "GND2_6") (pintype "bidirectional"))
      (node (ref "IC19") (pin "2") (pinfunction "GND_2") (pintype "bidirectional"))
      (node (ref "IC2") (pin "3") (pinfunction "GND_3") (pintype "bidirectional"))
      (node (ref "IC22") (pin "C4") (pinfunction "VSSQ1_C4") (pintype "bidirectional"))
      (node (ref "IC22") (pin "E7") (pinfunction "VSS1_E7") (pintype "bidirectional"))
      (node (ref "IC22") (pin "G5") (pinfunction "VSS2_G5") (pintype "bidirectional"))
      (node (ref "IC22") (pin "H10") (pinfunction "VSS3_H10") (pintype "bidirectional"))
      (node (ref "IC22") (pin "K8") (pinfunction "VSS4_K8") (pintype "bidirectional"))
      (node (ref "IC22") (pin "N2") (pinfunction "VSSQ2_N2") (pintype "bidirectional"))
      (node (ref "IC22") (pin "N5") (pinfunction "VSSQ3_N5") (pintype "bidirectional"))
      (node (ref "IC22") (pin "P4") (pinfunction "VSSQ4_P4") (pintype "bidirectional"))
      (node (ref "IC22") (pin "P6") (pinfunction "VSSQ5_P6") (pintype "bidirectional"))
      (node (ref "IC3") (pin "3") (pinfunction "GND_3") (pintype "bidirectional"))
      (node (ref "IC4") (pin "2") (pinfunction "VSS_2") (pintype "bidirectional"))
      (node (ref "IC7") (pin "3") (pinfunction "GND1_3") (pintype "bidirectional"))
      (node (ref "IC7") (pin "8") (pinfunction "GND2_8") (pintype "bidirectional"))
      (node (ref "IC8") (pin "3") (pinfunction "GND1_3") (pintype "bidirectional"))
      (node (ref "IC8") (pin "8") (pinfunction "GND2_8") (pintype "bidirectional"))
      (node (ref "IC9") (pin "16") (pinfunction "VPC[2]_16") (pintype "bidirectional"))
      (node (ref "IC9") (pin "17") (pinfunction "VPC[1]_17") (pintype "bidirectional"))
      (node (ref "IC9") (pin "18") (pinfunction "VPC[0]_18") (pintype "bidirectional"))
      (node (ref "IC9") (pin "19") (pinfunction "VPP_19") (pintype "bidirectional"))
      (node (ref "IC9") (pin "53") (pinfunction "A0_I2C_53") (pintype "bidirectional"))
      (node (ref "IC9") (pin "54") (pinfunction "A1_I2C_54") (pintype "bidirectional"))
      (node (ref "IC9") (pin "61") (pinfunction "VPA[2]_61") (pintype "bidirectional"))
      (node (ref "IC9") (pin "62") (pinfunction "VPA[1]_62") (pintype "bidirectional"))
      (node (ref "IC9") (pin "63") (pinfunction "VPA[0]_63") (pintype "bidirectional"))
      (node (ref "IC9") (pin "65") (pinfunction "GND.PAD_65") (pintype "bidirectional"))
      (node (ref "IC9") (pin "8") (pinfunction "VPB[1]_8") (pintype "bidirectional"))
      (node (ref "IC9") (pin "9") (pinfunction "VPB[0]_9") (pintype "bidirectional"))
      (node (ref "MOD1") (pin "1") (pinfunction "GND1_1") (pintype "bidirectional"))
      (node (ref "MOD1") (pin "15") (pinfunction "GND4_15") (pintype "bidirectional"))
      (node (ref "MOD1") (pin "16") (pinfunction "GND5_16") (pintype "bidirectional"))
      (node (ref "MOD1") (pin "17") (pinfunction "GND6_17") (pintype "bidirectional"))
      (node (ref "MOD1") (pin "19") (pinfunction "GND7_19") (pintype "bidirectional"))
      (node (ref "MOD1") (pin "20") (pinfunction "GND8_20") (pintype "bidirectional"))
      (node (ref "MOD1") (pin "23") (pinfunction "GND9_23") (pintype "bidirectional"))
      (node (ref "MOD1") (pin "24") (pinfunction "GND10_24") (pintype "bidirectional"))
      (node (ref "MOD1") (pin "28") (pinfunction "GND11_28") (pintype "bidirectional"))
      (node (ref "MOD1") (pin "29") (pinfunction "GND12_29") (pintype "bidirectional"))
      (node (ref "MOD1") (pin "30") (pinfunction "GND13_30") (pintype "bidirectional"))
      (node (ref "MOD1") (pin "31") (pinfunction "GND14_31") (pintype "bidirectional"))
      (node (ref "MOD1") (pin "33") (pinfunction "GND15_33") (pintype "bidirectional"))
      (node (ref "MOD1") (pin "34") (pinfunction "GND16_34") (pintype "bidirectional"))
      (node (ref "MOD1") (pin "35") (pinfunction "GND17_35") (pintype "bidirectional"))
      (node (ref "MOD1") (pin "37") (pinfunction "GND18_37") (pintype "bidirectional"))
      (node (ref "MOD1") (pin "39") (pinfunction "GND19_39") (pintype "bidirectional"))
      (node (ref "MOD1") (pin "44") (pinfunction "GND20_44") (pintype "bidirectional"))
      (node (ref "MOD1") (pin "45") (pinfunction "GND21_45") (pintype "bidirectional"))
      (node (ref "MOD1") (pin "48") (pinfunction "GND22_48") (pintype "bidirectional"))
      (node (ref "MOD1") (pin "49") (pinfunction "GND23_49") (pintype "bidirectional"))
      (node (ref "MOD1") (pin "54") (pinfunction "GND24_54") (pintype "bidirectional"))
      (node (ref "MOD1") (pin "55") (pinfunction "GND25_55") (pintype "bidirectional"))
      (node (ref "MOD1") (pin "59") (pinfunction "GND26_59") (pintype "bidirectional"))
      (node (ref "MOD1") (pin "61") (pinfunction "GND27_61") (pintype "bidirectional"))
      (node (ref "MOD1") (pin "63") (pinfunction "GND28_63") (pintype "bidirectional"))
      (node (ref "MOD1") (pin "64") (pinfunction "GND29_64") (pintype "bidirectional"))
      (node (ref "MOD1") (pin "7") (pinfunction "GND2_7") (pintype "bidirectional"))
      (node (ref "MOD1") (pin "9") (pinfunction "GND3_9") (pintype "bidirectional"))
      (node (ref "MOD1") (pin "G1") (pinfunction "G1_G1") (pintype "bidirectional"))
      (node (ref "MOD1") (pin "G10") (pinfunction "G10_G10") (pintype "bidirectional"))
      (node (ref "MOD1") (pin "G11") (pinfunction "G11_G11") (pintype "bidirectional"))
      (node (ref "MOD1") (pin "G12") (pinfunction "G12_G12") (pintype "bidirectional"))
      (node (ref "MOD1") (pin "G13") (pinfunction "G13_G13") (pintype "bidirectional"))
      (node (ref "MOD1") (pin "G14") (pinfunction "G14_G14") (pintype "bidirectional"))
      (node (ref "MOD1") (pin "G15") (pinfunction "G15_G15") (pintype "bidirectional"))
      (node (ref "MOD1") (pin "G16") (pinfunction "G16_G16") (pintype "bidirectional"))
      (node (ref "MOD1") (pin "G17") (pinfunction "G17_G17") (pintype "bidirectional"))
      (node (ref "MOD1") (pin "G18") (pinfunction "G18_G18") (pintype "bidirectional"))
      (node (ref "MOD1") (pin "G19") (pinfunction "G19_G19") (pintype "bidirectional"))
      (node (ref "MOD1") (pin "G2") (pinfunction "G2_G2") (pintype "bidirectional"))
      (node (ref "MOD1") (pin "G20") (pinfunction "G20_G20") (pintype "bidirectional"))
      (node (ref "MOD1") (pin "G21") (pinfunction "G21_G21") (pintype "bidirectional"))
      (node (ref "MOD1") (pin "G22") (pinfunction "G22_G22") (pintype "bidirectional"))
      (node (ref "MOD1") (pin "G23") (pinfunction "G23_G23") (pintype "bidirectional"))
      (node (ref "MOD1") (pin "G24") (pinfunction "G24_G24") (pintype "bidirectional"))
      (node (ref "MOD1") (pin "G25") (pinfunction "G25_G25") (pintype "bidirectional"))
      (node (ref "MOD1") (pin "G26") (pinfunction "G26_G26") (pintype "bidirectional"))
      (node (ref "MOD1") (pin "G27") (pinfunction "G27_G27") (pintype "bidirectional"))
      (node (ref "MOD1") (pin "G28") (pinfunction "G28_G28") (pintype "bidirectional"))
      (node (ref "MOD1") (pin "G29") (pinfunction "G29_G29") (pintype "bidirectional"))
      (node (ref "MOD1") (pin "G3") (pinfunction "G3_G3") (pintype "bidirectional"))
      (node (ref "MOD1") (pin "G30") (pinfunction "G30_G30") (pintype "bidirectional"))
      (node (ref "MOD1") (pin "G31") (pinfunction "G31_G31") (pintype "bidirectional"))
      (node (ref "MOD1") (pin "G32") (pinfunction "G32_G32") (pintype "bidirectional"))
      (node (ref "MOD1") (pin "G33") (pinfunction "G33_G33") (pintype "bidirectional"))
      (node (ref "MOD1") (pin "G34") (pinfunction "G34_G34") (pintype "bidirectional"))
      (node (ref "MOD1") (pin "G35") (pinfunction "G35_G35") (pintype "bidirectional"))
      (node (ref "MOD1") (pin "G36") (pinfunction "G36_G36") (pintype "bidirectional"))
      (node (ref "MOD1") (pin "G4") (pinfunction "G4_G4") (pintype "bidirectional"))
      (node (ref "MOD1") (pin "G5") (pinfunction "G5_G5") (pintype "bidirectional"))
      (node (ref "MOD1") (pin "G6") (pinfunction "G6_G6") (pintype "bidirectional"))
      (node (ref "MOD1") (pin "G7") (pinfunction "G7_G7") (pintype "bidirectional"))
      (node (ref "MOD1") (pin "G8") (pinfunction "G8_G8") (pintype "bidirectional"))
      (node (ref "MOD1") (pin "G9") (pinfunction "G9_G9") (pintype "bidirectional"))
      (node (ref "OSC1") (pin "2") (pinfunction "GND_2") (pintype "bidirectional"))
      (node (ref "OSC2") (pin "2") (pinfunction "GND_2") (pintype "bidirectional"))
      (node (ref "P2") (pin "10") (pinfunction "GND2_10") (pintype "bidirectional"))
      (node (ref "P2") (pin "12") (pinfunction "GND3_12") (pintype "bidirectional"))
      (node (ref "P2") (pin "16") (pinfunction "GND4_16") (pintype "bidirectional"))
      (node (ref "P2") (pin "20") (pinfunction "GND5_20") (pintype "bidirectional"))
      (node (ref "P2") (pin "4") (pinfunction "TDIS_4") (pintype "bidirectional"))
      (node (ref "P2") (pin "8") (pinfunction "GND1_8") (pintype "bidirectional"))
      (node (ref "P8") (pin "1") (pinfunction "1_1") (pintype "passive"))
      (node (ref "P8") (pin "2") (pinfunction "2_2") (pintype "passive"))
      (node (ref "P9") (pin "1") (pinfunction "1_1") (pintype "passive"))
      (node (ref "P9") (pin "2") (pinfunction "2_2") (pintype "passive"))
      (node (ref "P9") (pin "43") (pinfunction "43_43") (pintype "passive"))
      (node (ref "P9") (pin "44") (pinfunction "44_44") (pintype "passive"))
      (node (ref "P9") (pin "45") (pinfunction "45_45") (pintype "passive"))
      (node (ref "P9") (pin "46") (pinfunction "46_46") (pintype "passive"))
      (node (ref "POWER") (pin "1") (pinfunction "1_1") (pintype "bidirectional"))
      (node (ref "POWER") (pin "2") (pinfunction "2_2") (pintype "bidirectional"))
      (node (ref "R10") (pin "2") (pinfunction "2_2") (pintype "passive"))
      (node (ref "R106") (pin "2") (pinfunction "2_2") (pintype "passive"))
      (node (ref "R108") (pin "2") (pinfunction "2_2") (pintype "passive"))
      (node (ref "R109") (pin "2") (pinfunction "2_2") (pintype "passive"))
      (node (ref "R11") (pin "2") (pinfunction "2_2") (pintype "passive"))
      (node (ref "R114") (pin "1") (pinfunction "1_1") (pintype "passive"))
      (node (ref "R119") (pin "2") (pinfunction "2_2") (pintype "passive"))
      (node (ref "R123") (pin "2") (pinfunction "2_2") (pintype "passive"))
      (node (ref "R17") (pin "1") (pinfunction "1_1") (pintype "passive"))
      (node (ref "R19") (pin "2") (pinfunction "2_2") (pintype "passive"))
      (node (ref "R22") (pin "2") (pinfunction "2_2") (pintype "passive"))
      (node (ref "R24") (pin "1") (pinfunction "1_1") (pintype "passive"))
      (node (ref "R27") (pin "2") (pinfunction "2_2") (pintype "passive"))
      (node (ref "R52") (pin "2") (pinfunction "2_2") (pintype "passive"))
      (node (ref "R55") (pin "1") (pinfunction "1_1") (pintype "passive"))
      (node (ref "R57") (pin "1") (pinfunction "1_1") (pintype "passive"))
      (node (ref "R61") (pin "1") (pinfunction "1_1") (pintype "passive"))
      (node (ref "R63") (pin "1") (pinfunction "1_1") (pintype "passive"))
      (node (ref "R65") (pin "1") (pinfunction "1_1") (pintype "passive"))
      (node (ref "R67") (pin "1") (pinfunction "1_1") (pintype "passive"))
      (node (ref "R69") (pin "1") (pinfunction "1_1") (pintype "passive"))
      (node (ref "R71") (pin "1") (pinfunction "1_1") (pintype "passive"))
      (node (ref "R73") (pin "1") (pinfunction "1_1") (pintype "passive"))
      (node (ref "R75") (pin "1") (pinfunction "1_1") (pintype "passive"))
      (node (ref "R85") (pin "1") (pinfunction "1_1") (pintype "passive"))
      (node (ref "R87") (pin "1") (pinfunction "1_1") (pintype "passive"))
      (node (ref "R94") (pin "2") (pinfunction "2_2") (pintype "passive"))
      (node (ref "R95") (pin "2") (pinfunction "2_2") (pintype "passive"))
      (node (ref "RESET") (pin "1") (pinfunction "1_1") (pintype "bidirectional"))
      (node (ref "RESET") (pin "2") (pinfunction "2_2") (pintype "bidirectional"))
      (node (ref "S2") (pin "3") (pinfunction "3_3") (pintype "bidirectional"))
      (node (ref "S2") (pin "4") (pinfunction "4_4") (pintype "bidirectional"))
      (node (ref "T3") (pin "S") (pinfunction "S_S") (pintype "bidirectional"))
      (node (ref "T4") (pin "S") (pinfunction "S_S") (pintype "bidirectional"))
      (node (ref "TP5") (pin "P$1") (pinfunction "TP_P$1") (pintype "bidirectional"))
      (node (ref "USR0") (pin "K") (pinfunction "K_K") (pintype "passive"))
      (node (ref "USR1") (pin "K") (pinfunction "K_K") (pintype "passive"))
      (node (ref "USR2") (pin "K") (pinfunction "K_K") (pintype "passive"))
      (node (ref "USR3") (pin "K") (pinfunction "K_K") (pintype "passive"))
      (node (ref "X1") (pin "1") (pinfunction "1_1") (pintype "passive"))
      (node (ref "X12") (pin "OUT") (pinfunction "OUT_OUT") (pintype "bidirectional"))
      (node (ref "X2") (pin "6") (pinfunction "VSS_6") (pintype "bidirectional"))
      (node (ref "X2") (pin "GND") (pinfunction "GND_GND") (pintype "bidirectional"))
      (node (ref "X3") (pin "4") (pinfunction "GND_4") (pintype "bidirectional"))
      (node (ref "X4") (pin "GND") (pinfunction "GND_GND") (pintype "input"))
      (node (ref "X5") (pin "10") (pinfunction "TMDS.DATA0.SHIELD_10") (pintype "bidirectional"))
      (node (ref "X5") (pin "13") (pinfunction "TMDS.CLOCK.SHIELD_13") (pintype "bidirectional"))
      (node (ref "X5") (pin "16") (pinfunction "DDC/CEC.GND_16") (pintype "bidirectional"))
      (node (ref "X5") (pin "4") (pinfunction "TMDS.DATA2.SHIELD_4") (pintype "bidirectional"))
      (node (ref "X5") (pin "7") (pinfunction "TMDS.DATA1.SHIELD_7") (pintype "bidirectional"))
    )
    (net (code "196") (name "Net-(ANT1-PadSIG)") (class "Default")
      (node (ref "ANT1") (pin "SIG") (pinfunction "SIG_SIG") (pintype "bidirectional"))
      (node (ref "C46") (pin "1") (pinfunction "1_1") (pintype "passive"))
    )
    (net (code "197") (name "Net-(ANT2-PadSIG)") (class "Default")
      (node (ref "ANT2") (pin "SIG") (pinfunction "SIG_SIG") (pintype "bidirectional"))
      (node (ref "C60") (pin "1") (pinfunction "1_1") (pintype "passive"))
    )
    (net (code "198") (name "Net-(BT-PadA)") (class "Default")
      (node (ref "BT") (pin "A") (pinfunction "A_A") (pintype "passive"))
      (node (ref "R124") (pin "1") (pinfunction "1_1") (pintype "passive"))
    )
    (net (code "199") (name "Net-(BT-PadK)") (class "Default")
      (node (ref "BT") (pin "K") (pinfunction "K_K") (pintype "passive"))
      (node (ref "T4") (pin "D") (pinfunction "D_D") (pintype "bidirectional"))
    )
    (net (code "200") (name "Net-(D1-ANODE)") (class "Default")
      (node (ref "D1") (pin "A") (pinfunction "ANODE_A") (pintype "bidirectional"))
      (node (ref "R120") (pin "2") (pinfunction "2_2") (pintype "passive"))
    )
    (net (code "201") (name "Net-(FB3-P$1)") (class "Default")
      (node (ref "C58") (pin "1") (pinfunction "1_1") (pintype "passive"))
      (node (ref "FB3") (pin "1") (pinfunction "P$1_1") (pintype "bidirectional"))
      (node (ref "FB4") (pin "1") (pinfunction "P$1_1") (pintype "bidirectional"))
      (node (ref "IC12") (pin "6") (pinfunction "OUT1_6") (pintype "bidirectional"))
      (node (ref "IC12") (pin "7") (pinfunction "OUT2_7") (pintype "bidirectional"))
      (node (ref "IC12") (pin "8") (pinfunction "OUT3_8") (pintype "bidirectional"))
      (node (ref "IC15") (pin "6") (pinfunction "VBUS_6") (pintype "bidirectional"))
    )
    (net (code "202") (name "Net-(FB3-P$2)") (class "Default")
      (node (ref "FB3") (pin "2") (pinfunction "P$2_2") (pintype "bidirectional"))
      (node (ref "X3") (pin "1") (pinfunction "VBUS_1") (pintype "bidirectional"))
    )
    (net (code "203") (name "Net-(IC1A-(EMMC_RSTN)GPIO1_20)") (class "Default")
      (node (ref "IC1") (pin "R14") (pinfunction "(EMMC_RSTN)GPIO1_20_R14") (pintype "bidirectional"))
      (node (ref "IC3") (pin "2") (pinfunction "A_2") (pintype "bidirectional"))
    )
    (net (code "204") (name "Net-(IC1A-CLKOUT1)") (class "Default")
      (node (ref "FB5") (pin "1") (pinfunction "1_1") (pintype "passive"))
      (node (ref "IC1") (pin "A15") (pinfunction "CLKOUT1_A15") (pintype "bidirectional"))
    )
    (net (code "205") (name "Net-(IC1A-CLKOUT2)") (class "Default")
      (node (ref "FB7") (pin "2") (pinfunction "2_2") (pintype "passive"))
      (node (ref "IC1") (pin "D14") (pinfunction "CLKOUT2_D14") (pintype "bidirectional"))
    )
    (net (code "206") (name "Net-(IC1A-DGND0)") (class "Default")
      (node (ref "C3") (pin "2") (pinfunction "2_2") (pintype "passive"))
      (node (ref "C4") (pin "2") (pinfunction "2_2") (pintype "passive"))
      (node (ref "IC1") (pin "L20") (pinfunction "DGND0_L20") (pintype "bidirectional"))
    )
    (net (code "207") (name "Net-(IC1A-DGND1)") (class "Default")
      (node (ref "C5") (pin "2") (pinfunction "2_2") (pintype "passive"))
      (node (ref "C6") (pin "2") (pinfunction "2_2") (pintype "passive"))
      (node (ref "IC1") (pin "G20") (pinfunction "DGND1_G20") (pintype "bidirectional"))
    )
    (net (code "208") (name "Net-(IC1A-GPIO3_20)") (class "Default")
      (node (ref "IC1") (pin "D13") (pinfunction "GPIO3_20_D13") (pintype "bidirectional"))
      (node (ref "R14") (pin "2") (pinfunction "2_2") (pintype "passive"))
    )
    (net (code "209") (name "Net-(IC1A-OSC0_IN)") (class "Default")
      (node (ref "C3") (pin "1") (pinfunction "1_1") (pintype "passive"))
      (node (ref "IC1") (pin "M20") (pinfunction "OSC0_IN_M20") (pintype "bidirectional"))
      (node (ref "Q4") (pin "2") (pinfunction "P$2_2") (pintype "passive"))
      (node (ref "R8") (pin "2") (pinfunction "2_2") (pintype "passive"))
    )
    (net (code "210") (name "Net-(IC1A-OSC0_OUT)") (class "Default")
      (node (ref "C4") (pin "1") (pinfunction "1_1") (pintype "passive"))
      (node (ref "IC1") (pin "K20") (pinfunction "OSC0_OUT_K20") (pintype "bidirectional"))
      (node (ref "Q4") (pin "1") (pinfunction "P$1_1") (pintype "passive"))
      (node (ref "R8") (pin "1") (pinfunction "1_1") (pintype "passive"))
    )
    (net (code "211") (name "Net-(IC1A-OSC1_IN)") (class "Default")
      (node (ref "C5") (pin "1") (pinfunction "1_1") (pintype "passive"))
      (node (ref "IC1") (pin "H20") (pinfunction "OSC1_IN_H20") (pintype "bidirectional"))
      (node (ref "Q2") (pin "P$1") (pinfunction "P$1_P$1") (pintype "passive"))
      (node (ref "R56") (pin "2") (pinfunction "2_2") (pintype "passive"))
    )
    (net (code "212") (name "Net-(IC1A-OSC1_OUT)") (class "Default")
      (node (ref "C6") (pin "1") (pinfunction "1_1") (pintype "passive"))
      (node (ref "IC1") (pin "F20") (pinfunction "OSC1_OUT_F20") (pintype "bidirectional"))
      (node (ref "Q2") (pin "P$2") (pinfunction "P$2_P$2") (pintype "passive"))
      (node (ref "R56") (pin "1") (pinfunction "1_1") (pintype "passive"))
    )
    (net (code "213") (name "Net-(IC1B-AIN7)") (class "Default")
      (node (ref "IC1") (pin "C9") (pinfunction "AIN7_C9") (pintype "bidirectional"))
      (node (ref "R21") (pin "2") (pinfunction "2_2") (pintype "passive"))
      (node (ref "R22") (pin "1") (pinfunction "1_1") (pintype "passive"))
    )
    (net (code "214") (name "Net-(IC1B-GPIO0_7)") (class "Default")
      (node (ref "IC1") (pin "C18") (pinfunction "GPIO0_7_C18") (pintype "bidirectional"))
      (node (ref "R36") (pin "2") (pinfunction "2_2") (pintype "passive"))
    )
    (net (code "215") (name "Net-(IC1B-GPIO3_18)") (class "Default")
      (node (ref "IC1") (pin "B12") (pinfunction "GPIO3_18_B12") (pintype "bidirectional"))
      (node (ref "R38") (pin "2") (pinfunction "2_2") (pintype "passive"))
    )
    (net (code "216") (name "Net-(IC1B-USB0_VBUS)") (class "Default")
      (node (ref "IC1") (pin "P15") (pinfunction "USB0_VBUS_P15") (pintype "bidirectional"))
      (node (ref "R26") (pin "1") (pinfunction "1_1") (pintype "passive"))
    )
    (net (code "217") (name "Net-(IC1B-USB1_ID)") (class "Default")
      (node (ref "IC1") (pin "P17") (pinfunction "USB1_ID_P17") (pintype "bidirectional"))
      (node (ref "R27") (pin "1") (pinfunction "1_1") (pintype "passive"))
    )
    (net (code "218") (name "Net-(IC1C-PMIC_POWER_EN)") (class "Default")
      (node (ref "IC1") (pin "C6") (pinfunction "PMIC_POWER_EN_C6") (pintype "bidirectional"))
      (node (ref "IC1") (pin "D19") (pinfunction "PWR_EN_D19") (pintype "bidirectional"))
    )
    (net (code "219") (name "Net-(IC1E-RTC_KALDO_ENN)") (class "Default")
      (node (ref "IC1") (pin "B4") (pinfunction "RTC_KALDO_ENN_B4") (pintype "bidirectional"))
      (node (ref "R24") (pin "2") (pinfunction "2_2") (pintype "passive"))
    )
    (net (code "220") (name "Net-(IC3-Y)") (class "Default")
      (node (ref "IC3") (pin "4") (pinfunction "Y_4") (pintype "bidirectional"))
      (node (ref "R29") (pin "2") (pinfunction "2_2") (pintype "passive"))
    )
    (net (code "221") (name "Net-(IC4-WP)") (class "Default")
      (node (ref "IC4") (pin "5") (pinfunction "WP_5") (pintype "bidirectional"))
      (node (ref "R40") (pin "2") (pinfunction "2_2") (pintype "passive"))
      (node (ref "TP1") (pin "P$1") (pinfunction "TP_P$1") (pintype "bidirectional"))
    )
    (net (code "222") (name "Net-(IC5-C)") (class "Default")
      (node (ref "IC5") (pin "2") (pinfunction "C_2") (pintype "passive"))
      (node (ref "R44") (pin "2") (pinfunction "2_2") (pintype "passive"))
      (node (ref "R45") (pin "1") (pinfunction "1_1") (pintype "passive"))
      (node (ref "T1") (pin "B") (pinfunction "B_B") (pintype "passive"))
    )
    (net (code "223") (name "Net-(IC5-FB)") (class "Default")
      (node (ref "IC5") (pin "1") (pinfunction "FB_1") (pintype "passive"))
      (node (ref "R45") (pin "2") (pinfunction "2_2") (pintype "passive"))
      (node (ref "R46") (pin "2") (pinfunction "2_2") (pintype "passive"))
      (node (ref "R47") (pin "1") (pinfunction "1_1") (pintype "passive"))
    )
    (net (code "224") (name "Net-(IC6-C)") (class "Default")
      (node (ref "IC6") (pin "2") (pinfunction "C_2") (pintype "passive"))
      (node (ref "R48") (pin "2") (pinfunction "2_2") (pintype "passive"))
      (node (ref "R49") (pin "1") (pinfunction "1_1") (pintype "passive"))
      (node (ref "T2") (pin "B") (pinfunction "B_B") (pintype "passive"))
    )
    (net (code "225") (name "Net-(IC6-FB)") (class "Default")
      (node (ref "IC6") (pin "1") (pinfunction "FB_1") (pintype "passive"))
      (node (ref "R49") (pin "2") (pinfunction "2_2") (pintype "passive"))
      (node (ref "R50") (pin "2") (pinfunction "2_2") (pintype "passive"))
      (node (ref "R51") (pin "1") (pinfunction "1_1") (pintype "passive"))
    )
    (net (code "226") (name "Net-(IC9-DSCL)") (class "Default")
      (node (ref "IC9") (pin "33") (pinfunction "DSCL_33") (pintype "bidirectional"))
      (node (ref "R115") (pin "2") (pinfunction "2_2") (pintype "passive"))
      (node (ref "X5") (pin "17") (pinfunction "SCL_17") (pintype "bidirectional"))
    )
    (net (code "227") (name "Net-(IC9-DSDA)") (class "Default")
      (node (ref "IC9") (pin "32") (pinfunction "DSDA_32") (pintype "bidirectional"))
      (node (ref "R118") (pin "2") (pinfunction "2_2") (pintype "passive"))
      (node (ref "X5") (pin "18") (pinfunction "SDA_18") (pintype "bidirectional"))
    )
    (net (code "228") (name "Net-(IC10-B1)") (class "Default")
      (node (ref "IC10") (pin "20") (pinfunction "B1_20") (pintype "bidirectional"))
      (node (ref "R130") (pin "2") (pinfunction "2_2") (pintype "passive"))
    )
    (net (code "229") (name "Net-(IC10-B2)") (class "Default")
      (node (ref "IC10") (pin "18") (pinfunction "B2_18") (pintype "bidirectional"))
      (node (ref "R129") (pin "2") (pinfunction "2_2") (pintype "passive"))
    )
    (net (code "230") (name "Net-(IC10-B3)") (class "Default")
      (node (ref "IC10") (pin "17") (pinfunction "B3_17") (pintype "bidirectional"))
      (node (ref "R128") (pin "2") (pinfunction "2_2") (pintype "passive"))
    )
    (net (code "231") (name "Net-(IC10-B4)") (class "Default")
      (node (ref "IC10") (pin "16") (pinfunction "B4_16") (pintype "bidirectional"))
      (node (ref "R127") (pin "2") (pinfunction "2_2") (pintype "passive"))
    )
    (net (code "232") (name "Net-(IC10-B5)") (class "Default")
      (node (ref "IC10") (pin "15") (pinfunction "B5_15") (pintype "bidirectional"))
      (node (ref "R126") (pin "2") (pinfunction "2_2") (pintype "passive"))
    )
    (net (code "233") (name "Net-(IC10-B6)") (class "Default")
      (node (ref "IC10") (pin "14") (pinfunction "B6_14") (pintype "bidirectional"))
      (node (ref "R86") (pin "2") (pinfunction "2_2") (pintype "passive"))
    )
    (net (code "234") (name "Net-(IC10-OE)") (class "Default")
      (node (ref "IC10") (pin "10") (pinfunction "OE_10") (pintype "bidirectional"))
      (node (ref "IC11") (pin "10") (pinfunction "OE_10") (pintype "bidirectional"))
      (node (ref "R106") (pin "1") (pinfunction "1_1") (pintype "passive"))
      (node (ref "R131") (pin "1") (pinfunction "1_1") (pintype "passive"))
    )
    (net (code "235") (name "Net-(IC11-B2)") (class "Default")
      (node (ref "IC11") (pin "18") (pinfunction "B2_18") (pintype "bidirectional"))
      (node (ref "R136") (pin "2") (pinfunction "2_2") (pintype "passive"))
    )
    (net (code "236") (name "Net-(IC11-B3)") (class "Default")
      (node (ref "IC11") (pin "17") (pinfunction "B3_17") (pintype "bidirectional"))
      (node (ref "R135") (pin "2") (pinfunction "2_2") (pintype "passive"))
    )
    (net (code "237") (name "Net-(IC11-B8)") (class "Default")
      (node (ref "IC11") (pin "12") (pinfunction "B8_12") (pintype "bidirectional"))
      (node (ref "R134") (pin "2") (pinfunction "2_2") (pintype "passive"))
    )
    (net (code "238") (name "Net-(IC13-Q)") (class "Default")
      (node (ref "FB6") (pin "1") (pinfunction "1_1") (pintype "passive"))
      (node (ref "IC13") (pin "5") (pinfunction "Q_5") (pintype "bidirectional"))
    )
    (net (code "239") (name "Net-(IC18-ADJ)") (class "Default")
      (node (ref "IC18") (pin "5") (pinfunction "ADJ_5") (pintype "bidirectional"))
      (node (ref "R93") (pin "2") (pinfunction "2_2") (pintype "passive"))
      (node (ref "R94") (pin "1") (pinfunction "1_1") (pintype "passive"))
    )
    (net (code "240") (name "Net-(IC18-SHDN#)") (class "Default")
      (node (ref "IC18") (pin "1") (pinfunction "SHDN#_1") (pintype "bidirectional"))
      (node (ref "R89") (pin "2") (pinfunction "2_2") (pintype "passive"))
      (node (ref "R97") (pin "2") (pinfunction "2_2") (pintype "passive"))
    )
    (net (code "241") (name "Net-(IC22-VDDI)") (class "Default")
      (node (ref "C69") (pin "1") (pinfunction "1_1") (pintype "passive"))
      (node (ref "C7") (pin "1") (pinfunction "1_1") (pintype "passive"))
      (node (ref "IC22") (pin "C2") (pinfunction "VDDI_C2") (pintype "bidirectional"))
    )
    (net (code "242") (name "Net-(MOD1-BT_AUD_CLK)") (class "Default")
      (node (ref "MOD1") (pin "60") (pinfunction "BT_AUD_CLK_60") (pintype "bidirectional"))
      (node (ref "TP19") (pin "TP") (pinfunction "TP_TP") (pintype "input"))
    )
    (net (code "243") (name "Net-(MOD1-BT_AUD_FSYNC)") (class "Default")
      (node (ref "MOD1") (pin "58") (pinfunction "BT_AUD_FSYNC_58") (pintype "bidirectional"))
      (node (ref "TP18") (pin "TP") (pinfunction "TP_TP") (pintype "input"))
    )
    (net (code "244") (name "Net-(MOD1-BT_AUD_IN)") (class "Default")
      (node (ref "MOD1") (pin "56") (pinfunction "BT_AUD_IN_56") (pintype "bidirectional"))
      (node (ref "TP16") (pin "TP") (pinfunction "TP_TP") (pintype "input"))
    )
    (net (code "245") (name "Net-(MOD1-BT_AUD_OUT)") (class "Default")
      (node (ref "MOD1") (pin "57") (pinfunction "BT_AUD_OUT_57") (pintype "bidirectional"))
      (node (ref "TP17") (pin "TP") (pinfunction "TP_TP") (pintype "input"))
    )
    (net (code "246") (name "Net-(MOD1-BT_HCI_CTS)") (class "Default")
      (node (ref "MOD1") (pin "51") (pinfunction "BT_HCI_CTS_51") (pintype "bidirectional"))
      (node (ref "R141") (pin "1") (pinfunction "1_1") (pintype "passive"))
    )
    (net (code "247") (name "Net-(MOD1-BT_HCI_RTS)") (class "Default")
      (node (ref "MOD1") (pin "50") (pinfunction "BT_HCI_RTS_50") (pintype "bidirectional"))
      (node (ref "R140") (pin "1") (pinfunction "1_1") (pintype "passive"))
    )
    (net (code "248") (name "Net-(MOD1-BT_HCI_RX)") (class "Default")
      (node (ref "MOD1") (pin "53") (pinfunction "BT_HCI_RX_53") (pintype "bidirectional"))
      (node (ref "R143") (pin "1") (pinfunction "1_1") (pintype "passive"))
    )
    (net (code "249") (name "Net-(MOD1-BT_HCI_TX)") (class "Default")
      (node (ref "MOD1") (pin "52") (pinfunction "BT_HCI_TX_52") (pintype "bidirectional"))
      (node (ref "R142") (pin "1") (pinfunction "1_1") (pintype "passive"))
    )
    (net (code "250") (name "Net-(MOD1-BT_UART_DBG)") (class "Default")
      (node (ref "MOD1") (pin "43") (pinfunction "BT_UART_DBG_43") (pintype "bidirectional"))
      (node (ref "TP15") (pin "TP") (pinfunction "TP_TP") (pintype "input"))
    )
    (net (code "251") (name "Net-(MOD1-GPIO1)") (class "Default")
      (node (ref "MOD1") (pin "27") (pinfunction "GPIO1_27") (pintype "bidirectional"))
      (node (ref "TP13") (pin "TP") (pinfunction "TP_TP") (pintype "input"))
    )
    (net (code "252") (name "Net-(MOD1-GPIO2)") (class "Default")
      (node (ref "MOD1") (pin "26") (pinfunction "GPIO2_26") (pintype "bidirectional"))
      (node (ref "TP12") (pin "TP") (pinfunction "TP_TP") (pintype "input"))
    )
    (net (code "253") (name "Net-(MOD1-RF_ANT1)") (class "Default")
      (node (ref "C46") (pin "2") (pinfunction "2_2") (pintype "passive"))
      (node (ref "MOD1") (pin "32") (pinfunction "RF_ANT1_32") (pintype "bidirectional"))
    )
    (net (code "254") (name "Net-(MOD1-RF_ANT2)") (class "Default")
      (node (ref "C60") (pin "2") (pinfunction "2_2") (pintype "passive"))
      (node (ref "MOD1") (pin "18") (pinfunction "RF_ANT2_18") (pintype "bidirectional"))
    )
    (net (code "255") (name "Net-(MOD1-WLAN_IRQ)") (class "Default")
      (node (ref "MOD1") (pin "14") (pinfunction "WLAN_IRQ_14") (pintype "bidirectional"))
      (node (ref "R111") (pin "2") (pinfunction "2_2") (pintype "passive"))
      (node (ref "R60") (pin "1") (pinfunction "1_1") (pintype "passive"))
    )
    (net (code "256") (name "Net-(MOD1-WL_SDIO_CLK)") (class "Default")
      (node (ref "MOD1") (pin "8") (pinfunction "WL_SDIO_CLK_8") (pintype "bidirectional"))
      (node (ref "R64") (pin "1") (pinfunction "1_1") (pintype "passive"))
    )
    (net (code "257") (name "Net-(MOD1-WL_SDIO_CMD)") (class "Default")
      (node (ref "MOD1") (pin "6") (pinfunction "WL_SDIO_CMD_6") (pintype "bidirectional"))
      (node (ref "R62") (pin "1") (pinfunction "1_1") (pintype "passive"))
    )
    (net (code "258") (name "Net-(MOD1-WL_SDIO_D0)") (class "Default")
      (node (ref "MOD1") (pin "10") (pinfunction "WL_SDIO_D0_10") (pintype "bidirectional"))
      (node (ref "R66") (pin "1") (pinfunction "1_1") (pintype "passive"))
    )
    (net (code "259") (name "Net-(MOD1-WL_SDIO_D1)") (class "Default")
      (node (ref "MOD1") (pin "11") (pinfunction "WL_SDIO_D1_11") (pintype "bidirectional"))
      (node (ref "R68") (pin "1") (pinfunction "1_1") (pintype "passive"))
    )
    (net (code "260") (name "Net-(MOD1-WL_SDIO_D2)") (class "Default")
      (node (ref "MOD1") (pin "12") (pinfunction "WL_SDIO_D2_12") (pintype "bidirectional"))
      (node (ref "R70") (pin "1") (pinfunction "1_1") (pintype "passive"))
    )
    (net (code "261") (name "Net-(MOD1-WL_SDIO_D3)") (class "Default")
      (node (ref "MOD1") (pin "13") (pinfunction "WL_SDIO_D3_13") (pintype "bidirectional"))
      (node (ref "R72") (pin "1") (pinfunction "1_1") (pintype "passive"))
    )
    (net (code "262") (name "Net-(MOD1-WL_UART_DBG)") (class "Default")
      (node (ref "MOD1") (pin "42") (pinfunction "WL_UART_DBG_42") (pintype "bidirectional"))
      (node (ref "TP14") (pin "TP") (pinfunction "TP_TP") (pintype "input"))
    )
    (net (code "263") (name "Net-(OSC1-OUT)") (class "Default")
      (node (ref "OSC1") (pin "3") (pinfunction "OUT_3") (pintype "bidirectional"))
      (node (ref "R110") (pin "1") (pinfunction "1_1") (pintype "passive"))
    )
    (net (code "264") (name "Net-(OSC2-EN)") (class "Default")
      (node (ref "OSC2") (pin "1") (pinfunction "EN_1") (pintype "bidirectional"))
      (node (ref "R90") (pin "2") (pinfunction "2_2") (pintype "passive"))
    )
    (net (code "265") (name "Net-(PWR-PadK)") (class "Default")
      (node (ref "PWR") (pin "K") (pinfunction "K_K") (pintype "passive"))
      (node (ref "R55") (pin "2") (pinfunction "2_2") (pintype "passive"))
    )
    (net (code "266") (name "Net-(R88-Pad2)") (class "Default")
      (node (ref "R88") (pin "2") (pinfunction "2_2") (pintype "passive"))
      (node (ref "S2") (pin "1") (pinfunction "1_1") (pintype "bidirectional"))
      (node (ref "S2") (pin "2") (pinfunction "2_2") (pintype "bidirectional"))
    )
    (net (code "267") (name "Net-(R92-Pad1)") (class "Default")
      (node (ref "R92") (pin "1") (pinfunction "1_1") (pintype "passive"))
      (node (ref "USR3") (pin "A") (pinfunction "A_A") (pintype "passive"))
    )
    (net (code "268") (name "Net-(R96-Pad1)") (class "Default")
      (node (ref "R96") (pin "1") (pinfunction "1_1") (pintype "passive"))
      (node (ref "USR2") (pin "A") (pinfunction "A_A") (pintype "passive"))
    )
    (net (code "269") (name "Net-(R100-Pad1)") (class "Default")
      (node (ref "R100") (pin "1") (pinfunction "1_1") (pintype "passive"))
      (node (ref "USR1") (pin "A") (pinfunction "A_A") (pintype "passive"))
    )
    (net (code "270") (name "Net-(R104-Pad1)") (class "Default")
      (node (ref "R104") (pin "1") (pinfunction "1_1") (pintype "passive"))
      (node (ref "USR0") (pin "A") (pinfunction "A_A") (pintype "passive"))
    )
    (net (code "271") (name "Net-(R125-Pad1)") (class "Default")
      (node (ref "R125") (pin "1") (pinfunction "1_1") (pintype "passive"))
      (node (ref "WL") (pin "A") (pinfunction "A_A") (pintype "passive"))
    )
    (net (code "272") (name "Net-(T3-PadD)") (class "Default")
      (node (ref "T3") (pin "D") (pinfunction "D_D") (pintype "bidirectional"))
      (node (ref "WL") (pin "K") (pinfunction "K_K") (pintype "passive"))
    )
    (net (code "273") (name "unconnected-(D8-A1-Pad1)") (class "Default")
      (node (ref "D8") (pin "1") (pinfunction "A1_1") (pintype "passive"))
    )
    (net (code "274") (name "unconnected-(FUD1-PadP$1)") (class "Default")
      (node (ref "FUD1") (pin "P$1") (pinfunction "P$1_P$1") (pintype "no_connect"))
    )
    (net (code "275") (name "unconnected-(FUD2-PadP$1)") (class "Default")
      (node (ref "FUD2") (pin "P$1") (pinfunction "P$1_P$1") (pintype "no_connect"))
    )
    (net (code "276") (name "unconnected-(FUD3-PadP$1)") (class "Default")
      (node (ref "FUD3") (pin "P$1") (pinfunction "P$1_P$1") (pintype "no_connect"))
    )
    (net (code "277") (name "unconnected-(FUD4-PadP$1)") (class "Default")
      (node (ref "FUD4") (pin "P$1") (pinfunction "P$1_P$1") (pintype "no_connect"))
    )
    (net (code "278") (name "unconnected-(FUD5-PadP$1)") (class "Default")
      (node (ref "FUD5") (pin "P$1") (pinfunction "P$1_P$1") (pintype "no_connect"))
    )
    (net (code "279") (name "unconnected-(FUD6-PadP$1)") (class "Default")
      (node (ref "FUD6") (pin "P$1") (pinfunction "P$1_P$1") (pintype "no_connect"))
    )
    (net (code "280") (name "unconnected-(IC1B-UART0_CTSN-PadE18)") (class "Default")
      (node (ref "IC1") (pin "E18") (pinfunction "UART0_CTSN_E18") (pintype "bidirectional"))
    )
    (net (code "281") (name "unconnected-(IC1B-USB0_CE-PadM15)") (class "Default")
      (node (ref "IC1") (pin "M15") (pinfunction "USB0_CE_M15") (pintype "bidirectional"))
    )
    (net (code "282") (name "unconnected-(IC1B-USB0_DRVVBUS-PadF16)") (class "Default")
      (node (ref "IC1") (pin "F16") (pinfunction "USB0_DRVVBUS_F16") (pintype "bidirectional"))
    )
    (net (code "283") (name "unconnected-(IC1B-USB1_CE-PadP18)") (class "Default")
      (node (ref "IC1") (pin "P18") (pinfunction "USB1_CE_P18") (pintype "bidirectional"))
    )
    (net (code "284") (name "unconnected-(IC1C-L1_IN-PadY14)") (class "Default")
      (node (ref "IC1") (pin "Y14") (pinfunction "L1_IN_Y14") (pintype "bidirectional"))
    )
    (net (code "285") (name "unconnected-(IC1C-L2_IN-PadY17)") (class "Default")
      (node (ref "IC1") (pin "Y17") (pinfunction "L2_IN_Y17") (pintype "bidirectional"))
    )
    (net (code "286") (name "unconnected-(IC1C-L3_IN-PadY20)") (class "Default")
      (node (ref "IC1") (pin "Y20") (pinfunction "L3_IN_Y20") (pintype "bidirectional"))
    )
    (net (code "287") (name "unconnected-(IC1C-VDDS_DDR-PadY13)") (class "Default")
      (node (ref "IC1") (pin "Y13") (pinfunction "VDDS_DDR_Y13") (pintype "bidirectional"))
    )
    (net (code "288") (name "unconnected-(IC1C-VDD_CORE-PadY19)") (class "Default")
      (node (ref "IC1") (pin "Y19") (pinfunction "VDD_CORE_Y19") (pintype "bidirectional"))
    )
    (net (code "289") (name "unconnected-(IC1C-VDD_MPU-PadY16)") (class "Default")
      (node (ref "IC1") (pin "Y16") (pinfunction "VDD_MPU_Y16") (pintype "bidirectional"))
    )
    (net (code "290") (name "unconnected-(IC1D-NC1-PadB1)") (class "Default")
      (node (ref "IC1") (pin "B1") (pinfunction "NC1_B1") (pintype "bidirectional"))
    )
    (net (code "291") (name "unconnected-(IC1D-NC2-PadB2)") (class "Default")
      (node (ref "IC1") (pin "B2") (pinfunction "NC2_B2") (pintype "bidirectional"))
    )
    (net (code "292") (name "unconnected-(IC1D-NC3-PadB3)") (class "Default")
      (node (ref "IC1") (pin "B3") (pinfunction "NC3_B3") (pintype "bidirectional"))
    )
    (net (code "293") (name "unconnected-(IC1D-NC4-PadC1)") (class "Default")
      (node (ref "IC1") (pin "C1") (pinfunction "NC4_C1") (pintype "bidirectional"))
    )
    (net (code "294") (name "unconnected-(IC1D-NC5-PadC2)") (class "Default")
      (node (ref "IC1") (pin "C2") (pinfunction "NC5_C2") (pintype "bidirectional"))
    )
    (net (code "295") (name "unconnected-(IC1D-NC6-PadC3)") (class "Default")
      (node (ref "IC1") (pin "C3") (pinfunction "NC6_C3") (pintype "bidirectional"))
    )
    (net (code "296") (name "unconnected-(IC1D-NC12-PadC4)") (class "Default")
      (node (ref "IC1") (pin "C4") (pinfunction "NC12_C4") (pintype "bidirectional"))
    )
    (net (code "297") (name "unconnected-(IC1D-NC20-PadD1)") (class "Default")
      (node (ref "IC1") (pin "D1") (pinfunction "NC20_D1") (pintype "bidirectional"))
    )
    (net (code "298") (name "unconnected-(IC1D-NC21-PadD2)") (class "Default")
      (node (ref "IC1") (pin "D2") (pinfunction "NC21_D2") (pintype "bidirectional"))
    )
    (net (code "299") (name "unconnected-(IC1D-NC22-PadD3)") (class "Default")
      (node (ref "IC1") (pin "D3") (pinfunction "NC22_D3") (pintype "bidirectional"))
    )
    (net (code "300") (name "unconnected-(IC1D-NC23-PadD4)") (class "Default")
      (node (ref "IC1") (pin "D4") (pinfunction "NC23_D4") (pintype "bidirectional"))
    )
    (net (code "301") (name "unconnected-(IC1D-NC24-PadD5)") (class "Default")
      (node (ref "IC1") (pin "D5") (pinfunction "NC24_D5") (pintype "bidirectional"))
    )
    (net (code "302") (name "unconnected-(IC1D-NC31-PadE1)") (class "Default")
      (node (ref "IC1") (pin "E1") (pinfunction "NC31_E1") (pintype "bidirectional"))
    )
    (net (code "303") (name "unconnected-(IC1D-NC32-PadE2)") (class "Default")
      (node (ref "IC1") (pin "E2") (pinfunction "NC32_E2") (pintype "bidirectional"))
    )
    (net (code "304") (name "unconnected-(IC1D-NC33-PadE3)") (class "Default")
      (node (ref "IC1") (pin "E3") (pinfunction "NC33_E3") (pintype "bidirectional"))
    )
    (net (code "305") (name "unconnected-(IC1D-NC34-PadE4)") (class "Default")
      (node (ref "IC1") (pin "E4") (pinfunction "NC34_E4") (pintype "bidirectional"))
    )
    (net (code "306") (name "unconnected-(IC1D-NC45-PadF1)") (class "Default")
      (node (ref "IC1") (pin "F1") (pinfunction "NC45_F1") (pintype "bidirectional"))
    )
    (net (code "307") (name "unconnected-(IC1D-NC46-PadF2)") (class "Default")
      (node (ref "IC1") (pin "F2") (pinfunction "NC46_F2") (pintype "bidirectional"))
    )
    (net (code "308") (name "unconnected-(IC1D-NC47-PadF3)") (class "Default")
      (node (ref "IC1") (pin "F3") (pinfunction "NC47_F3") (pintype "bidirectional"))
    )
    (net (code "309") (name "unconnected-(IC1D-NC48-PadF4)") (class "Default")
      (node (ref "IC1") (pin "F4") (pinfunction "NC48_F4") (pintype "bidirectional"))
    )
    (net (code "310") (name "unconnected-(IC1D-NC58-PadG1)") (class "Default")
      (node (ref "IC1") (pin "G1") (pinfunction "NC58_G1") (pintype "bidirectional"))
    )
    (net (code "311") (name "unconnected-(IC1D-NC59-PadG2)") (class "Default")
      (node (ref "IC1") (pin "G2") (pinfunction "NC59_G2") (pintype "bidirectional"))
    )
    (net (code "312") (name "unconnected-(IC1D-NC60-PadG3)") (class "Default")
      (node (ref "IC1") (pin "G3") (pinfunction "NC60_G3") (pintype "bidirectional"))
    )
    (net (code "313") (name "unconnected-(IC1D-NC61-PadG4)") (class "Default")
      (node (ref "IC1") (pin "G4") (pinfunction "NC61_G4") (pintype "bidirectional"))
    )
    (net (code "314") (name "unconnected-(IC1D-NC68-PadH1)") (class "Default")
      (node (ref "IC1") (pin "H1") (pinfunction "NC68_H1") (pintype "bidirectional"))
    )
    (net (code "315") (name "unconnected-(IC1D-NC69-PadH2)") (class "Default")
      (node (ref "IC1") (pin "H2") (pinfunction "NC69_H2") (pintype "bidirectional"))
    )
    (net (code "316") (name "unconnected-(IC1D-NC70-PadH3)") (class "Default")
      (node (ref "IC1") (pin "H3") (pinfunction "NC70_H3") (pintype "bidirectional"))
    )
    (net (code "317") (name "unconnected-(IC1D-NC71-PadH4)") (class "Default")
      (node (ref "IC1") (pin "H4") (pinfunction "NC71_H4") (pintype "bidirectional"))
    )
    (net (code "318") (name "unconnected-(IC1D-NC76-PadJ1)") (class "Default")
      (node (ref "IC1") (pin "J1") (pinfunction "NC76_J1") (pintype "bidirectional"))
    )
    (net (code "319") (name "unconnected-(IC1D-NC77-PadJ2)") (class "Default")
      (node (ref "IC1") (pin "J2") (pinfunction "NC77_J2") (pintype "bidirectional"))
    )
    (net (code "320") (name "unconnected-(IC1D-NC78-PadJ3)") (class "Default")
      (node (ref "IC1") (pin "J3") (pinfunction "NC78_J3") (pintype "bidirectional"))
    )
    (net (code "321") (name "unconnected-(IC1D-NC79-PadJ4)") (class "Default")
      (node (ref "IC1") (pin "J4") (pinfunction "NC79_J4") (pintype "bidirectional"))
    )
    (net (code "322") (name "unconnected-(IC1D-NC84-PadK1)") (class "Default")
      (node (ref "IC1") (pin "K1") (pinfunction "NC84_K1") (pintype "bidirectional"))
    )
    (net (code "323") (name "unconnected-(IC1D-NC85-PadK2)") (class "Default")
      (node (ref "IC1") (pin "K2") (pinfunction "NC85_K2") (pintype "bidirectional"))
    )
    (net (code "324") (name "unconnected-(IC1D-NC86-PadK3)") (class "Default")
      (node (ref "IC1") (pin "K3") (pinfunction "NC86_K3") (pintype "bidirectional"))
    )
    (net (code "325") (name "unconnected-(IC1D-NC87-PadK4)") (class "Default")
      (node (ref "IC1") (pin "K4") (pinfunction "NC87_K4") (pintype "bidirectional"))
    )
    (net (code "326") (name "unconnected-(IC1D-NC94-PadL1)") (class "Default")
      (node (ref "IC1") (pin "L1") (pinfunction "NC94_L1") (pintype "bidirectional"))
    )
    (net (code "327") (name "unconnected-(IC1D-NC95-PadL2)") (class "Default")
      (node (ref "IC1") (pin "L2") (pinfunction "NC95_L2") (pintype "bidirectional"))
    )
    (net (code "328") (name "unconnected-(IC1D-NC96-PadL3)") (class "Default")
      (node (ref "IC1") (pin "L3") (pinfunction "NC96_L3") (pintype "bidirectional"))
    )
    (net (code "329") (name "unconnected-(IC1D-NC97-PadL4)") (class "Default")
      (node (ref "IC1") (pin "L4") (pinfunction "NC97_L4") (pintype "bidirectional"))
    )
    (net (code "330") (name "unconnected-(IC1D-NC104-PadM1)") (class "Default")
      (node (ref "IC1") (pin "M1") (pinfunction "NC104_M1") (pintype "bidirectional"))
    )
    (net (code "331") (name "unconnected-(IC1D-NC105-PadM2)") (class "Default")
      (node (ref "IC1") (pin "M2") (pinfunction "NC105_M2") (pintype "bidirectional"))
    )
    (net (code "332") (name "unconnected-(IC1D-NC106-PadM3)") (class "Default")
      (node (ref "IC1") (pin "M3") (pinfunction "NC106_M3") (pintype "bidirectional"))
    )
    (net (code "333") (name "unconnected-(IC1D-NC107-PadM4)") (class "Default")
      (node (ref "IC1") (pin "M4") (pinfunction "NC107_M4") (pintype "bidirectional"))
    )
    (net (code "334") (name "unconnected-(IC1D-NC111-PadN1)") (class "Default")
      (node (ref "IC1") (pin "N1") (pinfunction "NC111_N1") (pintype "bidirectional"))
    )
    (net (code "335") (name "unconnected-(IC1D-NC112-PadN2)") (class "Default")
      (node (ref "IC1") (pin "N2") (pinfunction "NC112_N2") (pintype "bidirectional"))
    )
    (net (code "336") (name "unconnected-(IC1D-NC113-PadN3)") (class "Default")
      (node (ref "IC1") (pin "N3") (pinfunction "NC113_N3") (pintype "bidirectional"))
    )
    (net (code "337") (name "unconnected-(IC1D-NC114-PadN4)") (class "Default")
      (node (ref "IC1") (pin "N4") (pinfunction "NC114_N4") (pintype "bidirectional"))
    )
    (net (code "338") (name "unconnected-(IC1D-NC121-PadP1)") (class "Default")
      (node (ref "IC1") (pin "P1") (pinfunction "NC121_P1") (pintype "bidirectional"))
    )
    (net (code "339") (name "unconnected-(IC1D-NC122-PadP2)") (class "Default")
      (node (ref "IC1") (pin "P2") (pinfunction "NC122_P2") (pintype "bidirectional"))
    )
    (net (code "340") (name "unconnected-(IC1D-NC123-PadP3)") (class "Default")
      (node (ref "IC1") (pin "P3") (pinfunction "NC123_P3") (pintype "bidirectional"))
    )
    (net (code "341") (name "unconnected-(IC1D-NC124-PadP4)") (class "Default")
      (node (ref "IC1") (pin "P4") (pinfunction "NC124_P4") (pintype "bidirectional"))
    )
    (net (code "342") (name "unconnected-(IC1D-NC136-PadU11)") (class "Default")
      (node (ref "IC1") (pin "U11") (pinfunction "NC136_U11") (pintype "bidirectional"))
    )
    (net (code "343") (name "unconnected-(IC1D-NC137-PadV10)") (class "Default")
      (node (ref "IC1") (pin "V10") (pinfunction "NC137_V10") (pintype "bidirectional"))
    )
    (net (code "344") (name "unconnected-(IC1D-NC138-PadV11)") (class "Default")
      (node (ref "IC1") (pin "V11") (pinfunction "NC138_V11") (pintype "bidirectional"))
    )
    (net (code "345") (name "unconnected-(IC1E-CAP_VBB_MPU-PadC10)") (class "Default")
      (node (ref "IC1") (pin "C10") (pinfunction "CAP_VBB_MPU_C10") (pintype "bidirectional"))
    )
    (net (code "346") (name "unconnected-(IC1E-CAP_VDD_RTC-PadD6)") (class "Default")
      (node (ref "IC1") (pin "D6") (pinfunction "CAP_VDD_RTC_D6") (pintype "bidirectional"))
    )
    (net (code "347") (name "unconnected-(IC1E-CAP_VDD_SRAM_COR-PadD9)") (class "Default")
      (node (ref "IC1") (pin "D9") (pinfunction "CAP_VDD_SRAM_COR_D9") (pintype "bidirectional"))
    )
    (net (code "348") (name "unconnected-(IC1E-CAP_VDD_SRAM_MPU-PadD11)") (class "Default")
      (node (ref "IC1") (pin "D11") (pinfunction "CAP_VDD_SRAM_MPU_D11") (pintype "bidirectional"))
    )
    (net (code "349") (name "unconnected-(IC1E-TESTOUT-PadA3)") (class "Default")
      (node (ref "IC1") (pin "A3") (pinfunction "TESTOUT_A3") (pintype "bidirectional"))
    )
    (net (code "350") (name "unconnected-(IC1E-VDDS_DDR1-PadE5)") (class "Default")
      (node (ref "IC1") (pin "E5") (pinfunction "VDDS_DDR1_E5") (pintype "bidirectional"))
    )
    (net (code "351") (name "unconnected-(IC1E-VDDS_DDR2-PadF5)") (class "Default")
      (node (ref "IC1") (pin "F5") (pinfunction "VDDS_DDR2_F5") (pintype "bidirectional"))
    )
    (net (code "352") (name "unconnected-(IC1E-VDDS_DDR3-PadG5)") (class "Default")
      (node (ref "IC1") (pin "G5") (pinfunction "VDDS_DDR3_G5") (pintype "bidirectional"))
    )
    (net (code "353") (name "unconnected-(IC1E-VDDS_DDR5-PadJ5)") (class "Default")
      (node (ref "IC1") (pin "J5") (pinfunction "VDDS_DDR5_J5") (pintype "bidirectional"))
    )
    (net (code "354") (name "unconnected-(IC1E-VDDS_DDR6-PadK5)") (class "Default")
      (node (ref "IC1") (pin "K5") (pinfunction "VDDS_DDR6_K5") (pintype "bidirectional"))
    )
    (net (code "355") (name "unconnected-(IC1E-VDDS_DDR7-PadL5)") (class "Default")
      (node (ref "IC1") (pin "L5") (pinfunction "VDDS_DDR7_L5") (pintype "bidirectional"))
    )
    (net (code "356") (name "unconnected-(IC1E-VDD_3V3A1-PadF14)") (class "Default")
      (node (ref "IC1") (pin "F14") (pinfunction "VDD_3V3A1_F14") (pintype "bidirectional"))
    )
    (net (code "357") (name "unconnected-(IC1E-VDD_3V3A2-PadG14)") (class "Default")
      (node (ref "IC1") (pin "G14") (pinfunction "VDD_3V3A2_G14") (pintype "bidirectional"))
    )
    (net (code "358") (name "unconnected-(IC1E-VDD_3V3A3-PadH14)") (class "Default")
      (node (ref "IC1") (pin "H14") (pinfunction "VDD_3V3A3_H14") (pintype "bidirectional"))
    )
    (net (code "359") (name "unconnected-(IC1E-VDD_3V3A4-PadJ14)") (class "Default")
      (node (ref "IC1") (pin "J14") (pinfunction "VDD_3V3A4_J14") (pintype "bidirectional"))
    )
    (net (code "360") (name "unconnected-(IC1E-VDD_3V3A5-PadK14)") (class "Default")
      (node (ref "IC1") (pin "K14") (pinfunction "VDD_3V3A5_K14") (pintype "bidirectional"))
    )
    (net (code "361") (name "unconnected-(IC1E-VDD_3V3A6-PadL14)") (class "Default")
      (node (ref "IC1") (pin "L14") (pinfunction "VDD_3V3A6_L14") (pintype "bidirectional"))
    )
    (net (code "362") (name "unconnected-(IC1E-VDD_3V3A7-PadN15)") (class "Default")
      (node (ref "IC1") (pin "N15") (pinfunction "VDD_3V3A7_N15") (pintype "bidirectional"))
    )
    (net (code "363") (name "unconnected-(IC1E-VDD_3V3A8-PadR15)") (class "Default")
      (node (ref "IC1") (pin "R15") (pinfunction "VDD_3V3A8_R15") (pintype "bidirectional"))
    )
    (net (code "364") (name "unconnected-(IC1E-VDD_3V3A9-PadP13)") (class "Default")
      (node (ref "IC1") (pin "P13") (pinfunction "VDD_3V3A9_P13") (pintype "bidirectional"))
    )
    (net (code "365") (name "unconnected-(IC1E-VDD_3V3A10-PadP12)") (class "Default")
      (node (ref "IC1") (pin "P12") (pinfunction "VDD_3V3A10_P12") (pintype "bidirectional"))
    )
    (net (code "366") (name "unconnected-(IC1E-VDD_3V3A11-PadP11)") (class "Default")
      (node (ref "IC1") (pin "P11") (pinfunction "VDD_3V3A11_P11") (pintype "bidirectional"))
    )
    (net (code "367") (name "unconnected-(IC1E-VDD_3V3A12-PadP10)") (class "Default")
      (node (ref "IC1") (pin "P10") (pinfunction "VDD_3V3A12_P10") (pintype "bidirectional"))
    )
    (net (code "368") (name "unconnected-(IC1E-VDD_3V3A14-PadP8)") (class "Default")
      (node (ref "IC1") (pin "P8") (pinfunction "VDD_3V3A14_P8") (pintype "bidirectional"))
    )
    (net (code "369") (name "unconnected-(IC1E-VDD_3V3A19-PadE13)") (class "Default")
      (node (ref "IC1") (pin "E13") (pinfunction "VDD_3V3A19_E13") (pintype "bidirectional"))
    )
    (net (code "370") (name "unconnected-(IC1E-VDD_3V3A20-PadE12)") (class "Default")
      (node (ref "IC1") (pin "E12") (pinfunction "VDD_3V3A20_E12") (pintype "bidirectional"))
    )
    (net (code "371") (name "unconnected-(IC1E-VDD_3V3A21-PadE11)") (class "Default")
      (node (ref "IC1") (pin "E11") (pinfunction "VDD_3V3A21_E11") (pintype "bidirectional"))
    )
    (net (code "372") (name "unconnected-(IC1E-VDD_3V3A22-PadE10)") (class "Default")
      (node (ref "IC1") (pin "E10") (pinfunction "VDD_3V3A22_E10") (pintype "bidirectional"))
    )
    (net (code "373") (name "unconnected-(IC1E-VDD_CORE2-PadF7)") (class "Default")
      (node (ref "IC1") (pin "F7") (pinfunction "VDD_CORE2_F7") (pintype "bidirectional"))
    )
    (net (code "374") (name "unconnected-(IC1E-VDD_CORE3-PadG6)") (class "Default")
      (node (ref "IC1") (pin "G6") (pinfunction "VDD_CORE3_G6") (pintype "bidirectional"))
    )
    (net (code "375") (name "unconnected-(IC1E-VDD_CORE4-PadG7)") (class "Default")
      (node (ref "IC1") (pin "G7") (pinfunction "VDD_CORE4_G7") (pintype "bidirectional"))
    )
    (net (code "376") (name "unconnected-(IC1E-VDD_CORE5-PadG10)") (class "Default")
      (node (ref "IC1") (pin "G10") (pinfunction "VDD_CORE5_G10") (pintype "bidirectional"))
    )
    (net (code "377") (name "unconnected-(IC1E-VDD_CORE6-PadH11)") (class "Default")
      (node (ref "IC1") (pin "H11") (pinfunction "VDD_CORE6_H11") (pintype "bidirectional"))
    )
    (net (code "378") (name "unconnected-(IC1E-VDD_CORE7-PadJ12)") (class "Default")
      (node (ref "IC1") (pin "J12") (pinfunction "VDD_CORE7_J12") (pintype "bidirectional"))
    )
    (net (code "379") (name "unconnected-(IC1E-VDD_CORE8-PadK6)") (class "Default")
      (node (ref "IC1") (pin "K6") (pinfunction "VDD_CORE8_K6") (pintype "bidirectional"))
    )
    (net (code "380") (name "unconnected-(IC1E-VDD_CORE9-PadK8)") (class "Default")
      (node (ref "IC1") (pin "K8") (pinfunction "VDD_CORE9_K8") (pintype "bidirectional"))
    )
    (net (code "381") (name "unconnected-(IC1E-VDD_CORE10-PadK12)") (class "Default")
      (node (ref "IC1") (pin "K12") (pinfunction "VDD_CORE10_K12") (pintype "bidirectional"))
    )
    (net (code "382") (name "unconnected-(IC1E-VDD_CORE11-PadL6)") (class "Default")
      (node (ref "IC1") (pin "L6") (pinfunction "VDD_CORE11_L6") (pintype "bidirectional"))
    )
    (net (code "383") (name "unconnected-(IC1E-VDD_CORE12-PadL7)") (class "Default")
      (node (ref "IC1") (pin "L7") (pinfunction "VDD_CORE12_L7") (pintype "bidirectional"))
    )
    (net (code "384") (name "unconnected-(IC1E-VDD_CORE13-PadL8)") (class "Default")
      (node (ref "IC1") (pin "L8") (pinfunction "VDD_CORE13_L8") (pintype "bidirectional"))
    )
    (net (code "385") (name "unconnected-(IC1E-VDD_CORE14-PadL9)") (class "Default")
      (node (ref "IC1") (pin "L9") (pinfunction "VDD_CORE14_L9") (pintype "bidirectional"))
    )
    (net (code "386") (name "unconnected-(IC1E-VDD_CORE15-PadM11)") (class "Default")
      (node (ref "IC1") (pin "M11") (pinfunction "VDD_CORE15_M11") (pintype "bidirectional"))
    )
    (net (code "387") (name "unconnected-(IC1E-VDD_CORE16-PadM13)") (class "Default")
      (node (ref "IC1") (pin "M13") (pinfunction "VDD_CORE16_M13") (pintype "bidirectional"))
    )
    (net (code "388") (name "unconnected-(IC1E-VDD_CORE17-PadN8)") (class "Default")
      (node (ref "IC1") (pin "N8") (pinfunction "VDD_CORE17_N8") (pintype "bidirectional"))
    )
    (net (code "389") (name "unconnected-(IC1E-VDD_CORE18-PadN9)") (class "Default")
      (node (ref "IC1") (pin "N9") (pinfunction "VDD_CORE18_N9") (pintype "bidirectional"))
    )
    (net (code "390") (name "unconnected-(IC1E-VDD_CORE19-PadN12)") (class "Default")
      (node (ref "IC1") (pin "N12") (pinfunction "VDD_CORE19_N12") (pintype "bidirectional"))
    )
    (net (code "391") (name "unconnected-(IC1E-VDD_CORE20-PadN13)") (class "Default")
      (node (ref "IC1") (pin "N13") (pinfunction "VDD_CORE20_N13") (pintype "bidirectional"))
    )
    (net (code "392") (name "unconnected-(IC1E-VDD_MPU1-PadF11)") (class "Default")
      (node (ref "IC1") (pin "F11") (pinfunction "VDD_MPU1_F11") (pintype "bidirectional"))
    )
    (net (code "393") (name "unconnected-(IC1E-VDD_MPU2-PadF12)") (class "Default")
      (node (ref "IC1") (pin "F12") (pinfunction "VDD_MPU2_F12") (pintype "bidirectional"))
    )
    (net (code "394") (name "unconnected-(IC1E-VDD_MPU3-PadF13)") (class "Default")
      (node (ref "IC1") (pin "F13") (pinfunction "VDD_MPU3_F13") (pintype "bidirectional"))
    )
    (net (code "395") (name "unconnected-(IC1E-VDD_MPU4-PadG13)") (class "Default")
      (node (ref "IC1") (pin "G13") (pinfunction "VDD_MPU4_G13") (pintype "bidirectional"))
    )
    (net (code "396") (name "unconnected-(IC1E-VDD_MPU5-PadH13)") (class "Default")
      (node (ref "IC1") (pin "H13") (pinfunction "VDD_MPU5_H13") (pintype "bidirectional"))
    )
    (net (code "397") (name "unconnected-(IC1E-VDD_MPU6-PadJ13)") (class "Default")
      (node (ref "IC1") (pin "J13") (pinfunction "VDD_MPU6_J13") (pintype "bidirectional"))
    )
    (net (code "398") (name "unconnected-(IC1E-VDD_MPU_MON-PadA2)") (class "Default")
      (node (ref "IC1") (pin "A2") (pinfunction "VDD_MPU_MON_A2") (pintype "bidirectional"))
    )
    (net (code "399") (name "unconnected-(IC1E-VDD_PLL2-PadR10)") (class "Default")
      (node (ref "IC1") (pin "R10") (pinfunction "VDD_PLL2_R10") (pintype "bidirectional"))
    )
    (net (code "400") (name "unconnected-(IC1E-VDD_PLL3-PadR11)") (class "Default")
      (node (ref "IC1") (pin "R11") (pinfunction "VDD_PLL3_R11") (pintype "bidirectional"))
    )
    (net (code "401") (name "unconnected-(IC1E-VDD_PLL4-PadH15)") (class "Default")
      (node (ref "IC1") (pin "H15") (pinfunction "VDD_PLL4_H15") (pintype "bidirectional"))
    )
    (net (code "402") (name "unconnected-(IC1E-VDD_RTC1-PadD7)") (class "Default")
      (node (ref "IC1") (pin "D7") (pinfunction "VDD_RTC1_D7") (pintype "bidirectional"))
    )
    (net (code "403") (name "unconnected-(IC1E-VDD_RTC2-PadE6)") (class "Default")
      (node (ref "IC1") (pin "E6") (pinfunction "VDD_RTC2_E6") (pintype "bidirectional"))
    )
    (net (code "404") (name "unconnected-(IC1E-VDD_RTC3-PadF9)") (class "Default")
      (node (ref "IC1") (pin "F9") (pinfunction "VDD_RTC3_F9") (pintype "bidirectional"))
    )
    (net (code "405") (name "unconnected-(IC1E-VDD_RTC5-PadP14)") (class "Default")
      (node (ref "IC1") (pin "P14") (pinfunction "VDD_RTC5_P14") (pintype "bidirectional"))
    )
    (net (code "406") (name "unconnected-(IC1E-VDD_RTC6-PadK13)") (class "Default")
      (node (ref "IC1") (pin "K13") (pinfunction "VDD_RTC6_K13") (pintype "bidirectional"))
    )
    (net (code "407") (name "unconnected-(IC1E-VDD_RTC7-PadE14)") (class "Default")
      (node (ref "IC1") (pin "E14") (pinfunction "VDD_RTC7_E14") (pintype "bidirectional"))
    )
    (net (code "408") (name "unconnected-(IC1E-VDD_RTC8-PadP9)") (class "Default")
      (node (ref "IC1") (pin "P9") (pinfunction "VDD_RTC8_P9") (pintype "bidirectional"))
    )
    (net (code "409") (name "unconnected-(IC1E-VPP-PadM5)") (class "Default")
      (node (ref "IC1") (pin "M5") (pinfunction "VPP_M5") (pintype "bidirectional"))
    )
    (net (code "410") (name "unconnected-(IC7-NC1-Pad6)") (class "Default")
      (node (ref "IC7") (pin "6") (pinfunction "NC1_6") (pintype "bidirectional"))
    )
    (net (code "411") (name "unconnected-(IC7-NC2-Pad7)") (class "Default")
      (node (ref "IC7") (pin "7") (pinfunction "NC2_7") (pintype "bidirectional"))
    )
    (net (code "412") (name "unconnected-(IC7-NC3-Pad9)") (class "Default")
      (node (ref "IC7") (pin "9") (pinfunction "NC3_9") (pintype "bidirectional"))
    )
    (net (code "413") (name "unconnected-(IC7-NC4-Pad10)") (class "Default")
      (node (ref "IC7") (pin "10") (pinfunction "NC4_10") (pintype "bidirectional"))
    )
    (net (code "414") (name "unconnected-(IC8-NC1-Pad6)") (class "Default")
      (node (ref "IC8") (pin "6") (pinfunction "NC1_6") (pintype "bidirectional"))
    )
    (net (code "415") (name "unconnected-(IC8-NC2-Pad7)") (class "Default")
      (node (ref "IC8") (pin "7") (pinfunction "NC2_7") (pintype "bidirectional"))
    )
    (net (code "416") (name "unconnected-(IC8-NC3-Pad9)") (class "Default")
      (node (ref "IC8") (pin "9") (pinfunction "NC3_9") (pintype "bidirectional"))
    )
    (net (code "417") (name "unconnected-(IC8-NC4-Pad10)") (class "Default")
      (node (ref "IC8") (pin "10") (pinfunction "NC4_10") (pintype "bidirectional"))
    )
    (net (code "418") (name "unconnected-(IC9-AP2-Pad26)") (class "Default")
      (node (ref "IC9") (pin "26") (pinfunction "AP2_26") (pintype "bidirectional"))
    )
    (net (code "419") (name "unconnected-(IC9-AP4-Pad28)") (class "Default")
      (node (ref "IC9") (pin "28") (pinfunction "AP4_28") (pintype "bidirectional"))
    )
    (net (code "420") (name "unconnected-(IC10-A7-Pad8)") (class "Default")
      (node (ref "IC10") (pin "8") (pinfunction "A7_8") (pintype "bidirectional"))
    )
    (net (code "421") (name "unconnected-(IC10-A8-Pad9)") (class "Default")
      (node (ref "IC10") (pin "9") (pinfunction "A8_9") (pintype "bidirectional"))
    )
    (net (code "422") (name "unconnected-(IC10-B7-Pad13)") (class "Default")
      (node (ref "IC10") (pin "13") (pinfunction "B7_13") (pintype "bidirectional"))
    )
    (net (code "423") (name "unconnected-(IC10-B8-Pad12)") (class "Default")
      (node (ref "IC10") (pin "12") (pinfunction "B8_12") (pintype "bidirectional"))
    )
    (net (code "424") (name "unconnected-(IC14-NC-Pad5)") (class "Default")
      (node (ref "IC14") (pin "5") (pinfunction "NC_5") (pintype "bidirectional"))
    )
    (net (code "425") (name "unconnected-(IC15-ID-Pad3)") (class "Default")
      (node (ref "IC15") (pin "3") (pinfunction "ID_3") (pintype "bidirectional"))
    )
    (net (code "426") (name "unconnected-(IC15-NC-Pad5)") (class "Default")
      (node (ref "IC15") (pin "5") (pinfunction "NC_5") (pintype "bidirectional"))
    )
    (net (code "427") (name "unconnected-(IC19-NC{slash}ADJ-Pad4)") (class "Default")
      (node (ref "IC19") (pin "4") (pinfunction "NC/ADJ_4") (pintype "bidirectional"))
    )
    (net (code "428") (name "unconnected-(MOD1-GPIO4-Pad25)") (class "Default")
      (node (ref "MOD1") (pin "25") (pinfunction "GPIO4_25") (pintype "bidirectional"))
    )
    (net (code "429") (name "unconnected-(MOD1-GPIO9-Pad3)") (class "Default")
      (node (ref "MOD1") (pin "3") (pinfunction "GPIO9_3") (pintype "bidirectional"))
    )
    (net (code "430") (name "unconnected-(MOD1-GPIO10-Pad4)") (class "Default")
      (node (ref "MOD1") (pin "4") (pinfunction "GPIO10_4") (pintype "bidirectional"))
    )
    (net (code "431") (name "unconnected-(MOD1-GPIO11-Pad2)") (class "Default")
      (node (ref "MOD1") (pin "2") (pinfunction "GPIO11_2") (pintype "bidirectional"))
    )
    (net (code "432") (name "unconnected-(MOD1-GPIO12-Pad5)") (class "Default")
      (node (ref "MOD1") (pin "5") (pinfunction "GPIO12_5") (pintype "bidirectional"))
    )
    (net (code "433") (name "unconnected-(MOD1-RESERVED1-Pad21)") (class "Default")
      (node (ref "MOD1") (pin "21") (pinfunction "RESERVED1_21") (pintype "bidirectional"))
    )
    (net (code "434") (name "unconnected-(MOD1-RESERVED2-Pad22)") (class "Default")
      (node (ref "MOD1") (pin "22") (pinfunction "RESERVED2_22") (pintype "bidirectional"))
    )
    (net (code "435") (name "unconnected-(MOD1-RESERVED3-Pad62)") (class "Default")
      (node (ref "MOD1") (pin "62") (pinfunction "RESERVED3_62") (pintype "bidirectional"))
    )
    (net (code "436") (name "unconnected-(P2-NC-Pad6)") (class "Default")
      (node (ref "P2") (pin "6") (pinfunction "NC_6") (pintype "bidirectional"))
    )
    (net (code "437") (name "unconnected-(X1-Pad2)") (class "Default")
      (node (ref "X1") (pin "2") (pinfunction "2_2") (pintype "passive"))
    )
    (net (code "438") (name "unconnected-(X1-Pad3)") (class "Default")
      (node (ref "X1") (pin "3") (pinfunction "3_3") (pintype "passive"))
    )
    (net (code "439") (name "unconnected-(X1-Pad6)") (class "Default")
      (node (ref "X1") (pin "6") (pinfunction "6_6") (pintype "passive"))
    )
    (net (code "440") (name "unconnected-(X5-NC-Pad2)") (class "Default")
      (node (ref "X5") (pin "2") (pinfunction "NC_2") (pintype "bidirectional"))
    )
    (net (code "441") (name "unconnected-(X12-PadOUT_CON)") (class "Default")
      (node (ref "X12") (pin "OUT_CON") (pinfunction "OUT_CON_OUT_CON") (pintype "bidirectional"))
    )
  )
)
